# Full_bridge-2-Buck_drives_-9.net
KiCad netlist of a schematic drawn in Altium Designer
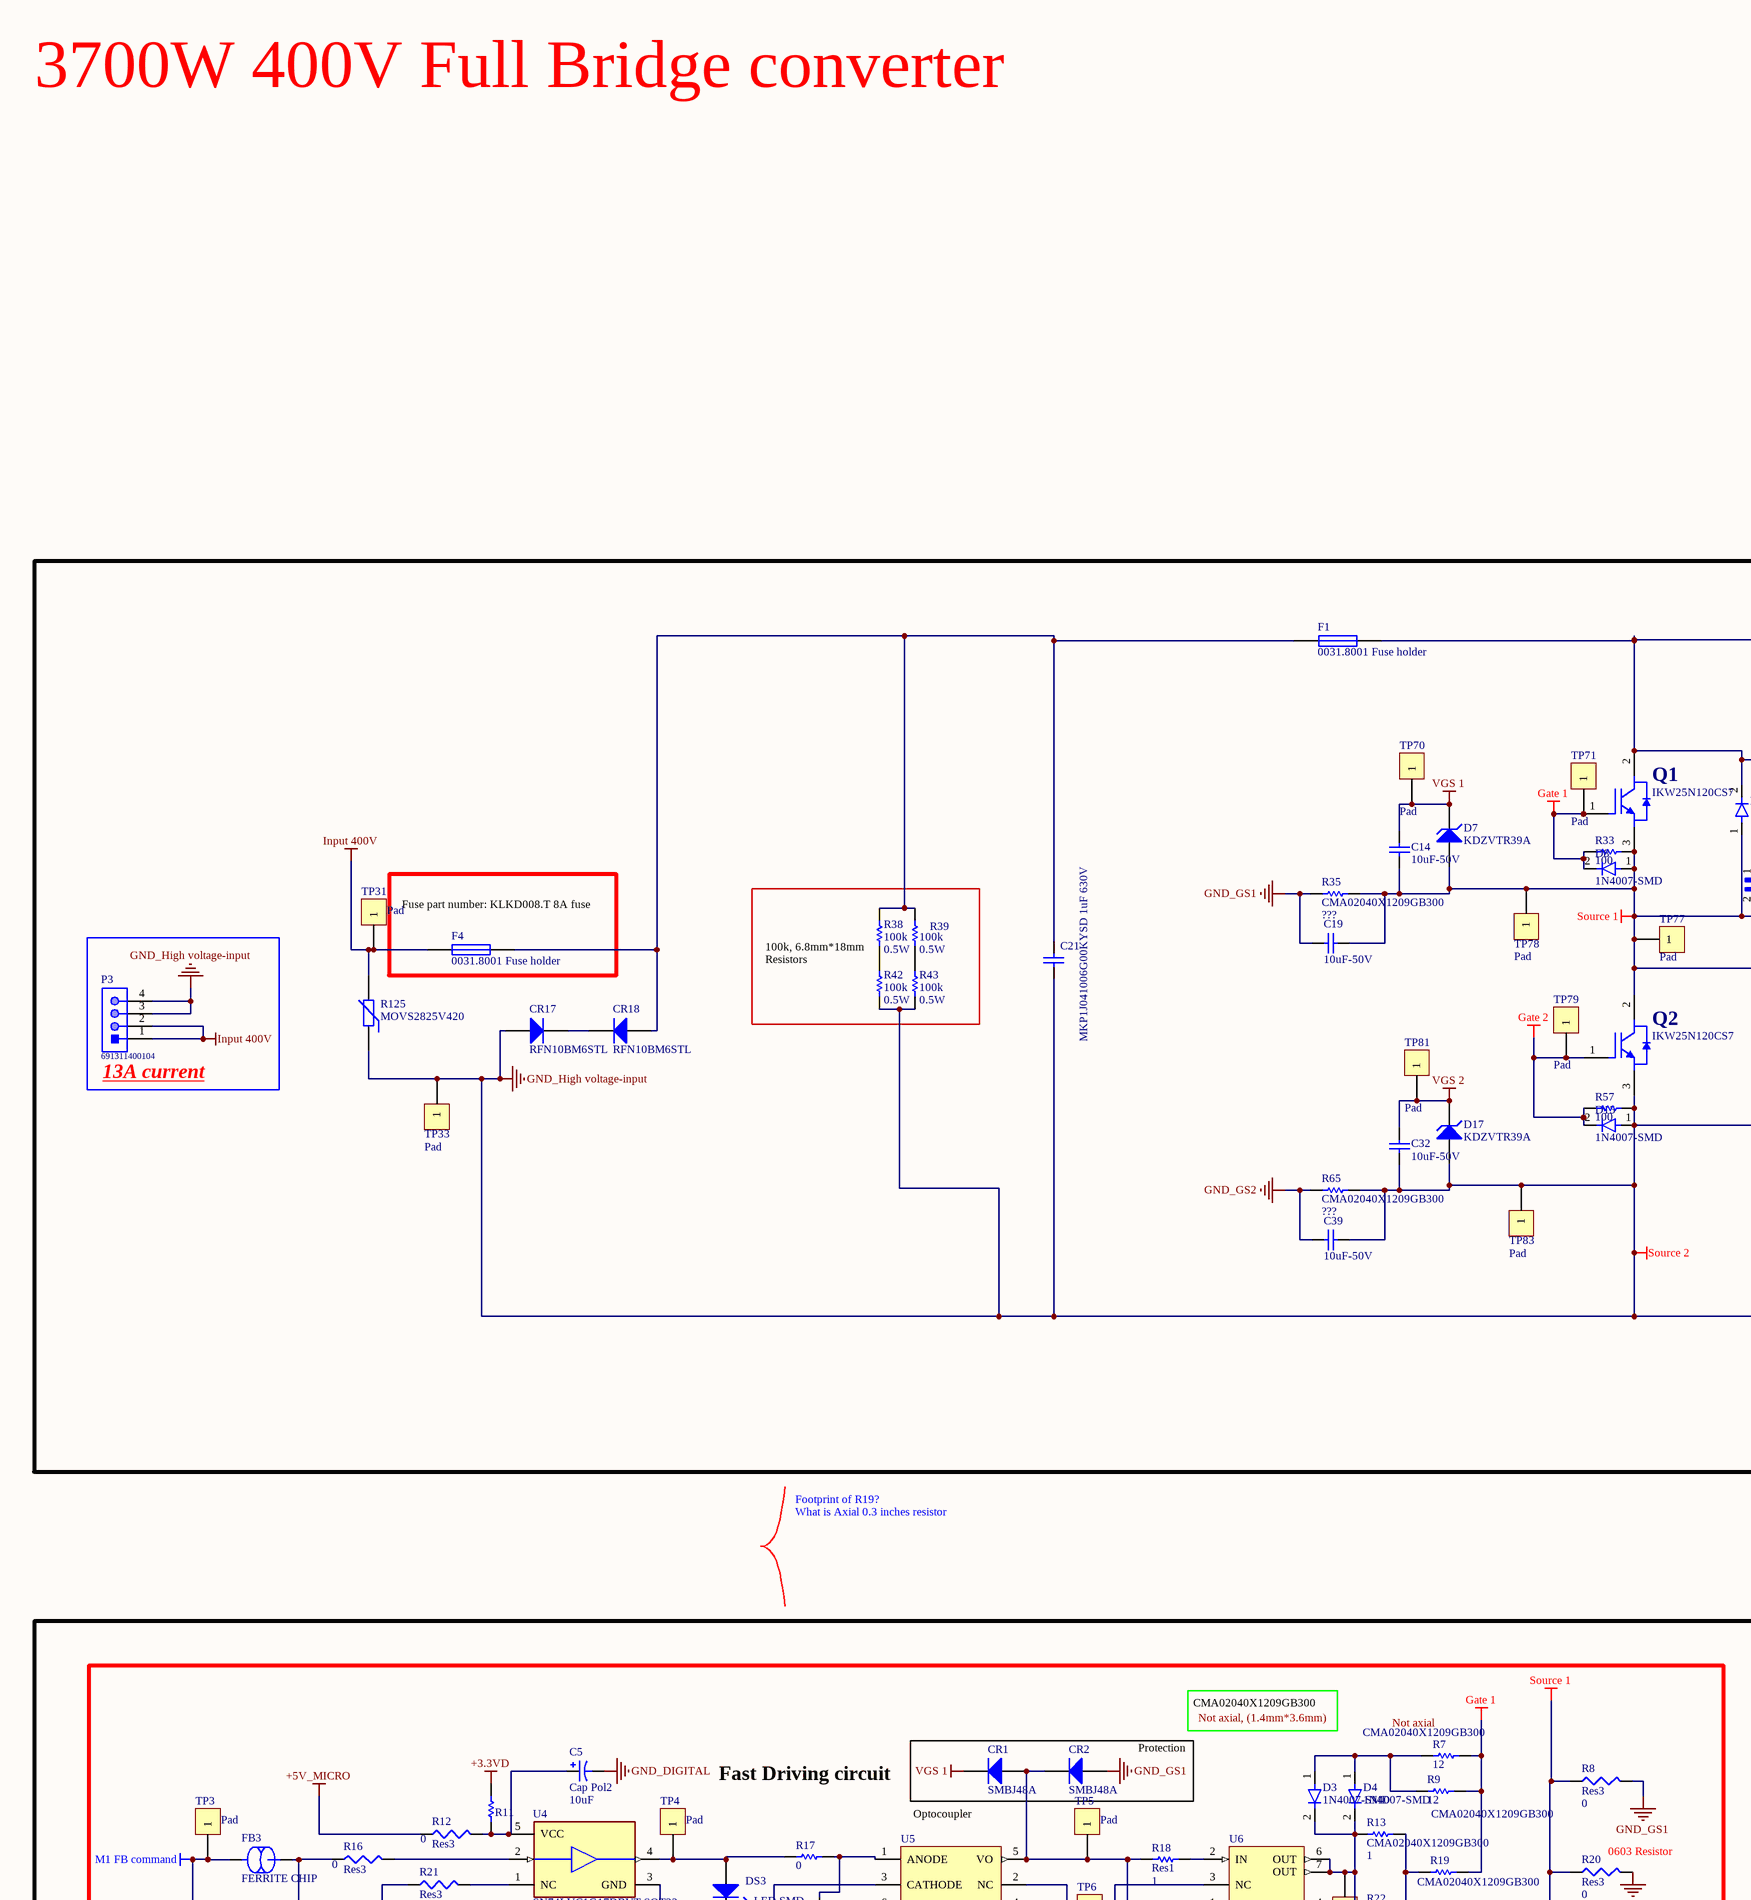
[diagram p0: Full bridge-2-Buck drives -9.SchDoc, top left]
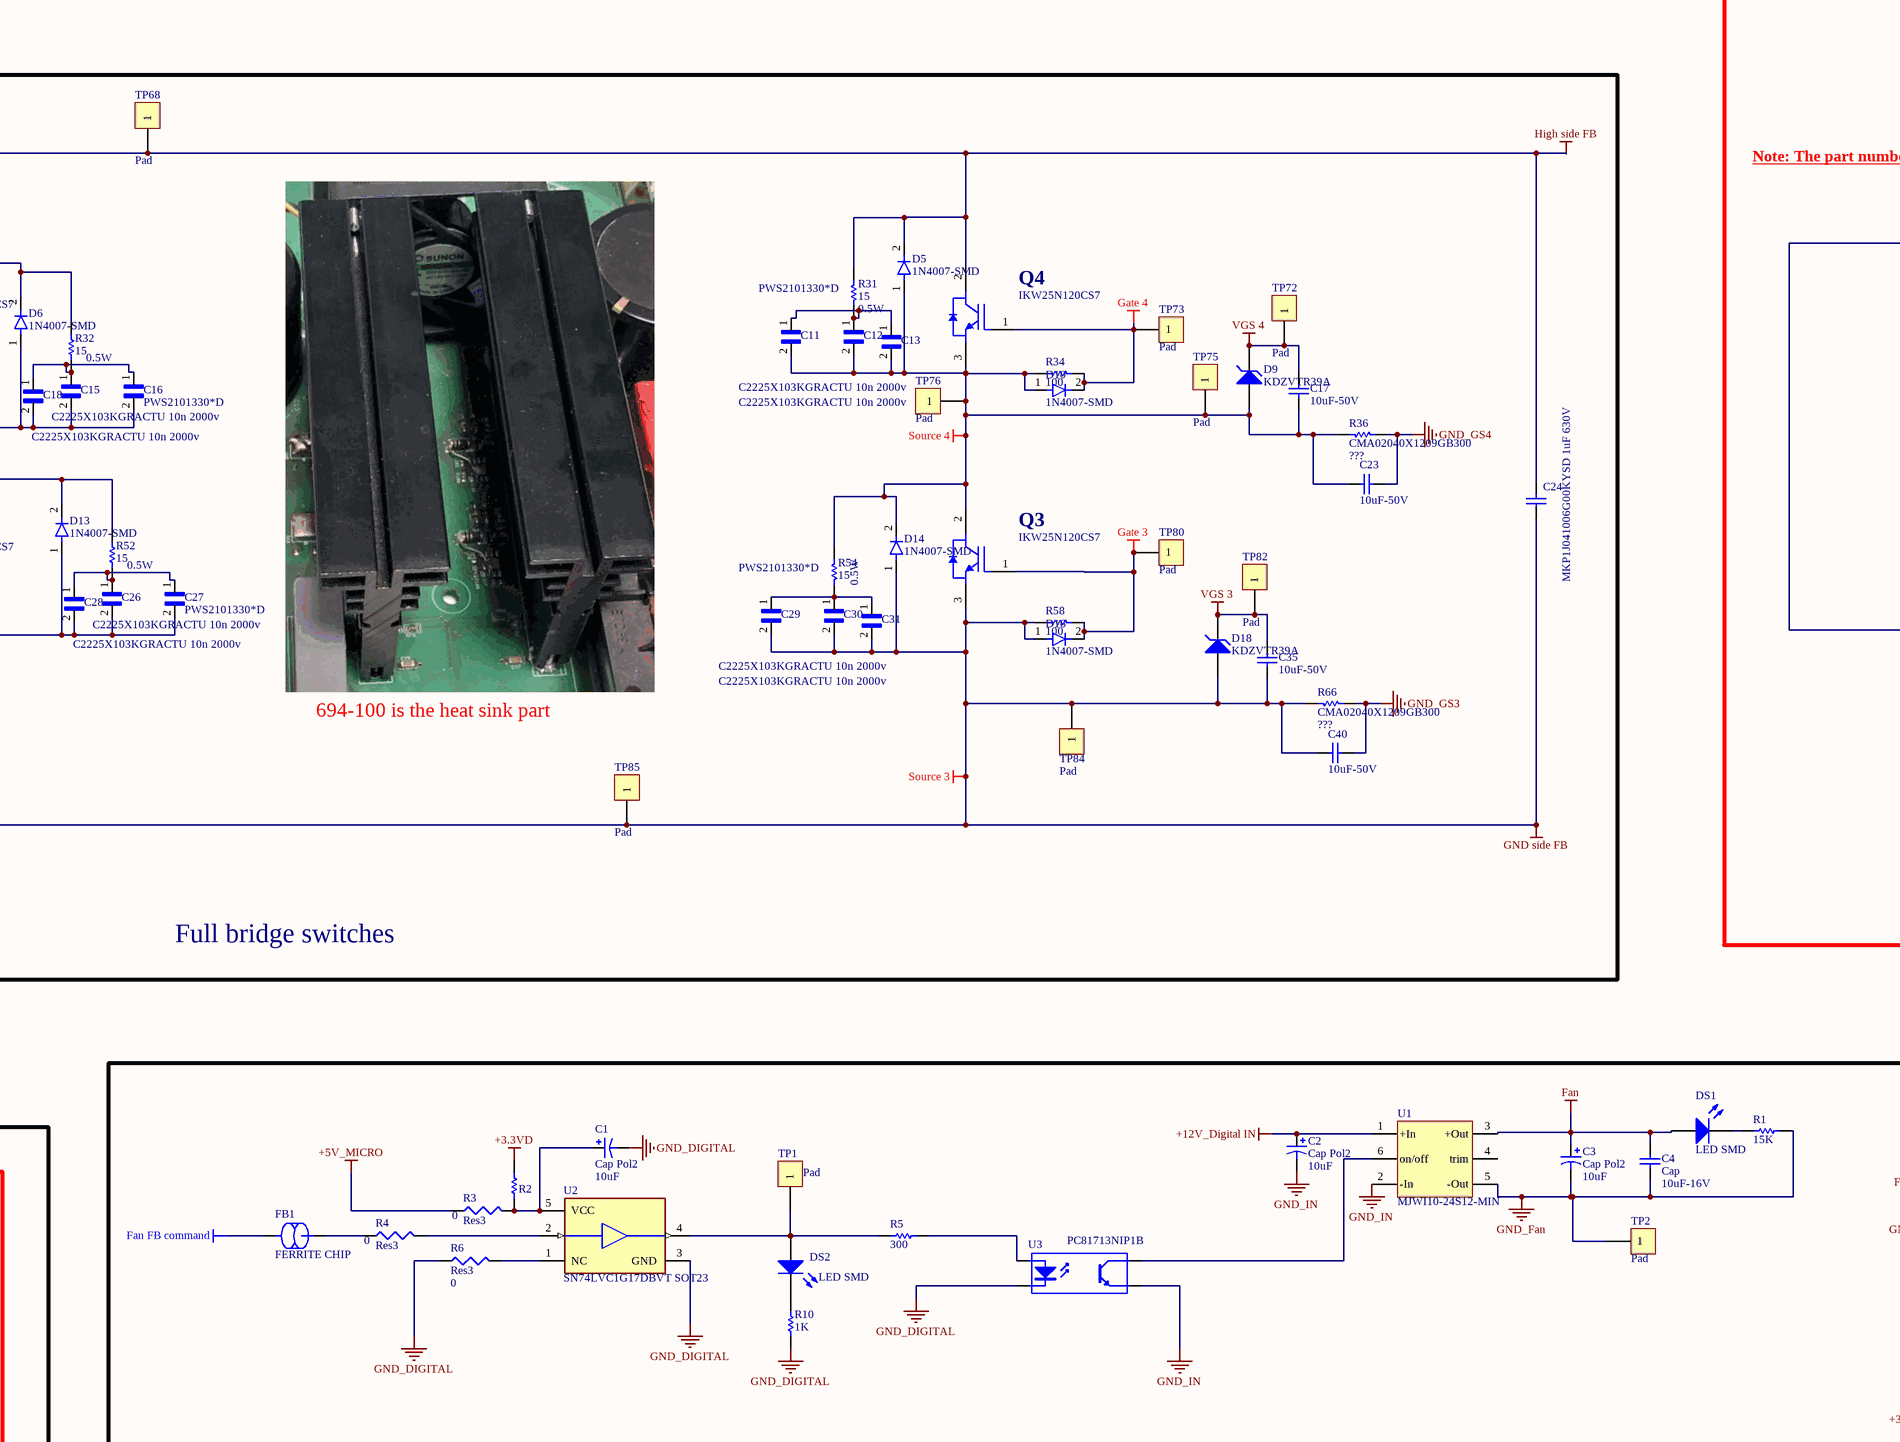
[diagram p1: Full bridge-2-Buck drives -9.SchDoc, top middle]
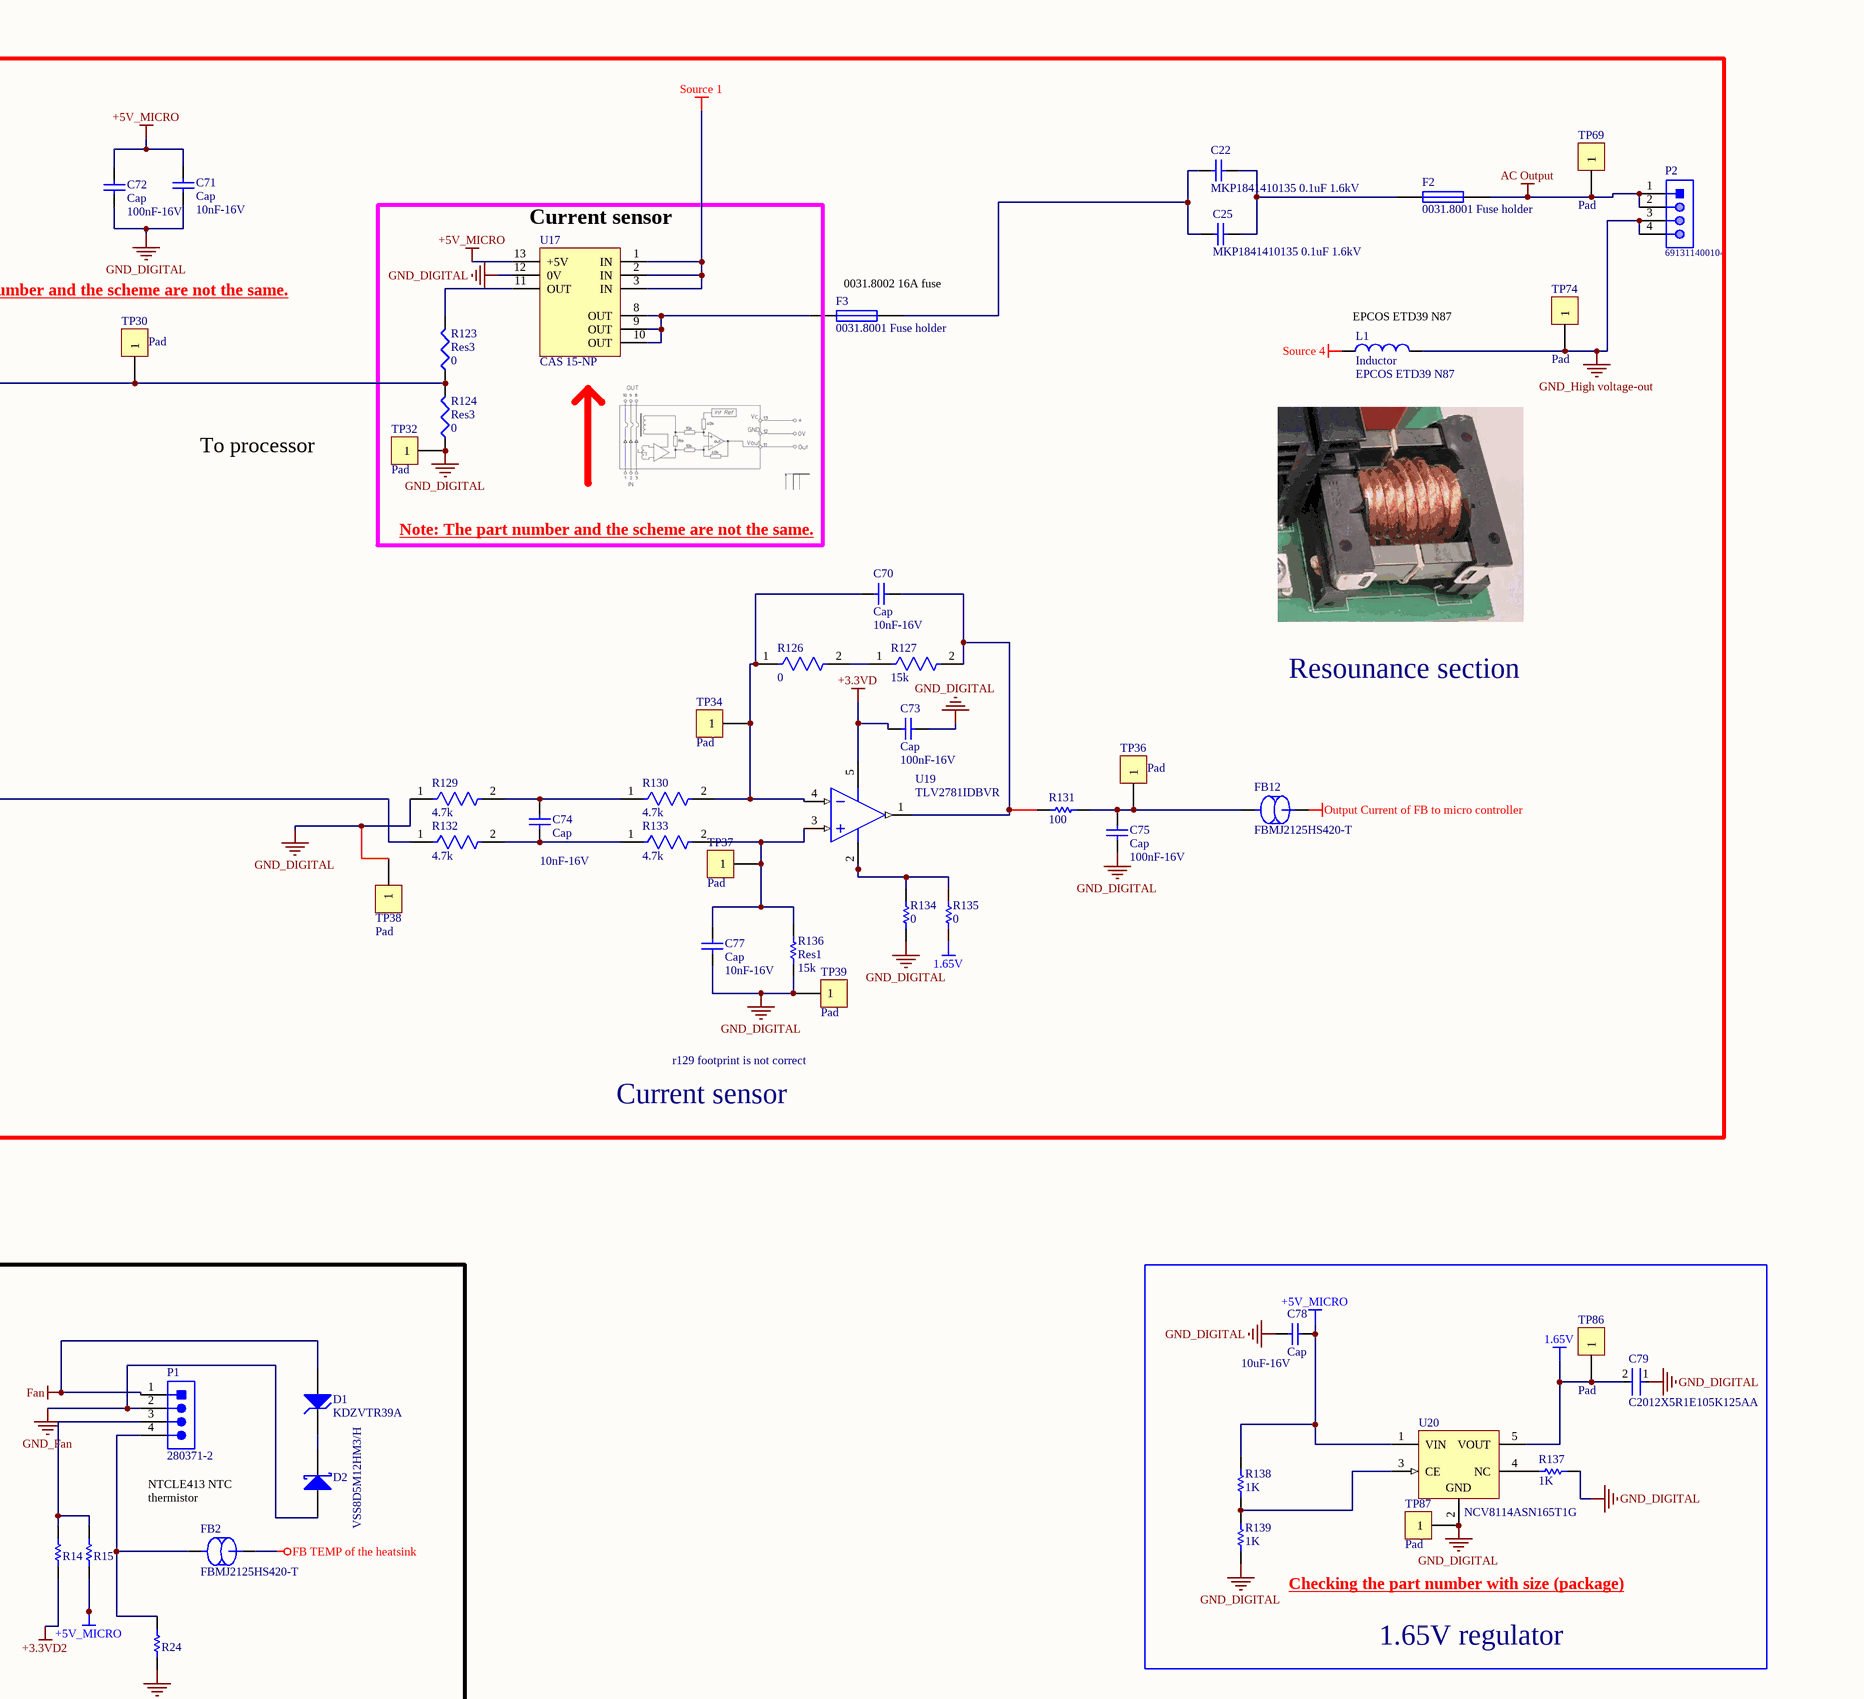
[diagram p2: Full bridge-2-Buck drives -9.SchDoc, top right]
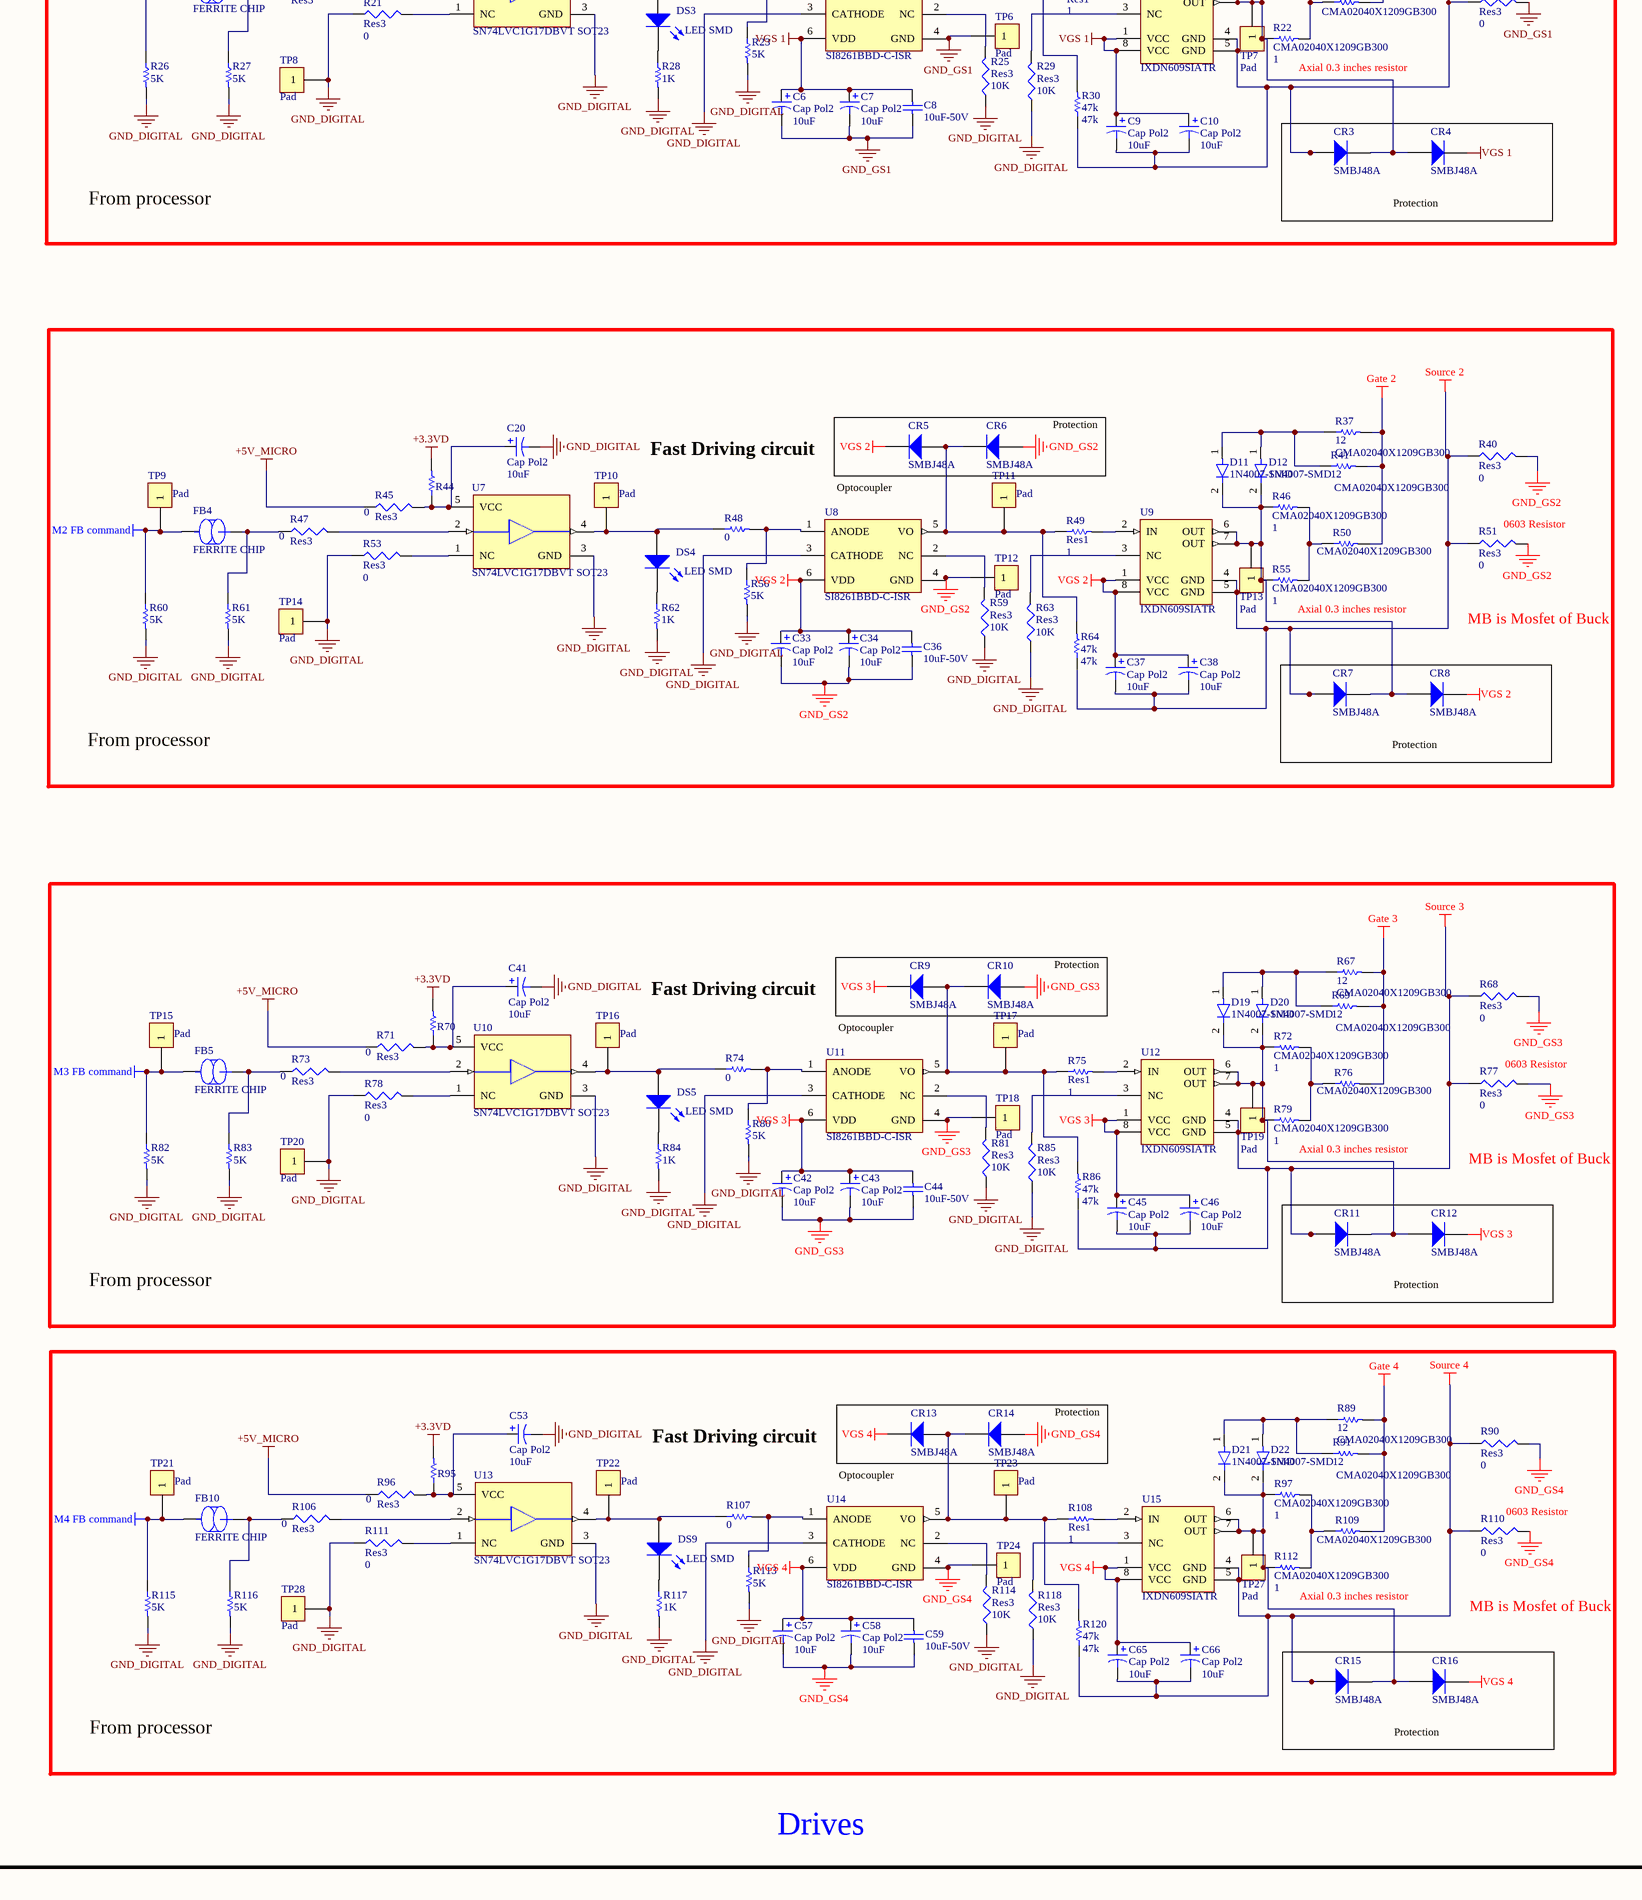
[diagram p3: Full bridge-2-Buck drives -9.SchDoc, bottom left]
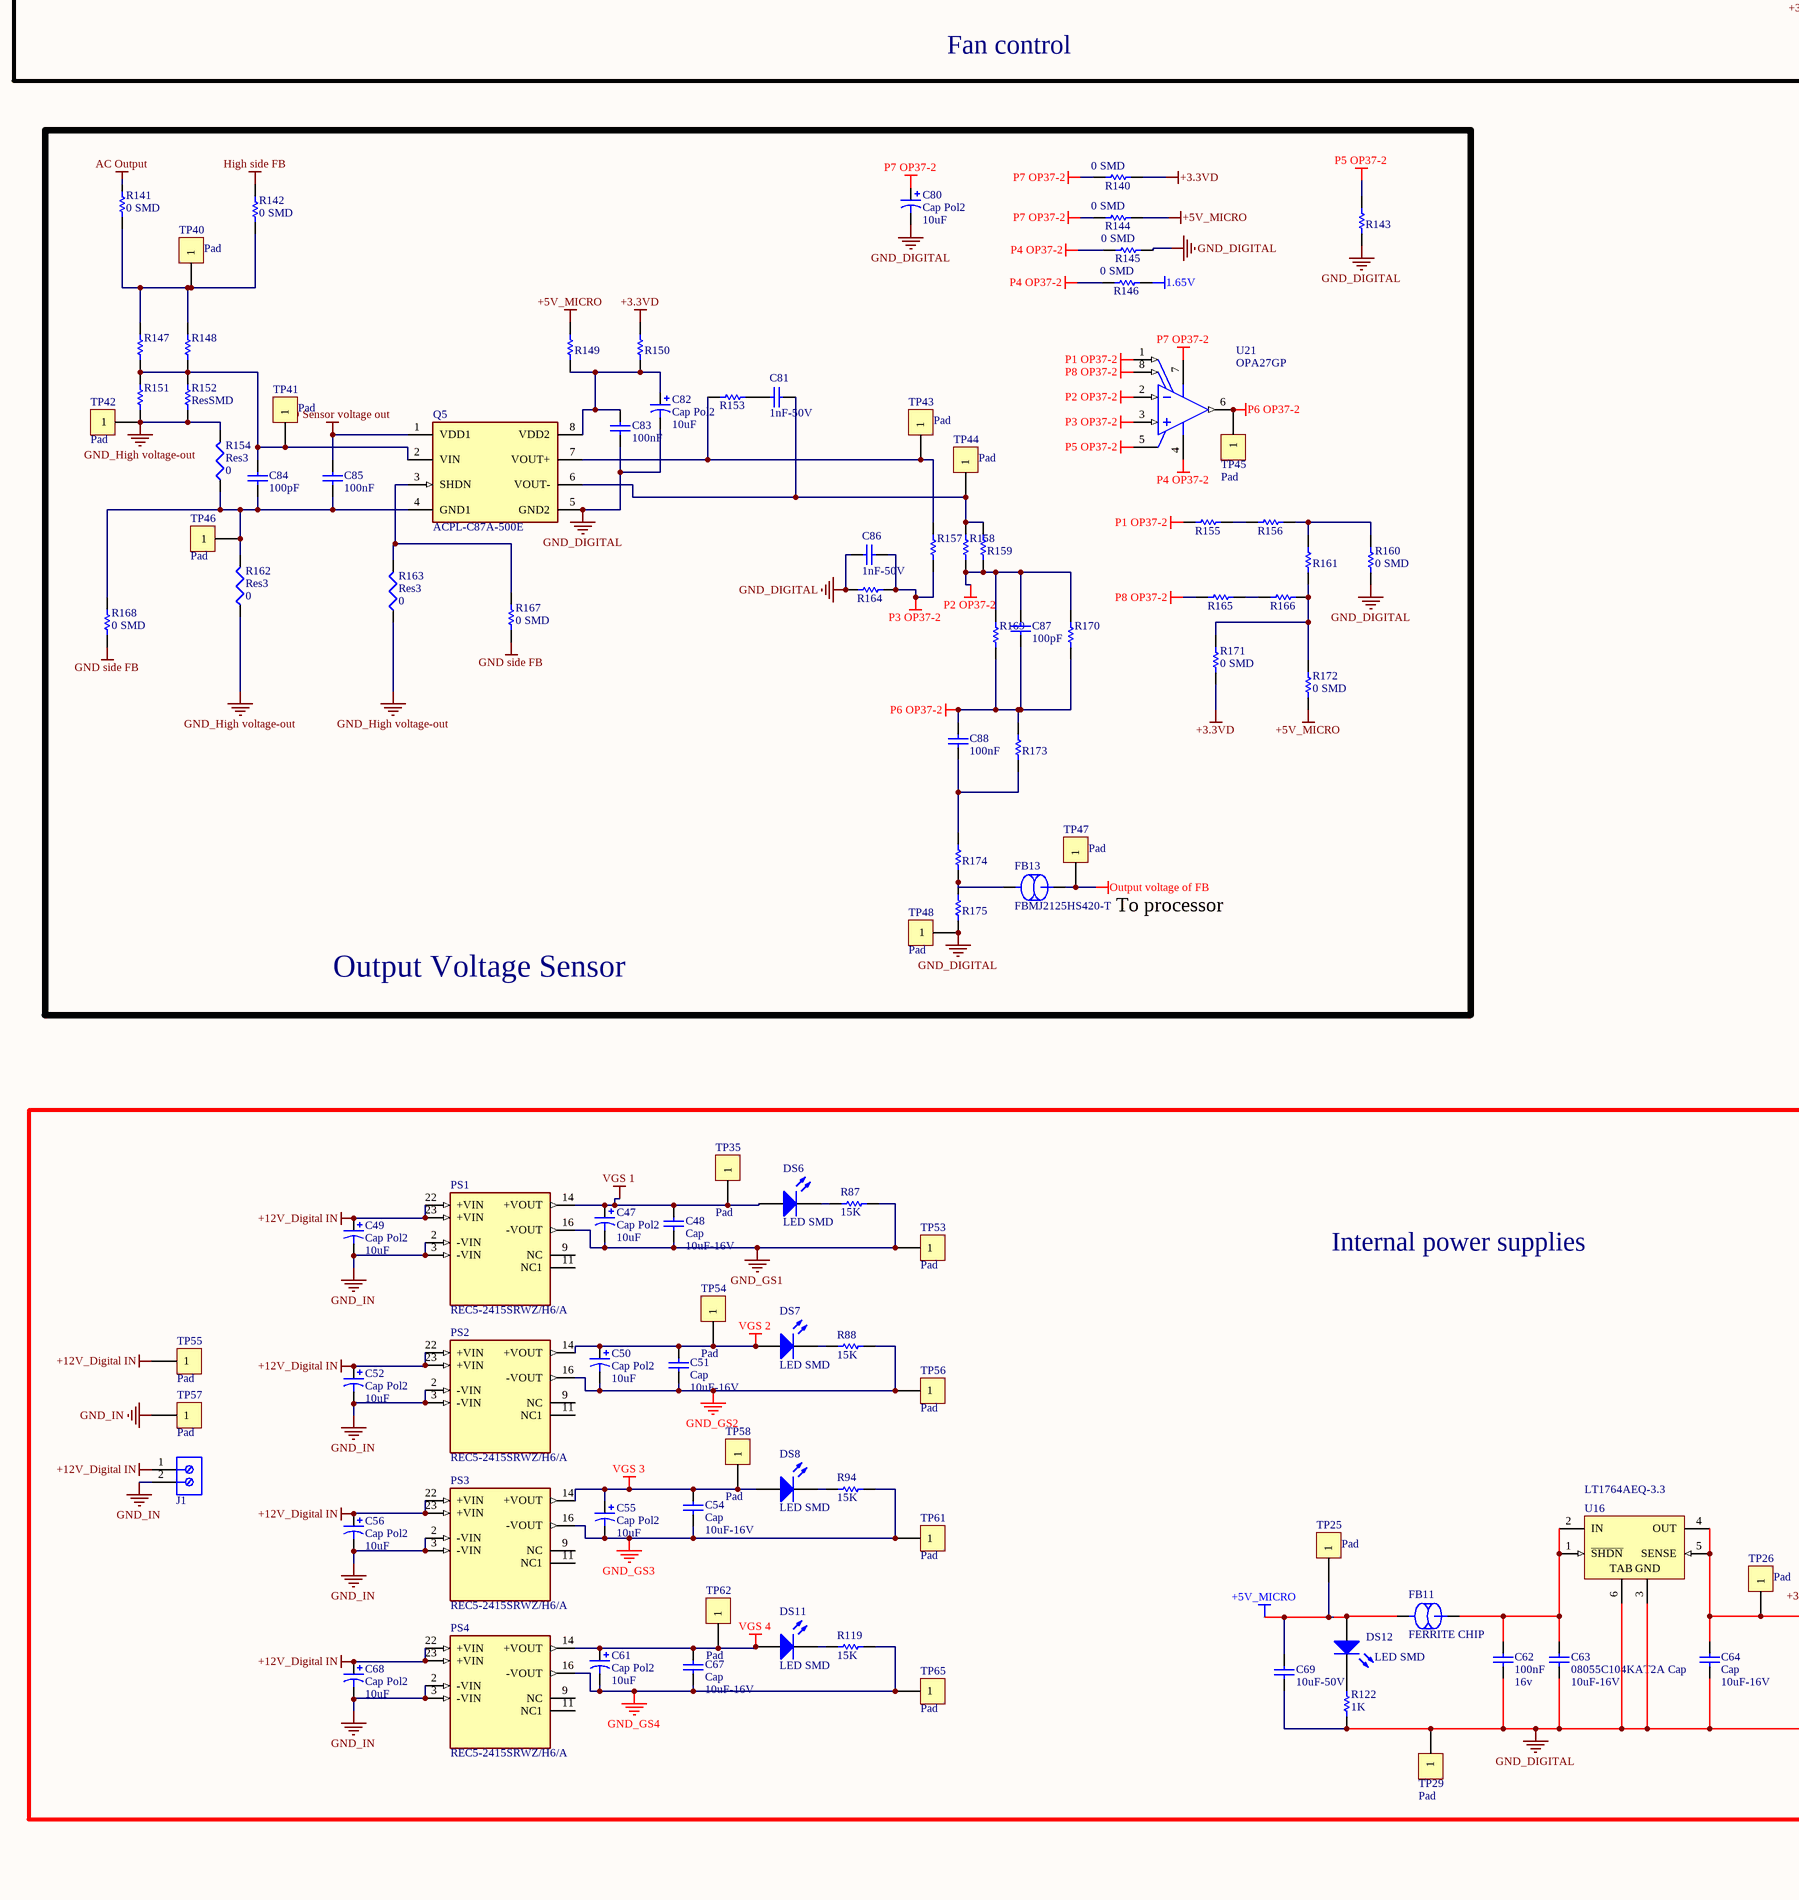
[diagram p4: Full bridge-2-Buck drives -9.SchDoc, bottom middle]
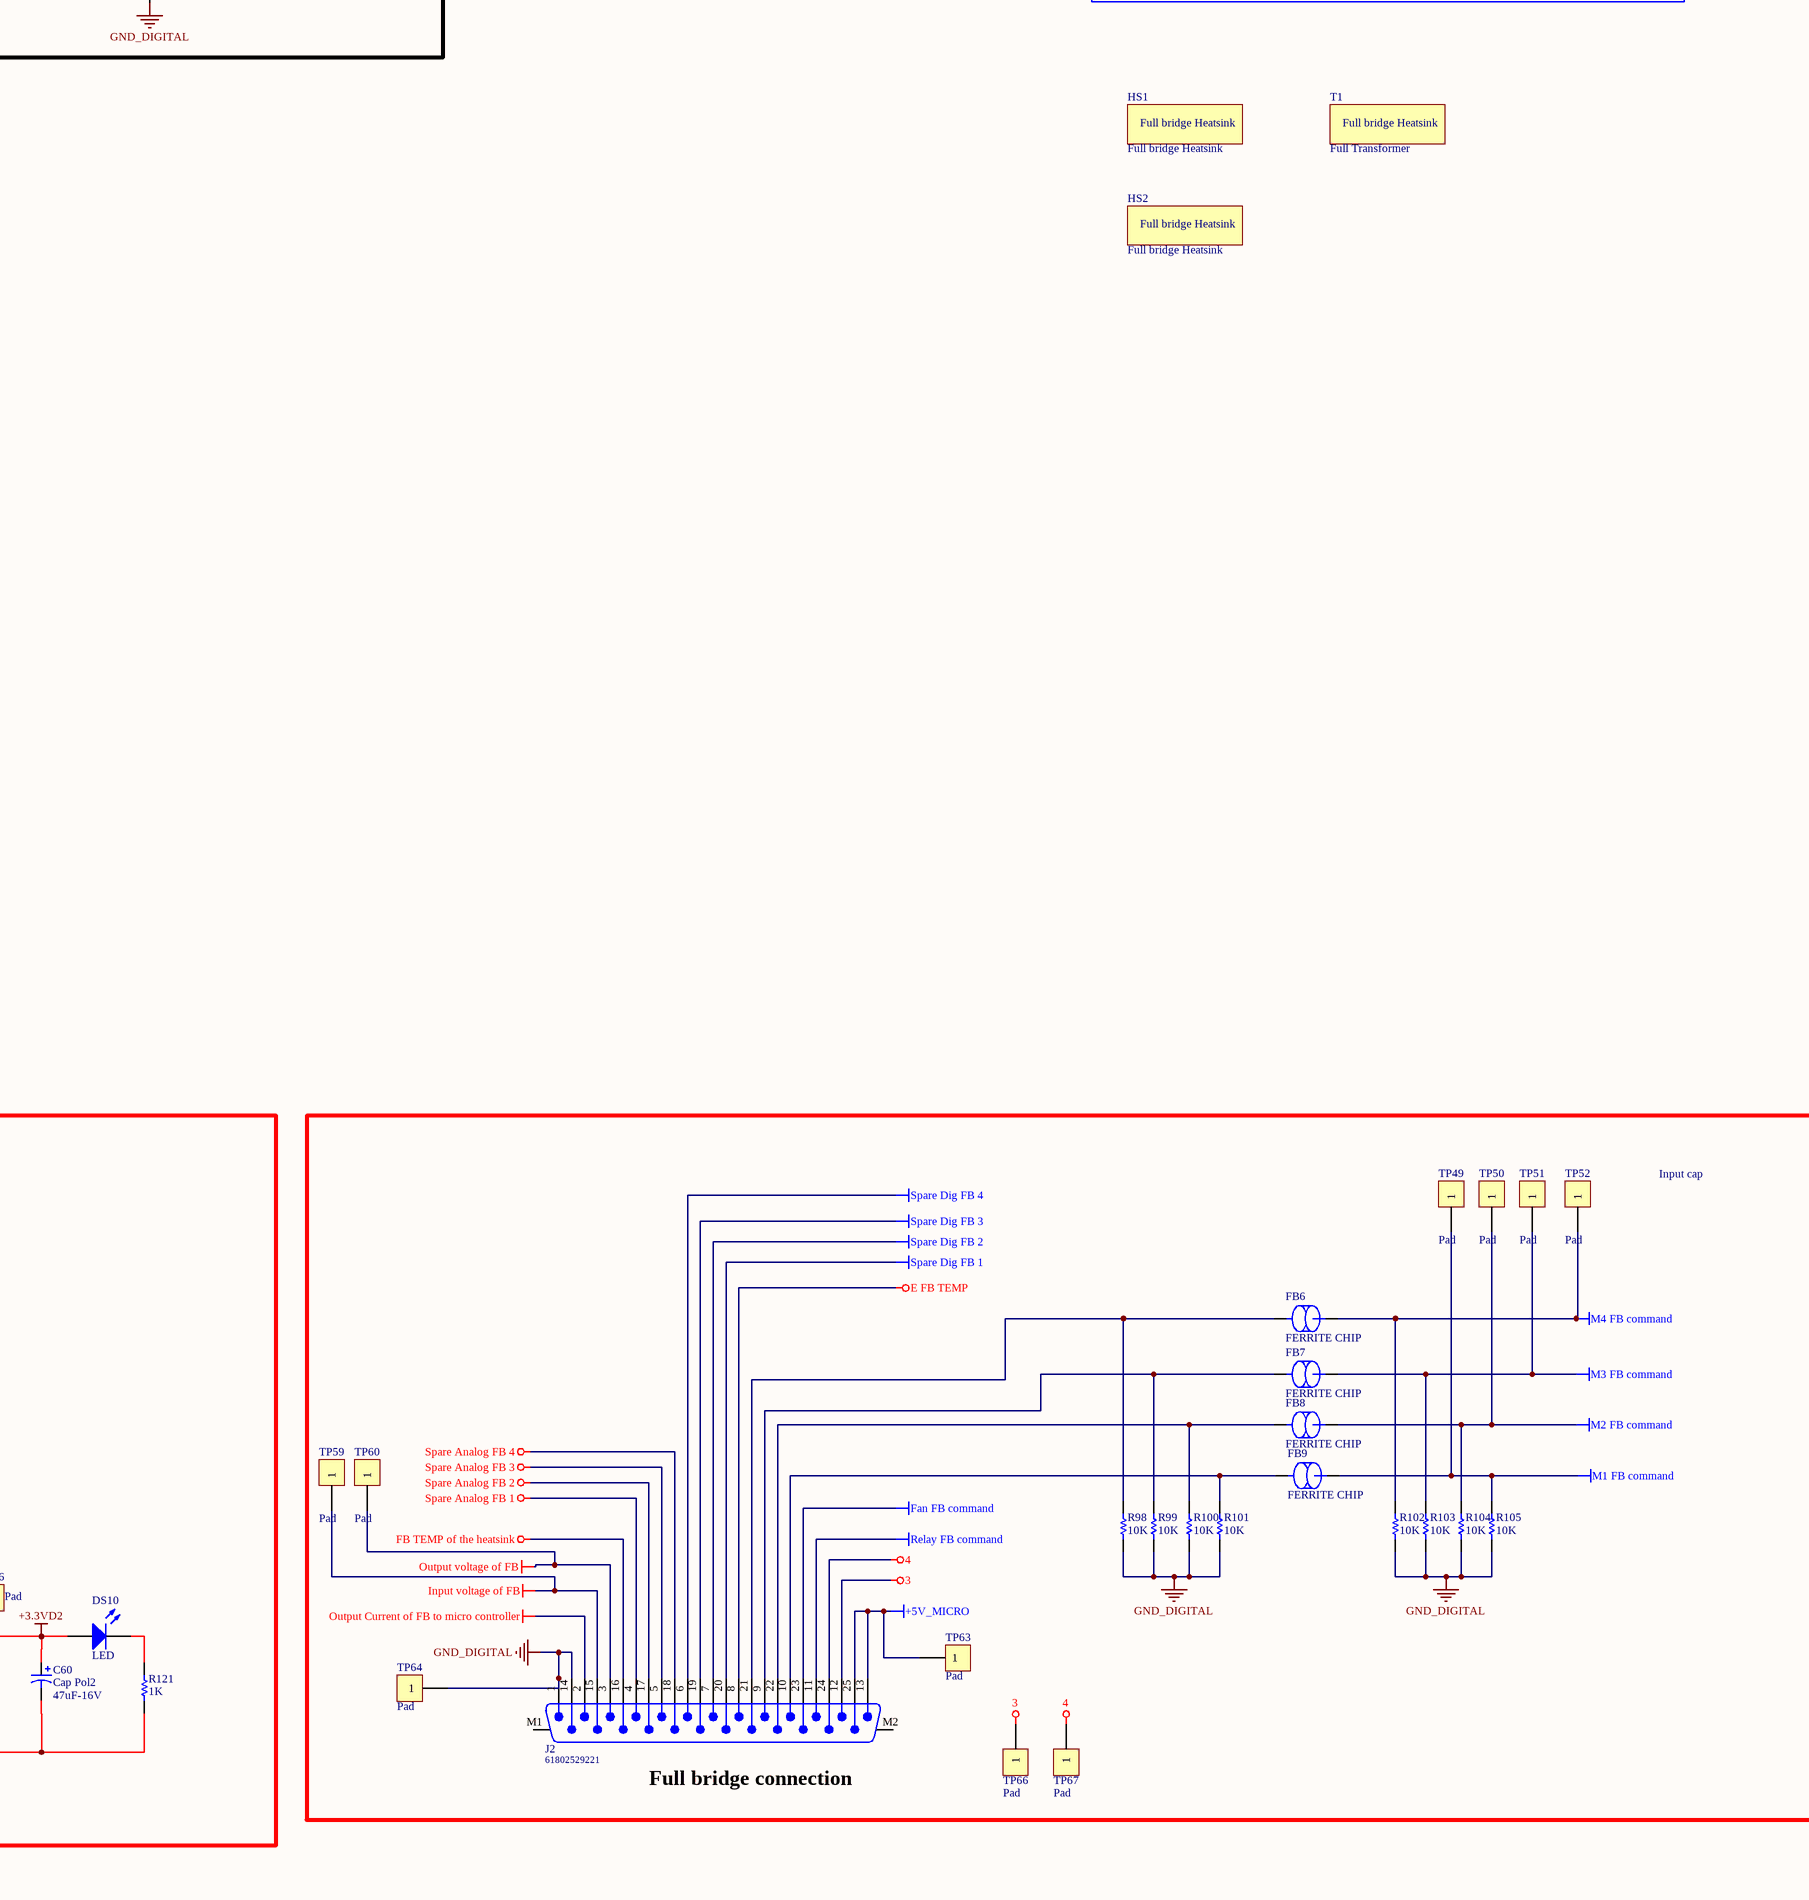
[diagram p5: Full bridge-2-Buck drives -9.SchDoc, bottom right]

(export (version "E")
  (design (tool "Eeschema 10.0.6"))
  (components
    (comp (ref "C1")
      (value "Cap Pol2")
      (footprint "Buck:CAPAE430X565N")
      (description "Polarized Capacitor (Axial)")
      (fields (field (name "ALTIUM_VALUE") "10uF") (field (name "PUBLISHER") "Altium Limited"))
      (libsource (lib "SCH") (part "Cap Pol2"))
    )
    (comp (ref "C2")
      (value "Cap Pol2")
      (footprint "Buck:CAPAE430X565N")
      (description "Polarized Capacitor (Axial)")
      (fields (field (name "ALTIUM_VALUE") "10uF") (field (name "PUBLISHER") "Altium Limited"))
      (libsource (lib "SCH") (part "Cap Pol2"))
    )
    (comp (ref "C3")
      (value "Cap Pol2")
      (footprint "Buck:CAPAE430X565N")
      (description "Polarized Capacitor (Axial)")
      (fields (field (name "ALTIUM_VALUE") "10uF") (field (name "PUBLISHER") "Altium Limited"))
      (libsource (lib "SCH") (part "Cap Pol2"))
    )
    (comp (ref "C4")
      (value "Cap")
      (footprint "Buck:C0805")
      (description "Capacitor")
      (fields (field (name "ALTIUM_VALUE") "10uF-16V") (field (name "PUBLISHER") "Altium Limited"))
      (libsource (lib "SCH") (part "Cap"))
    )
    (comp (ref "C5")
      (value "Cap Pol2")
      (footprint "Buck:CAPAE430X565N")
      (description "Polarized Capacitor (Axial)")
      (fields (field (name "ALTIUM_VALUE") "10uF") (field (name "PUBLISHER") "Altium Limited"))
      (libsource (lib "SCH") (part "Cap Pol2"))
    )
    (comp (ref "C6")
      (value "Cap Pol2")
      (footprint "Buck:CAPAE430X565N")
      (description "Polarized Capacitor (Axial)")
      (fields (field (name "ALTIUM_VALUE") "10uF") (field (name "PUBLISHER") "Altium Limited"))
      (libsource (lib "SCH") (part "Cap Pol2"))
    )
    (comp (ref "C7")
      (value "Cap Pol2")
      (footprint "Buck:CAPAE430X565N")
      (description "Polarized Capacitor (Axial)")
      (fields (field (name "ALTIUM_VALUE") "10uF") (field (name "PUBLISHER") "Altium Limited"))
      (libsource (lib "SCH") (part "Cap Pol2"))
    )
    (comp (ref "C8") (value "10uF-50V") (footprint "Buck:C0805") (libsource (lib "") (part "CapSMD_1")))
    (comp (ref "C9")
      (value "Cap Pol2")
      (footprint "Buck:CAPAE430X565N")
      (description "Polarized Capacitor (Axial)")
      (fields (field (name "ALTIUM_VALUE") "10uF") (field (name "PUBLISHER") "Altium Limited"))
      (libsource (lib "SCH") (part "Cap Pol2"))
    )
    (comp (ref "C10")
      (value "Cap Pol2")
      (footprint "Buck:CAPAE430X565N")
      (description "Polarized Capacitor (Axial)")
      (fields (field (name "ALTIUM_VALUE") "10uF") (field (name "PUBLISHER") "Altium Limited"))
      (libsource (lib "SCH") (part "Cap Pol2"))
    )
    (comp (ref "C11")
      (value "PWS2101330*D")
      (footprint "Buck:PWS2101330KD")
      (fields (field (name "MF") "AVX") (field (name "MP") "LD052C153JAB2A"))
      (libsource (lib "Capacitors dip") (part "Ceramic disk capacitor"))
    )
    (comp (ref "C12")
      (value "C2225X103KGRACTU 10n 2000v")
      (footprint "Buck:C2225")
      (fields (field (name "MF") "AVX") (field (name "MP") "LD052C153JAB2A"))
      (libsource (lib "Capacitors dip") (part "Ceramic disk capacitor"))
    )
    (comp (ref "C13")
      (value "C2225X103KGRACTU 10n 2000v")
      (footprint "Buck:C2225")
      (fields (field (name "MF") "AVX") (field (name "MP") "LD052C153JAB2A"))
      (libsource (lib "Capacitors dip") (part "Ceramic disk capacitor"))
    )
    (comp (ref "C14") (value "10uF-50V") (footprint "Buck:C0805") (libsource (lib "") (part "CapSMD_1")))
    (comp (ref "C15")
      (value "C2225X103KGRACTU 10n 2000v")
      (footprint "Buck:C2225")
      (fields (field (name "MF") "AVX") (field (name "MP") "LD052C153JAB2A"))
      (libsource (lib "") (part "Ceramic disk capacitor_1"))
    )
    (comp (ref "C16")
      (value "PWS2101330*D")
      (footprint "Buck:PWS2101330KD")
      (fields (field (name "MF") "AVX") (field (name "MP") "LD052C153JAB2A"))
      (libsource (lib "") (part "Ceramic disk capacitor_1"))
    )
    (comp (ref "C17") (value "10uF-50V") (footprint "Buck:C0805") (libsource (lib "") (part "CapSMD_1")))
    (comp (ref "C18")
      (value "C2225X103KGRACTU 10n 2000v")
      (footprint "Buck:C2225")
      (fields (field (name "MF") "AVX") (field (name "MP") "LD052C153JAB2A"))
      (libsource (lib "") (part "Ceramic disk capacitor_1"))
    )
    (comp (ref "C19") (value "10uF-50V") (footprint "Buck:C0805") (libsource (lib "") (part "CapSMD_1")))
    (comp (ref "C20")
      (value "Cap Pol2")
      (footprint "Buck:CAPAE430X565N")
      (description "Polarized Capacitor (Axial)")
      (fields (field (name "ALTIUM_VALUE") "10uF") (field (name "PUBLISHER") "Altium Limited"))
      (libsource (lib "SCH") (part "Cap Pol2"))
    )
    (comp (ref "C21")
      (value "MKP1J041006G00KYSD 1uF 630V")
      (footprint "Buck:MKP10_31x17-P27.5mm")
      (libsource (lib "MYLIB") (part "CapSMD"))
    )
    (comp (ref "C22")
      (value "MKP1841410135 0.1uF 1.6kV")
      (footprint "Buck:MKP1841410135")
      (libsource (lib "MYLIB") (part "CapSMD"))
    )
    (comp (ref "C23") (value "10uF-50V") (footprint "Buck:C0805") (libsource (lib "") (part "CapSMD_1")))
    (comp (ref "C24")
      (value "MKP1J041006G00KYSD 1uF 630V")
      (footprint "Buck:MKP10_31x17-P27.5mm")
      (libsource (lib "MYLIB") (part "CapSMD"))
    )
    (comp (ref "C25")
      (value "MKP1841410135 0.1uF 1.6kV")
      (footprint "Buck:MKP1841410135")
      (libsource (lib "MYLIB") (part "CapSMD"))
    )
    (comp (ref "C26")
      (value "C2225X103KGRACTU 10n 2000v")
      (footprint "Buck:C2225")
      (fields (field (name "MF") "AVX") (field (name "MP") "LD052C153JAB2A"))
      (libsource (lib "") (part "Ceramic disk capacitor_1"))
    )
    (comp (ref "C27")
      (value "PWS2101330*D")
      (footprint "Buck:PWS2101330KD")
      (fields (field (name "MF") "AVX") (field (name "MP") "LD052C153JAB2A"))
      (libsource (lib "") (part "Ceramic disk capacitor_1"))
    )
    (comp (ref "C28")
      (value "C2225X103KGRACTU 10n 2000v")
      (footprint "Buck:C2225")
      (fields (field (name "MF") "AVX") (field (name "MP") "LD052C153JAB2A"))
      (libsource (lib "") (part "Ceramic disk capacitor_1"))
    )
    (comp (ref "C29")
      (value "PWS2101330*D")
      (footprint "Buck:PWS2101330KD")
      (fields (field (name "MF") "AVX") (field (name "MP") "LD052C153JAB2A"))
      (libsource (lib "Capacitors dip") (part "Ceramic disk capacitor"))
    )
    (comp (ref "C30")
      (value "C2225X103KGRACTU 10n 2000v")
      (footprint "Buck:C2225")
      (fields (field (name "MF") "AVX") (field (name "MP") "LD052C153JAB2A"))
      (libsource (lib "Capacitors dip") (part "Ceramic disk capacitor"))
    )
    (comp (ref "C31")
      (value "C2225X103KGRACTU 10n 2000v")
      (footprint "Buck:C2225")
      (fields (field (name "MF") "AVX") (field (name "MP") "LD052C153JAB2A"))
      (libsource (lib "Capacitors dip") (part "Ceramic disk capacitor"))
    )
    (comp (ref "C32") (value "10uF-50V") (footprint "Buck:C0805") (libsource (lib "") (part "CapSMD_1")))
    (comp (ref "C33")
      (value "Cap Pol2")
      (footprint "Buck:CAPAE430X565N")
      (description "Polarized Capacitor (Axial)")
      (fields (field (name "ALTIUM_VALUE") "10uF") (field (name "PUBLISHER") "Altium Limited"))
      (libsource (lib "SCH") (part "Cap Pol2"))
    )
    (comp (ref "C34")
      (value "Cap Pol2")
      (footprint "Buck:CAPAE430X565N")
      (description "Polarized Capacitor (Axial)")
      (fields (field (name "ALTIUM_VALUE") "10uF") (field (name "PUBLISHER") "Altium Limited"))
      (libsource (lib "SCH") (part "Cap Pol2"))
    )
    (comp (ref "C35") (value "10uF-50V") (footprint "Buck:C0805") (libsource (lib "") (part "CapSMD_1")))
    (comp (ref "C36") (value "10uF-50V") (footprint "Buck:C0805") (libsource (lib "") (part "CapSMD_1")))
    (comp (ref "C37")
      (value "Cap Pol2")
      (footprint "Buck:CAPAE430X565N")
      (description "Polarized Capacitor (Axial)")
      (fields (field (name "ALTIUM_VALUE") "10uF") (field (name "PUBLISHER") "Altium Limited"))
      (libsource (lib "SCH") (part "Cap Pol2"))
    )
    (comp (ref "C38")
      (value "Cap Pol2")
      (footprint "Buck:CAPAE430X565N")
      (description "Polarized Capacitor (Axial)")
      (fields (field (name "ALTIUM_VALUE") "10uF") (field (name "PUBLISHER") "Altium Limited"))
      (libsource (lib "SCH") (part "Cap Pol2"))
    )
    (comp (ref "C39") (value "10uF-50V") (footprint "Buck:C0805") (libsource (lib "") (part "CapSMD_1")))
    (comp (ref "C40") (value "10uF-50V") (footprint "Buck:C0805") (libsource (lib "") (part "CapSMD_1")))
    (comp (ref "C41")
      (value "Cap Pol2")
      (footprint "Buck:CAPAE430X565N")
      (description "Polarized Capacitor (Axial)")
      (fields (field (name "ALTIUM_VALUE") "10uF") (field (name "PUBLISHER") "Altium Limited"))
      (libsource (lib "SCH") (part "Cap Pol2"))
    )
    (comp (ref "C42")
      (value "Cap Pol2")
      (footprint "Buck:CAPAE430X565N")
      (description "Polarized Capacitor (Axial)")
      (fields (field (name "ALTIUM_VALUE") "10uF") (field (name "PUBLISHER") "Altium Limited"))
      (libsource (lib "SCH") (part "Cap Pol2"))
    )
    (comp (ref "C43")
      (value "Cap Pol2")
      (footprint "Buck:CAPAE430X565N")
      (description "Polarized Capacitor (Axial)")
      (fields (field (name "ALTIUM_VALUE") "10uF") (field (name "PUBLISHER") "Altium Limited"))
      (libsource (lib "SCH") (part "Cap Pol2"))
    )
    (comp (ref "C44") (value "10uF-50V") (footprint "Buck:C0805") (libsource (lib "") (part "CapSMD_1")))
    (comp (ref "C45")
      (value "Cap Pol2")
      (footprint "Buck:CAPAE430X565N")
      (description "Polarized Capacitor (Axial)")
      (fields (field (name "ALTIUM_VALUE") "10uF") (field (name "PUBLISHER") "Altium Limited"))
      (libsource (lib "SCH") (part "Cap Pol2"))
    )
    (comp (ref "C46")
      (value "Cap Pol2")
      (footprint "Buck:CAPAE430X565N")
      (description "Polarized Capacitor (Axial)")
      (fields (field (name "ALTIUM_VALUE") "10uF") (field (name "PUBLISHER") "Altium Limited"))
      (libsource (lib "SCH") (part "Cap Pol2"))
    )
    (comp (ref "C47")
      (value "Cap Pol2")
      (footprint "Buck:CAPAE430X565N")
      (description "Polarized Capacitor (Axial)")
      (fields (field (name "ALTIUM_VALUE") "10uF") (field (name "PUBLISHER") "Altium Limited"))
      (libsource (lib "SCH") (part "Cap Pol2"))
    )
    (comp (ref "C48")
      (value "Cap")
      (footprint "Buck:C0805")
      (description "Capacitor")
      (fields (field (name "ALTIUM_VALUE") "10uF-16V") (field (name "PUBLISHER") "Altium Limited"))
      (libsource (lib "SCH") (part "Cap"))
    )
    (comp (ref "C49")
      (value "Cap Pol2")
      (footprint "Buck:CAPAE430X565N")
      (description "Polarized Capacitor (Axial)")
      (fields (field (name "ALTIUM_VALUE") "10uF") (field (name "PUBLISHER") "Altium Limited"))
      (libsource (lib "SCH") (part "Cap Pol2"))
    )
    (comp (ref "C50")
      (value "Cap Pol2")
      (footprint "Buck:CAPAE430X565N")
      (description "Polarized Capacitor (Axial)")
      (fields (field (name "ALTIUM_VALUE") "10uF") (field (name "PUBLISHER") "Altium Limited"))
      (libsource (lib "SCH") (part "Cap Pol2"))
    )
    (comp (ref "C51")
      (value "Cap")
      (footprint "Buck:C0805")
      (description "Capacitor")
      (fields (field (name "ALTIUM_VALUE") "10uF-16V") (field (name "PUBLISHER") "Altium Limited"))
      (libsource (lib "SCH") (part "Cap"))
    )
    (comp (ref "C52")
      (value "Cap Pol2")
      (footprint "Buck:CAPAE430X565N")
      (description "Polarized Capacitor (Axial)")
      (fields (field (name "ALTIUM_VALUE") "10uF") (field (name "PUBLISHER") "Altium Limited"))
      (libsource (lib "SCH") (part "Cap Pol2"))
    )
    (comp (ref "C53")
      (value "Cap Pol2")
      (footprint "Buck:CAPAE430X565N")
      (description "Polarized Capacitor (Axial)")
      (fields (field (name "ALTIUM_VALUE") "10uF") (field (name "PUBLISHER") "Altium Limited"))
      (libsource (lib "SCH") (part "Cap Pol2"))
    )
    (comp (ref "C54")
      (value "Cap")
      (footprint "Buck:C0805")
      (description "Capacitor")
      (fields (field (name "ALTIUM_VALUE") "10uF-16V") (field (name "PUBLISHER") "Altium Limited"))
      (libsource (lib "SCH") (part "Cap"))
    )
    (comp (ref "C55")
      (value "Cap Pol2")
      (footprint "Buck:CAPAE430X565N")
      (description "Polarized Capacitor (Axial)")
      (fields (field (name "ALTIUM_VALUE") "10uF") (field (name "PUBLISHER") "Altium Limited"))
      (libsource (lib "SCH") (part "Cap Pol2"))
    )
    (comp (ref "C56")
      (value "Cap Pol2")
      (footprint "Buck:CAPAE430X565N")
      (description "Polarized Capacitor (Axial)")
      (fields (field (name "ALTIUM_VALUE") "10uF") (field (name "PUBLISHER") "Altium Limited"))
      (libsource (lib "SCH") (part "Cap Pol2"))
    )
    (comp (ref "C57")
      (value "Cap Pol2")
      (footprint "Buck:CAPAE430X565N")
      (description "Polarized Capacitor (Axial)")
      (fields (field (name "ALTIUM_VALUE") "10uF") (field (name "PUBLISHER") "Altium Limited"))
      (libsource (lib "SCH") (part "Cap Pol2"))
    )
    (comp (ref "C58")
      (value "Cap Pol2")
      (footprint "Buck:CAPAE430X565N")
      (description "Polarized Capacitor (Axial)")
      (fields (field (name "ALTIUM_VALUE") "10uF") (field (name "PUBLISHER") "Altium Limited"))
      (libsource (lib "SCH") (part "Cap Pol2"))
    )
    (comp (ref "C59") (value "10uF-50V") (footprint "Buck:C0805") (libsource (lib "") (part "CapSMD_1")))
    (comp (ref "C60")
      (value "Cap Pol2")
      (footprint "Buck:CAPAE430X565N")
      (description "Polarized Capacitor (Axial)")
      (fields (field (name "ALTIUM_VALUE") "47uF-16V") (field (name "PUBLISHER") "Altium Limited"))
      (libsource (lib "SCH") (part "Cap Pol2"))
    )
    (comp (ref "C61")
      (value "Cap Pol2")
      (footprint "Buck:CAPAE430X565N")
      (description "Polarized Capacitor (Axial)")
      (fields (field (name "ALTIUM_VALUE") "10uF") (field (name "PUBLISHER") "Altium Limited"))
      (libsource (lib "SCH") (part "Cap Pol2"))
    )
    (comp (ref "C62")
      (value "100nF")
      (footprint "Buck:C0805")
      (description "None polar capacitor")
      (fields (field (name "VOLTE") "16v"))
      (libsource (lib "Mylib") (part "Cap ceramic"))
    )
    (comp (ref "C63")
      (value "08055C104KAT2A Cap")
      (footprint "Buck:C0805")
      (description "Capacitor")
      (fields (field (name "ALTIUM_VALUE") "10uF-16V") (field (name "PUBLISHER") "Altium Limited"))
      (libsource (lib "SCH") (part "Cap"))
    )
    (comp (ref "C64")
      (value "Cap")
      (footprint "Buck:C0805")
      (description "Capacitor")
      (fields (field (name "ALTIUM_VALUE") "10uF-16V") (field (name "PUBLISHER") "Altium Limited"))
      (libsource (lib "SCH") (part "Cap"))
    )
    (comp (ref "C65")
      (value "Cap Pol2")
      (footprint "Buck:CAPAE430X565N")
      (description "Polarized Capacitor (Axial)")
      (fields (field (name "ALTIUM_VALUE") "10uF") (field (name "PUBLISHER") "Altium Limited"))
      (libsource (lib "SCH") (part "Cap Pol2"))
    )
    (comp (ref "C66")
      (value "Cap Pol2")
      (footprint "Buck:CAPAE430X565N")
      (description "Polarized Capacitor (Axial)")
      (fields (field (name "ALTIUM_VALUE") "10uF") (field (name "PUBLISHER") "Altium Limited"))
      (libsource (lib "SCH") (part "Cap Pol2"))
    )
    (comp (ref "C67")
      (value "Cap")
      (footprint "Buck:C0805")
      (description "Capacitor")
      (fields (field (name "ALTIUM_VALUE") "10uF-16V") (field (name "PUBLISHER") "Altium Limited"))
      (libsource (lib "SCH") (part "Cap"))
    )
    (comp (ref "C68")
      (value "Cap Pol2")
      (footprint "Buck:CAPAE430X565N")
      (description "Polarized Capacitor (Axial)")
      (fields (field (name "ALTIUM_VALUE") "10uF") (field (name "PUBLISHER") "Altium Limited"))
      (libsource (lib "SCH") (part "Cap Pol2"))
    )
    (comp (ref "C69") (value "10uF-50V") (footprint "Buck:C0805") (libsource (lib "") (part "CapSMD_1")))
    (comp (ref "C70")
      (value "Cap")
      (footprint "Buck:C0805")
      (description "Capacitor")
      (fields (field (name "ALTIUM_VALUE") "10nF-16V") (field (name "PUBLISHER") "Altium Limited"))
      (libsource (lib "SCH") (part "Cap"))
    )
    (comp (ref "C71")
      (value "Cap")
      (footprint "Buck:C0805")
      (description "Capacitor")
      (fields (field (name "ALTIUM_VALUE") "10nF-16V") (field (name "PUBLISHER") "Altium Limited"))
      (libsource (lib "SCH") (part "Cap"))
    )
    (comp (ref "C72")
      (value "Cap")
      (footprint "Buck:C0805")
      (description "Capacitor")
      (fields (field (name "ALTIUM_VALUE") "100nF-16V") (field (name "PUBLISHER") "Altium Limited"))
      (libsource (lib "SCH") (part "Cap"))
    )
    (comp (ref "C73")
      (value "Cap")
      (footprint "Buck:C0805")
      (description "Capacitor")
      (fields (field (name "ALTIUM_VALUE") "100nF-16V") (field (name "PUBLISHER") "Altium Limited"))
      (libsource (lib "SCH") (part "Cap"))
    )
    (comp (ref "C74")
      (value "Cap")
      (footprint "Buck:C0805")
      (description "Capacitor")
      (fields (field (name "ALTIUM_VALUE") "10nF-16V") (field (name "PUBLISHER") "Altium Limited"))
      (libsource (lib "SCH") (part "Cap"))
    )
    (comp (ref "C75")
      (value "Cap")
      (footprint "Buck:C0805")
      (description "Capacitor")
      (fields (field (name "ALTIUM_VALUE") "100nF-16V") (field (name "PUBLISHER") "Altium Limited"))
      (libsource (lib "SCH") (part "Cap"))
    )
    (comp (ref "C77")
      (value "Cap")
      (footprint "Buck:C0805")
      (description "Capacitor")
      (fields (field (name "ALTIUM_VALUE") "10nF-16V") (field (name "PUBLISHER") "Altium Limited"))
      (libsource (lib "SCH") (part "Cap"))
    )
    (comp (ref "C78")
      (value "Cap")
      (footprint "Buck:C0805")
      (description "Capacitor")
      (fields (field (name "ALTIUM_VALUE") "10uF-16V") (field (name "PUBLISHER") "Altium Limited"))
      (libsource (lib "SCH") (part "Cap"))
    )
    (comp (ref "C79")
      (value "C2012X5R1E105K125AA")
      (footprint "Buck:C0805")
      (description "Multilayer Ceramic Capacitors 1μF ±10% 25V X5R SMD 0805")
      (fields (field (name "VOLTAGE") "25V") (field (name "TOLERANCE") "10%"))
      (libsource (lib "Miscellaneous Devices") (part "b4654b650e69147ec39a6b967a45e02"))
    )
    (comp (ref "C80")
      (value "Cap Pol2")
      (footprint "Buck:C0805")
      (description "Polarized Capacitor (Axial)")
      (fields (field (name "ALTIUM_VALUE") "10uF") (field (name "PUBLISHER") "Altium Limited"))
      (libsource (lib "SCH") (part "Cap Pol2"))
    )
    (comp (ref "C81") (value "1nF-50V") (footprint "Buck:C0805") (libsource (lib "MYLIB") (part "CapSMD")))
    (comp (ref "C82")
      (value "Cap Pol2")
      (footprint "Buck:C0805")
      (description "Polarized Capacitor (Axial)")
      (fields (field (name "ALTIUM_VALUE") "10uF") (field (name "PUBLISHER") "Altium Limited"))
      (libsource (lib "SCH") (part "Cap Pol2"))
    )
    (comp (ref "C83")
      (value "100nF")
      (footprint "Buck:C0805")
      (description "None polar capacitor")
      (libsource (lib "Mylib") (part "Cap ceramic"))
    )
    (comp (ref "C84")
      (value "100pF")
      (footprint "Buck:C0805")
      (description "None polar capacitor")
      (libsource (lib "Mylib") (part "Cap ceramic"))
    )
    (comp (ref "C85")
      (value "100nF")
      (footprint "Buck:C0805")
      (description "None polar capacitor")
      (libsource (lib "Mylib") (part "Cap ceramic"))
    )
    (comp (ref "C86") (value "1nF-50V") (footprint "Buck:C0805") (libsource (lib "MYLIB") (part "CapSMD")))
    (comp (ref "C87")
      (value "100pF")
      (footprint "Buck:C0805")
      (description "None polar capacitor")
      (libsource (lib "Mylib") (part "Cap ceramic"))
    )
    (comp (ref "C88")
      (value "100nF")
      (footprint "Buck:C0805")
      (description "None polar capacitor")
      (libsource (lib "Mylib") (part "Cap ceramic"))
    )
    (comp (ref "CR1")
      (value "SMBJ48A")
      (footprint "Buck:SMB (DO-214AA)")
      (libsource (lib "MYLIB") (part "DiodeSMD4.5mm"))
    )
    (comp (ref "CR2")
      (value "SMBJ48A")
      (footprint "Buck:SMB (DO-214AA)")
      (libsource (lib "MYLIB") (part "DiodeSMD4.5mm"))
    )
    (comp (ref "CR3")
      (value "SMBJ48A")
      (footprint "Buck:SMB (DO-214AA)")
      (libsource (lib "MYLIB") (part "DiodeSMD4.5mm"))
    )
    (comp (ref "CR4")
      (value "SMBJ48A")
      (footprint "Buck:SMB (DO-214AA)")
      (libsource (lib "MYLIB") (part "DiodeSMD4.5mm"))
    )
    (comp (ref "CR5")
      (value "SMBJ48A")
      (footprint "Buck:SMB (DO-214AA)")
      (libsource (lib "MYLIB") (part "DiodeSMD4.5mm"))
    )
    (comp (ref "CR6")
      (value "SMBJ48A")
      (footprint "Buck:SMB (DO-214AA)")
      (libsource (lib "MYLIB") (part "DiodeSMD4.5mm"))
    )
    (comp (ref "CR7")
      (value "SMBJ48A")
      (footprint "Buck:SMB (DO-214AA)")
      (libsource (lib "MYLIB") (part "DiodeSMD4.5mm"))
    )
    (comp (ref "CR8")
      (value "SMBJ48A")
      (footprint "Buck:SMB (DO-214AA)")
      (libsource (lib "MYLIB") (part "DiodeSMD4.5mm"))
    )
    (comp (ref "CR9")
      (value "SMBJ48A")
      (footprint "Buck:SMB (DO-214AA)")
      (libsource (lib "MYLIB") (part "DiodeSMD4.5mm"))
    )
    (comp (ref "CR10")
      (value "SMBJ48A")
      (footprint "Buck:SMB (DO-214AA)")
      (libsource (lib "MYLIB") (part "DiodeSMD4.5mm"))
    )
    (comp (ref "CR11")
      (value "SMBJ48A")
      (footprint "Buck:SMB (DO-214AA)")
      (libsource (lib "MYLIB") (part "DiodeSMD4.5mm"))
    )
    (comp (ref "CR12")
      (value "SMBJ48A")
      (footprint "Buck:SMB (DO-214AA)")
      (libsource (lib "MYLIB") (part "DiodeSMD4.5mm"))
    )
    (comp (ref "CR13")
      (value "SMBJ48A")
      (footprint "Buck:SMB (DO-214AA)")
      (libsource (lib "MYLIB") (part "DiodeSMD4.5mm"))
    )
    (comp (ref "CR14")
      (value "SMBJ48A")
      (footprint "Buck:SMB (DO-214AA)")
      (libsource (lib "MYLIB") (part "DiodeSMD4.5mm"))
    )
    (comp (ref "CR15")
      (value "SMBJ48A")
      (footprint "Buck:SMB (DO-214AA)")
      (libsource (lib "MYLIB") (part "DiodeSMD4.5mm"))
    )
    (comp (ref "CR16")
      (value "SMBJ48A")
      (footprint "Buck:SMB (DO-214AA)")
      (libsource (lib "MYLIB") (part "DiodeSMD4.5mm"))
    )
    (comp (ref "CR17")
      (value "RFN10BM6STL")
      (footprint "Buck:RFN10BM")
      (libsource (lib "MYLIB") (part "DiodeSMD4.5mm"))
    )
    (comp (ref "CR18")
      (value "RFN10BM6STL")
      (footprint "Buck:RFN10BM")
      (libsource (lib "MYLIB") (part "DiodeSMD4.5mm"))
    )
    (comp (ref "D1")
      (value "KDZVTR39A")
      (footprint "Buck:SOD-123FL")
      (description "Zener Diode")
      (fields (field (name "PUBLISHER") "Altium Limited"))
      (libsource (lib "Miscellaneous Devices") (part "D Zener"))
    )
    (comp (ref "D2")
      (value "VSS8D5M12HM3/H")
      (footprint "Buck:DO-221AD")
      (description "Schottky Diode")
      (fields (field (name "PUBLISHER") "Altium Limited"))
      (libsource (lib "Miscellaneous Devices") (part "D Schottky"))
    )
    (comp (ref "D3")
      (value "1N4007-SMD")
      (footprint "Buck:SMA (DO-214AC)")
      (description "Diode Standard 1000V 1A Through Hole DO-204AL _DO-41_")
      (fields (field (name "MF") "ON Semiconductor") (field (name "MP") "1N4007"))
      (libsource (lib "Buck") (part "1N4007"))
    )
    (comp (ref "D4")
      (value "1N4007-SMD")
      (footprint "Buck:SMA (DO-214AC)")
      (description "Diode Standard 1000V 1A Through Hole DO-204AL _DO-41_")
      (fields (field (name "MF") "ON Semiconductor") (field (name "MP") "1N4007"))
      (libsource (lib "Buck") (part "1N4007"))
    )
    (comp (ref "D5")
      (value "1N4007-SMD")
      (footprint "Buck:SMA (DO-214AC)")
      (description "Diode Standard 1000V 1A Through Hole DO-204AL _DO-41_")
      (fields (field (name "MF") "ON Semiconductor") (field (name "MP") "1N4007"))
      (libsource (lib "Buck") (part "1N4007"))
    )
    (comp (ref "D6")
      (value "1N4007-SMD")
      (footprint "Buck:SMA (DO-214AC)")
      (description "Diode Standard 1000V 1A Through Hole DO-204AL _DO-41_")
      (fields (field (name "MF") "ON Semiconductor") (field (name "MP") "1N4007"))
      (libsource (lib "Buck") (part "1N4007"))
    )
    (comp (ref "D7")
      (value "KDZVTR39A")
      (footprint "Buck:SOD-123FL")
      (description "Zener Diode")
      (fields (field (name "PUBLISHER") "Altium Limited"))
      (libsource (lib "Miscellaneous Devices") (part "D Zener"))
    )
    (comp (ref "D8")
      (value "1N4007-SMD")
      (footprint "Buck:SMA (DO-214AC)")
      (description "Diode Standard 1000V 1A Through Hole DO-204AL _DO-41_")
      (fields (field (name "MF") "ON Semiconductor") (field (name "MP") "1N4007"))
      (libsource (lib "Buck") (part "1N4007"))
    )
    (comp (ref "D9")
      (value "KDZVTR39A")
      (footprint "Buck:SOD-123FL")
      (description "Zener Diode")
      (fields (field (name "PUBLISHER") "Altium Limited"))
      (libsource (lib "Miscellaneous Devices") (part "D Zener"))
    )
    (comp (ref "D10")
      (value "1N4007-SMD")
      (footprint "Buck:SMA (DO-214AC)")
      (description "Diode Standard 1000V 1A Through Hole DO-204AL _DO-41_")
      (fields (field (name "MF") "ON Semiconductor") (field (name "MP") "1N4007"))
      (libsource (lib "Buck") (part "1N4007"))
    )
    (comp (ref "D11")
      (value "1N4007-SMD")
      (footprint "Buck:SMA (DO-214AC)")
      (description "Diode Standard 1000V 1A Through Hole DO-204AL _DO-41_")
      (fields (field (name "MF") "ON Semiconductor") (field (name "MP") "1N4007"))
      (libsource (lib "Buck") (part "1N4007"))
    )
    (comp (ref "D12")
      (value "1N4007-SMD")
      (footprint "Buck:SMA (DO-214AC)")
      (description "Diode Standard 1000V 1A Through Hole DO-204AL _DO-41_")
      (fields (field (name "MF") "ON Semiconductor") (field (name "MP") "1N4007"))
      (libsource (lib "Buck") (part "1N4007"))
    )
    (comp (ref "D13")
      (value "1N4007-SMD")
      (footprint "Buck:SMA (DO-214AC)")
      (description "Diode Standard 1000V 1A Through Hole DO-204AL _DO-41_")
      (fields (field (name "MF") "ON Semiconductor") (field (name "MP") "1N4007"))
      (libsource (lib "Buck") (part "1N4007"))
    )
    (comp (ref "D14")
      (value "1N4007-SMD")
      (footprint "Buck:SMA (DO-214AC)")
      (description "Diode Standard 1000V 1A Through Hole DO-204AL _DO-41_")
      (fields (field (name "MF") "ON Semiconductor") (field (name "MP") "1N4007"))
      (libsource (lib "Buck") (part "1N4007"))
    )
    (comp (ref "D15")
      (value "1N4007-SMD")
      (footprint "Buck:SMA (DO-214AC)")
      (description "Diode Standard 1000V 1A Through Hole DO-204AL _DO-41_")
      (fields (field (name "MF") "ON Semiconductor") (field (name "MP") "1N4007"))
      (libsource (lib "Buck") (part "1N4007"))
    )
    (comp (ref "D16")
      (value "1N4007-SMD")
      (footprint "Buck:SMA (DO-214AC)")
      (description "Diode Standard 1000V 1A Through Hole DO-204AL _DO-41_")
      (fields (field (name "MF") "ON Semiconductor") (field (name "MP") "1N4007"))
      (libsource (lib "Buck") (part "1N4007"))
    )
    (comp (ref "D17")
      (value "KDZVTR39A")
      (footprint "Buck:SOD-123FL")
      (description "Zener Diode")
      (fields (field (name "PUBLISHER") "Altium Limited"))
      (libsource (lib "Miscellaneous Devices") (part "D Zener"))
    )
    (comp (ref "D18")
      (value "KDZVTR39A")
      (footprint "Buck:SOD-123FL")
      (description "Zener Diode")
      (fields (field (name "PUBLISHER") "Altium Limited"))
      (libsource (lib "Miscellaneous Devices") (part "D Zener"))
    )
    (comp (ref "D19")
      (value "1N4007-SMD")
      (footprint "Buck:SMA (DO-214AC)")
      (description "Diode Standard 1000V 1A Through Hole DO-204AL _DO-41_")
      (fields (field (name "MF") "ON Semiconductor") (field (name "MP") "1N4007"))
      (libsource (lib "Buck") (part "1N4007"))
    )
    (comp (ref "D20")
      (value "1N4007-SMD")
      (footprint "Buck:SMA (DO-214AC)")
      (description "Diode Standard 1000V 1A Through Hole DO-204AL _DO-41_")
      (fields (field (name "MF") "ON Semiconductor") (field (name "MP") "1N4007"))
      (libsource (lib "Buck") (part "1N4007"))
    )
    (comp (ref "D21")
      (value "1N4007-SMD")
      (footprint "Buck:SMA (DO-214AC)")
      (description "Diode Standard 1000V 1A Through Hole DO-204AL _DO-41_")
      (fields (field (name "MF") "ON Semiconductor") (field (name "MP") "1N4007"))
      (libsource (lib "Buck") (part "1N4007"))
    )
    (comp (ref "D22")
      (value "1N4007-SMD")
      (footprint "Buck:SMA (DO-214AC)")
      (description "Diode Standard 1000V 1A Through Hole DO-204AL _DO-41_")
      (fields (field (name "MF") "ON Semiconductor") (field (name "MP") "1N4007"))
      (libsource (lib "Buck") (part "1N4007"))
    )
    (comp (ref "DS1") (value "LED SMD") (footprint "Buck:LED0805") (libsource (lib "MYLIB") (part "LED SMD")))
    (comp (ref "DS2")
      (value "LED SMD")
      (footprint "Buck:LED0805")
      (description "Blue SURFACE MOUNT LED LAMP, -40 to +85 ,0805 SIZE")
      (fields (field (name "PART NUMBER") "QTLP630C-7"))
      (libsource (lib "kashizadeh_ali") (part "LED"))
    )
    (comp (ref "DS3")
      (value "LED SMD")
      (footprint "Buck:LED0805")
      (description "Blue SURFACE MOUNT LED LAMP, -40 to +85 ,0805 SIZE")
      (fields (field (name "PART NUMBER") "QTLP630C-7"))
      (libsource (lib "kashizadeh_ali") (part "LED"))
    )
    (comp (ref "DS4")
      (value "LED SMD")
      (footprint "Buck:LED0805")
      (description "Blue SURFACE MOUNT LED LAMP, -40 to +85 ,0805 SIZE")
      (fields (field (name "PART NUMBER") "QTLP630C-7"))
      (libsource (lib "kashizadeh_ali") (part "LED"))
    )
    (comp (ref "DS5")
      (value "LED SMD")
      (footprint "Buck:LED0805")
      (description "Blue SURFACE MOUNT LED LAMP, -40 to +85 ,0805 SIZE")
      (fields (field (name "PART NUMBER") "QTLP630C-7"))
      (libsource (lib "kashizadeh_ali") (part "LED"))
    )
    (comp (ref "DS6") (value "LED SMD") (footprint "Buck:LED0805") (libsource (lib "MYLIB") (part "LED SMD")))
    (comp (ref "DS7") (value "LED SMD") (footprint "Buck:LED0805") (libsource (lib "MYLIB") (part "LED SMD")))
    (comp (ref "DS8") (value "LED SMD") (footprint "Buck:LED0805") (libsource (lib "MYLIB") (part "LED SMD")))
    (comp (ref "DS9")
      (value "LED SMD")
      (footprint "Buck:LED0805")
      (description "Blue SURFACE MOUNT LED LAMP, -40 to +85 ,0805 SIZE")
      (fields (field (name "PART NUMBER") "QTLP630C-7"))
      (libsource (lib "kashizadeh_ali") (part "LED"))
    )
    (comp (ref "DS10") (value "LED") (footprint "Buck:LED0805") (libsource (lib "SCH") (part "LED")))
    (comp (ref "DS11")
      (value "LED SMD")
      (footprint "Buck:LED0805")
      (libsource (lib "MYLIB") (part "LED SMD"))
    )
    (comp (ref "DS12")
      (value "LED SMD")
      (footprint "Buck:LED0805")
      (description "Blue SURFACE MOUNT LED LAMP, -40 to +85 ,0805 SIZE")
      (fields (field (name "PART NUMBER") "QTLP630C-7"))
      (libsource (lib "kashizadeh_ali") (part "LED"))
    )
    (comp (ref "F1")
      (value "0031.8001 Fuse holder")
      (footprint "Buck:00318001")
      (description "Fuse")
      (fields (field (name "PUBLISHER") "Altium Limited"))
      (libsource (lib "Miscellaneous Devices") (part "Fuse 1"))
    )
    (comp (ref "F2")
      (value "0031.8001 Fuse holder")
      (footprint "Buck:00318001")
      (description "Fuse")
      (fields (field (name "PUBLISHER") "Altium Limited"))
      (libsource (lib "Miscellaneous Devices") (part "Fuse 1"))
    )
    (comp (ref "F3")
      (value "0031.8001 Fuse holder")
      (footprint "Buck:00318001")
      (description "Fuse")
      (fields (field (name "PUBLISHER") "Altium Limited"))
      (libsource (lib "Miscellaneous Devices") (part "Fuse 1"))
    )
    (comp (ref "F4")
      (value "0031.8001 Fuse holder")
      (footprint "Buck:00318001")
      (description "Fuse")
      (fields (field (name "PUBLISHER") "Altium Limited"))
      (libsource (lib "Miscellaneous Devices") (part "Fuse 1"))
    )
    (comp (ref "FB1")
      (value "FERRITE CHIP")
      (footprint "Buck:L0805")
      (libsource (lib "No_avaran") (part "FERRITE CHIP"))
    )
    (comp (ref "FB2")
      (value "FBMJ2125HS420-T")
      (footprint "Buck:L0805")
      (libsource (lib "No_avaran") (part "FERRITE CHIP"))
    )
    (comp (ref "FB3")
      (value "FERRITE CHIP")
      (footprint "Buck:L0805")
      (libsource (lib "No_avaran") (part "FERRITE CHIP"))
    )
    (comp (ref "FB4")
      (value "FERRITE CHIP")
      (footprint "Buck:L0805")
      (libsource (lib "No_avaran") (part "FERRITE CHIP"))
    )
    (comp (ref "FB5")
      (value "FERRITE CHIP")
      (footprint "Buck:L0805")
      (libsource (lib "No_avaran") (part "FERRITE CHIP"))
    )
    (comp (ref "FB6")
      (value "FERRITE CHIP")
      (footprint "Buck:L0805")
      (libsource (lib "No_avaran") (part "FERRITE CHIP"))
    )
    (comp (ref "FB7")
      (value "FERRITE CHIP")
      (footprint "Buck:L0805")
      (libsource (lib "No_avaran") (part "FERRITE CHIP"))
    )
    (comp (ref "FB8")
      (value "FERRITE CHIP")
      (footprint "Buck:L0805")
      (libsource (lib "No_avaran") (part "FERRITE CHIP"))
    )
    (comp (ref "FB9")
      (value "FERRITE CHIP")
      (footprint "Buck:L0805")
      (libsource (lib "No_avaran") (part "FERRITE CHIP"))
    )
    (comp (ref "FB10")
      (value "FERRITE CHIP")
      (footprint "Buck:L0805")
      (libsource (lib "No_avaran") (part "FERRITE CHIP"))
    )
    (comp (ref "FB11")
      (value "FERRITE CHIP")
      (footprint "Buck:L0805")
      (libsource (lib "No_avaran") (part "FERRITE CHIP"))
    )
    (comp (ref "FB12")
      (value "FBMJ2125HS420-T")
      (footprint "Buck:L0805")
      (libsource (lib "No_avaran") (part "FERRITE CHIP"))
    )
    (comp (ref "FB13")
      (value "FBMJ2125HS420-T")
      (footprint "Buck:L0805")
      (libsource (lib "No_avaran") (part "FERRITE CHIP"))
    )
    (comp (ref "HS1")
      (value "Full bridge Heatsink")
      (footprint "Buck:Full_bridge_Heatsink")
      (libsource (lib "Full bridge-V1.00") (part "Full_bridge_Heatsink"))
    )
    (comp (ref "HS2")
      (value "Full bridge Heatsink")
      (footprint "Buck:Full_bridge_Heatsink")
      (libsource (lib "Full bridge-V1.00") (part "Full_bridge_Heatsink"))
    )
    (comp (ref "J1")
      (value "691101710002")
      (footprint "Buck:691101710002")
      (description "WR-TBL Series 101 Horizontal Entry Modular, THT, pitch 5mm, 2p")
      (fields (field (name "MANUFACTURER") "Wurth Elektronik"))
      (libsource (lib "Altium_WR-TBL (rev22b)") (part "691101710002"))
    )
    (comp (ref "J2")
      (value "61802529221")
      (footprint "Buck:61802525123")
      (description "Male PCB Connector with Hex Screw WR-DSUB, Vertical, 25 pins")
      (fields (field (name "MANUFACTURER") "Wurth Elektronik") (field (name "PUBLISHER") "WurthElektronik"))
      (libsource (lib "Miscellaneous Connectors") (part "WE-CN-2S-2M-D25"))
    )
    (comp (ref "L1")
      (value "Inductor")
      (footprint "Buck:FullBridge_Inductor")
      (fields (field (name "ALTIUM_VALUE") "EPCOS ETD39 N87") (field (name "PUBLISHER") "Altium Limited"))
      (libsource (lib "Miscellaneous Devices") (part "Inductor"))
    )
    (comp (ref "P1")
      (value "280371-2")
      (footprint "Buck:TECO-280371-2_V")
      (fields (field (name "MANUFACTURER") "TE Connectivity"))
      (libsource (lib "Miscellaneous Devices") (part "CN-1P-M-R4"))
    )
    (comp (ref "P2")
      (value "691311400104")
      (footprint "Buck:691311400104")
      (description "Serie 3114 - 7.62mm Close Vertical PCB Header WR-TBL, 4 pin")
      (fields (field (name "MANUFACTURER") "Wurth Elektronik") (field (name "PUBLISHER") "WurthElektronik"))
      (libsource (lib "Miscellaneous Connectors") (part "WE-CN-1P-M-R4"))
    )
    (comp (ref "P3")
      (value "691311400104")
      (footprint "Buck:691311400104")
      (description "Serie 3114 - 7.62mm Close Vertical PCB Header WR-TBL, 4 pin")
      (fields (field (name "MANUFACTURER") "Wurth Elektronik") (field (name "PUBLISHER") "WurthElektronik"))
      (libsource (lib "") (part "WE-CN-1P-M-R4_1"))
    )
    (comp (ref "PS1")
      (value "REC5-2415SRWZ/H6/A")
      (footprint "Buck:REC52415SRWZH6A")
      (description "DC/DC-Converter, 2kV, 4kVDC & 6kVDC Isolation. Continuous Short Circuit Protection")
      (libsource (lib "REC5-2415SRWZ_H6_A") (part "REC5-2415SRWZ/H6/A"))
    )
    (comp (ref "PS2")
      (value "REC5-2415SRWZ/H6/A")
      (footprint "Buck:REC52415SRWZH6A")
      (description "DC/DC-Converter, 2kV, 4kVDC & 6kVDC Isolation. Continuous Short Circuit Protection")
      (libsource (lib "REC5-2415SRWZ_H6_A") (part "REC5-2415SRWZ/H6/A"))
    )
    (comp (ref "PS3")
      (value "REC5-2415SRWZ/H6/A")
      (footprint "Buck:REC52415SRWZH6A")
      (description "DC/DC-Converter, 2kV, 4kVDC & 6kVDC Isolation. Continuous Short Circuit Protection")
      (libsource (lib "REC5-2415SRWZ_H6_A") (part "REC5-2415SRWZ/H6/A"))
    )
    (comp (ref "PS4")
      (value "REC5-2415SRWZ/H6/A")
      (footprint "Buck:REC52415SRWZH6A")
      (description "DC/DC-Converter, 2kV, 4kVDC & 6kVDC Isolation. Continuous Short Circuit Protection")
      (libsource (lib "REC5-2415SRWZ_H6_A") (part "REC5-2415SRWZ/H6/A"))
    )
    (comp (ref "Q1")
      (value "IKW25N120CS7")
      (footprint "Buck:PG-TO247-3")
      (fields (field (name "MANUFACTURER") "Infineon") (field (name "PARTNUMBER") "IKW40N120H3"))
      (libsource (lib "Miscellaneous Devices") (part "INF-IXXXXXXX-PG-TO220_247-3_1"))
    )
    (comp (ref "Q2")
      (value "IKW25N120CS7")
      (footprint "Buck:PG-TO247-3")
      (fields (field (name "MANUFACTURER") "Infineon") (field (name "PARTNUMBER") "IKW40N120H3"))
      (libsource (lib "Miscellaneous Devices") (part "INF-IXXXXXXX-PG-TO220_247-3_1"))
    )
    (comp (ref "Q3")
      (value "IKW25N120CS7")
      (footprint "Buck:PG-TO247-3")
      (fields (field (name "MANUFACTURER") "Infineon") (field (name "PARTNUMBER") "IKW40N120H3"))
      (libsource (lib "Miscellaneous Devices") (part "INF-IXXXXXXX-PG-TO220_247-3_1"))
    )
    (comp (ref "Q4")
      (value "IKW25N120CS7")
      (footprint "Buck:PG-TO247-3")
      (fields (field (name "MANUFACTURER") "Infineon") (field (name "PARTNUMBER") "IKW40N120H3"))
      (libsource (lib "Miscellaneous Devices") (part "INF-IXXXXXXX-PG-TO220_247-3_1"))
    )
    (comp (ref "Q5")
      (value "ACPL-C87A-500E")
      (footprint "Buck:FP-SSO-8-MFG")
      (description "IC OPAMP ISOLATION 100KHZ 8SO")
      (libsource (lib "Miscellaneous Devices") (part "b42ed144594ce334135a4fb1ded0a30"))
    )
    (comp (ref "R1") (value "15K") (footprint "Buck:R0805") (libsource (lib "MYLIB") (part "ResSMD")))
    (comp (ref "R2") (value "ResSMD") (footprint "Buck:R0805") (libsource (lib "MYLIB") (part "ResSMD")))
    (comp (ref "R3")
      (value "Res3")
      (footprint "Buck:R0603")
      (description "Resistor")
      (fields (field (name "ALTIUM_VALUE") "0") (field (name "PUBLISHER") "Altium Limited"))
      (libsource (lib "Miscellaneous Devices") (part "Res3"))
    )
    (comp (ref "R4")
      (value "Res3")
      (footprint "Buck:R0603")
      (description "Resistor")
      (fields (field (name "ALTIUM_VALUE") "0") (field (name "PUBLISHER") "Altium Limited"))
      (libsource (lib "Miscellaneous Devices") (part "Res3"))
    )
    (comp (ref "R5") (value "300") (footprint "Buck:R0805") (libsource (lib "MYLIB") (part "ResSMD")))
    (comp (ref "R6")
      (value "Res3")
      (footprint "Buck:R0603")
      (description "Resistor")
      (fields (field (name "ALTIUM_VALUE") "0") (field (name "PUBLISHER") "Altium Limited"))
      (libsource (lib "Miscellaneous Devices") (part "Res3"))
    )
    (comp (ref "R7")
      (value "12")
      (footprint "Buck:MELF 0204")
      (description "Semiconductor Resistor")
      (fields (field (name "ALTIUM_VALUE") "CMA02040X1209GB300") (field (name "PUBLISHER") "Altium Limited"))
      (libsource (lib "Miscellaneous Devices") (part "Res Semi"))
    )
    (comp (ref "R8")
      (value "Res3")
      (footprint "Buck:R0603")
      (description "Resistor")
      (fields (field (name "ALTIUM_VALUE") "0") (field (name "PUBLISHER") "Altium Limited"))
      (libsource (lib "Miscellaneous Devices") (part "Res3"))
    )
    (comp (ref "R9")
      (value "12")
      (footprint "Buck:MELF 0204")
      (description "Semiconductor Resistor")
      (fields (field (name "ALTIUM_VALUE") "CMA02040X1209GB300") (field (name "PUBLISHER") "Altium Limited"))
      (libsource (lib "Miscellaneous Devices") (part "Res Semi"))
    )
    (comp (ref "R10") (value "1K") (footprint "Buck:R0805") (libsource (lib "MYLIB") (part "ResSMD")))
    (comp (ref "R11") (value "ResSMD") (footprint "Buck:R0805") (libsource (lib "MYLIB") (part "ResSMD")))
    (comp (ref "R12")
      (value "Res3")
      (footprint "Buck:R0603")
      (description "Resistor")
      (fields (field (name "ALTIUM_VALUE") "0") (field (name "PUBLISHER") "Altium Limited"))
      (libsource (lib "Miscellaneous Devices") (part "Res3"))
    )
    (comp (ref "R13")
      (value "CMA02040X1209GB300")
      (footprint "Buck:MMF50S")
      (description "Resistor")
      (fields (field (name "ALTIUM_VALUE") "1") (field (name "PUBLISHER") "Altium Limited"))
      (libsource (lib "Miscellaneous Devices") (part "Res1"))
    )
    (comp (ref "R14") (value "ResSMD") (footprint "Buck:R0805") (libsource (lib "MYLIB") (part "ResSMD")))
    (comp (ref "R15") (value "ResSMD") (footprint "Buck:R0805") (libsource (lib "MYLIB") (part "ResSMD")))
    (comp (ref "R16")
      (value "Res3")
      (footprint "Buck:R0603")
      (description "Resistor")
      (fields (field (name "ALTIUM_VALUE") "0") (field (name "PUBLISHER") "Altium Limited"))
      (libsource (lib "Miscellaneous Devices") (part "Res3"))
    )
    (comp (ref "R17") (value "0") (footprint "Buck:R0805") (libsource (lib "MYLIB") (part "ResSMD")))
    (comp (ref "R18")
      (value "Res1")
      (footprint "Buck:R0805")
      (description "Resistor")
      (fields (field (name "ALTIUM_VALUE") "1") (field (name "PUBLISHER") "Altium Limited"))
      (libsource (lib "Miscellaneous Devices") (part "Res1"))
    )
    (comp (ref "R19")
      (value "CMA02040X1209GB300")
      (footprint "Buck:MELF 0204")
      (description "Resistor")
      (fields (field (name "PUBLISHER") "Altium Limited"))
      (libsource (lib "Miscellaneous Devices") (part "Res1"))
    )
    (comp (ref "R20")
      (value "Res3")
      (footprint "Buck:R0603")
      (description "Resistor")
      (fields (field (name "ALTIUM_VALUE") "0") (field (name "PUBLISHER") "Altium Limited"))
      (libsource (lib "Miscellaneous Devices") (part "Res3"))
    )
    (comp (ref "R21")
      (value "Res3")
      (footprint "Buck:R0603")
      (description "Resistor")
      (fields (field (name "ALTIUM_VALUE") "0") (field (name "PUBLISHER") "Altium Limited"))
      (libsource (lib "Miscellaneous Devices") (part "Res3"))
    )
    (comp (ref "R22")
      (value "CMA02040X1209GB300")
      (footprint "Buck:MMF50S")
      (description "Resistor")
      (fields (field (name "ALTIUM_VALUE") "1") (field (name "PUBLISHER") "Altium Limited"))
      (libsource (lib "Miscellaneous Devices") (part "Res1"))
    )
    (comp (ref "R23") (value "5K") (footprint "Buck:R0805") (libsource (lib "MYLIB") (part "ResSMD")))
    (comp (ref "R24") (value "ResSMD") (footprint "Buck:R0805") (libsource (lib "MYLIB") (part "ResSMD")))
    (comp (ref "R25")
      (value "Res3")
      (footprint "Buck:R0603")
      (description "Resistor")
      (fields (field (name "ALTIUM_VALUE") "10K") (field (name "PUBLISHER") "Altium Limited"))
      (libsource (lib "Miscellaneous Devices") (part "Res3"))
    )
    (comp (ref "R26") (value "5K") (footprint "Buck:R0805") (libsource (lib "MYLIB") (part "ResSMD")))
    (comp (ref "R27") (value "5K") (footprint "Buck:R0805") (libsource (lib "MYLIB") (part "ResSMD")))
    (comp (ref "R28") (value "1K") (footprint "Buck:R0805") (libsource (lib "MYLIB") (part "ResSMD")))
    (comp (ref "R29")
      (value "Res3")
      (footprint "Buck:R0603")
      (description "Resistor")
      (fields (field (name "ALTIUM_VALUE") "10K") (field (name "PUBLISHER") "Altium Limited"))
      (libsource (lib "Miscellaneous Devices") (part "Res3"))
    )
    (comp (ref "R30")
      (value "47k")
      (footprint "Buck:R0805")
      (description "Resistor")
      (fields (field (name "ALTIUM_VALUE") "47k") (field (name "PUBLISHER") "Altium Limited"))
      (libsource (lib "Miscellaneous Devices") (part "Res1"))
    )
    (comp (ref "R31")
      (value "15")
      (footprint "Buck:AXIAL-0.5")
      (description "Semiconductor Resistor")
      (fields (field (name "ALTIUM_VALUE") "0.5W") (field (name "PUBLISHER") "Altium Limited"))
      (libsource (lib "Miscellaneous Devices") (part "Res Semi"))
    )
    (comp (ref "R32")
      (value "15")
      (footprint "Buck:AXIAL-0.5")
      (description "Semiconductor Resistor")
      (fields (field (name "ALTIUM_VALUE") "0.5W") (field (name "PUBLISHER") "Altium Limited"))
      (libsource (lib "Miscellaneous Devices") (part "Res Semi"))
    )
    (comp (ref "R33") (value "100") (footprint "Buck:R0805") (libsource (lib "MYLIB") (part "ResSMD")))
    (comp (ref "R34") (value "100") (footprint "Buck:R0805") (libsource (lib "MYLIB") (part "ResSMD")))
    (comp (ref "R35")
      (value "CMA02040X1209GB300")
      (footprint "Buck:MMF50S")
      (description "Resistor")
      (fields (field (name "ALTIUM_VALUE") "???") (field (name "PUBLISHER") "Altium Limited"))
      (libsource (lib "Miscellaneous Devices") (part "Res1"))
    )
    (comp (ref "R36")
      (value "CMA02040X1209GB300")
      (footprint "Buck:MMF50S")
      (description "Resistor")
      (fields (field (name "ALTIUM_VALUE") "???") (field (name "PUBLISHER") "Altium Limited"))
      (libsource (lib "Miscellaneous Devices") (part "Res1"))
    )
    (comp (ref "R37")
      (value "12")
      (footprint "Buck:MELF 0204")
      (description "Semiconductor Resistor")
      (fields (field (name "ALTIUM_VALUE") "CMA02040X1209GB300") (field (name "PUBLISHER") "Altium Limited"))
      (libsource (lib "Miscellaneous Devices") (part "Res Semi"))
    )
    (comp (ref "R38")
      (value "100k")
      (footprint "Buck:AXIAL0.9-VR68")
      (description "Semiconductor Resistor")
      (fields (field (name "ALTIUM_VALUE") "0.5W") (field (name "PUBLISHER") "Altium Limited"))
      (libsource (lib "Miscellaneous Devices") (part "Res Semi"))
    )
    (comp (ref "R39")
      (value "100k")
      (footprint "Buck:AXIAL0.9-VR68")
      (description "Semiconductor Resistor")
      (fields (field (name "ALTIUM_VALUE") "0.5W") (field (name "PUBLISHER") "Altium Limited"))
      (libsource (lib "Miscellaneous Devices") (part "Res Semi"))
    )
    (comp (ref "R40")
      (value "Res3")
      (footprint "Buck:R0603")
      (description "Resistor")
      (fields (field (name "ALTIUM_VALUE") "0") (field (name "PUBLISHER") "Altium Limited"))
      (libsource (lib "Miscellaneous Devices") (part "Res3"))
    )
    (comp (ref "R41")
      (value "12")
      (footprint "Buck:MELF 0204")
      (description "Semiconductor Resistor")
      (fields (field (name "ALTIUM_VALUE") "CMA02040X1209GB300") (field (name "PUBLISHER") "Altium Limited"))
      (libsource (lib "Miscellaneous Devices") (part "Res Semi"))
    )
    (comp (ref "R42")
      (value "100k")
      (footprint "Buck:AXIAL0.9-VR68")
      (description "Semiconductor Resistor")
      (fields (field (name "ALTIUM_VALUE") "0.5W") (field (name "PUBLISHER") "Altium Limited"))
      (libsource (lib "Miscellaneous Devices") (part "Res Semi"))
    )
    (comp (ref "R43")
      (value "100k")
      (footprint "Buck:AXIAL0.9-VR68")
      (description "Semiconductor Resistor")
      (fields (field (name "ALTIUM_VALUE") "0.5W") (field (name "PUBLISHER") "Altium Limited"))
      (libsource (lib "Miscellaneous Devices") (part "Res Semi"))
    )
    (comp (ref "R44") (value "ResSMD") (footprint "Buck:R0805") (libsource (lib "MYLIB") (part "ResSMD")))
    (comp (ref "R45")
      (value "Res3")
      (footprint "Buck:R0603")
      (description "Resistor")
      (fields (field (name "ALTIUM_VALUE") "0") (field (name "PUBLISHER") "Altium Limited"))
      (libsource (lib "Miscellaneous Devices") (part "Res3"))
    )
    (comp (ref "R46")
      (value "CMA02040X1209GB300")
      (footprint "Buck:MMF50S")
      (description "Resistor")
      (fields (field (name "ALTIUM_VALUE") "1") (field (name "PUBLISHER") "Altium Limited"))
      (libsource (lib "Miscellaneous Devices") (part "Res1"))
    )
    (comp (ref "R47")
      (value "Res3")
      (footprint "Buck:R0603")
      (description "Resistor")
      (fields (field (name "ALTIUM_VALUE") "0") (field (name "PUBLISHER") "Altium Limited"))
      (libsource (lib "Miscellaneous Devices") (part "Res3"))
    )
    (comp (ref "R48") (value "0") (footprint "Buck:R0805") (libsource (lib "MYLIB") (part "ResSMD")))
    (comp (ref "R49")
      (value "Res1")
      (footprint "Buck:R0805")
      (description "Resistor")
      (fields (field (name "ALTIUM_VALUE") "1") (field (name "PUBLISHER") "Altium Limited"))
      (libsource (lib "Miscellaneous Devices") (part "Res1"))
    )
    (comp (ref "R50")
      (value "CMA02040X1209GB300")
      (footprint "Buck:MELF 0204")
      (description "Resistor")
      (fields (field (name "PUBLISHER") "Altium Limited"))
      (libsource (lib "Miscellaneous Devices") (part "Res1"))
    )
    (comp (ref "R51")
      (value "Res3")
      (footprint "Buck:R0603")
      (description "Resistor")
      (fields (field (name "ALTIUM_VALUE") "0") (field (name "PUBLISHER") "Altium Limited"))
      (libsource (lib "Miscellaneous Devices") (part "Res3"))
    )
    (comp (ref "R52")
      (value "15")
      (footprint "Buck:AXIAL-0.5")
      (description "Semiconductor Resistor")
      (fields (field (name "ALTIUM_VALUE") "0.5W") (field (name "PUBLISHER") "Altium Limited"))
      (libsource (lib "Miscellaneous Devices") (part "Res Semi"))
    )
    (comp (ref "R53")
      (value "Res3")
      (footprint "Buck:R0603")
      (description "Resistor")
      (fields (field (name "ALTIUM_VALUE") "0") (field (name "PUBLISHER") "Altium Limited"))
      (libsource (lib "Miscellaneous Devices") (part "Res3"))
    )
    (comp (ref "R54")
      (value "15")
      (footprint "Buck:AXIAL-0.5")
      (description "Semiconductor Resistor")
      (fields (field (name "ALTIUM_VALUE") "0.5W") (field (name "PUBLISHER") "Altium Limited"))
      (libsource (lib "Miscellaneous Devices") (part "Res Semi"))
    )
    (comp (ref "R55")
      (value "CMA02040X1209GB300")
      (footprint "Buck:MMF50S")
      (description "Resistor")
      (fields (field (name "ALTIUM_VALUE") "1") (field (name "PUBLISHER") "Altium Limited"))
      (libsource (lib "Miscellaneous Devices") (part "Res1"))
    )
    (comp (ref "R56") (value "5K") (footprint "Buck:R0805") (libsource (lib "MYLIB") (part "ResSMD")))
    (comp (ref "R57") (value "100") (footprint "Buck:R0805") (libsource (lib "MYLIB") (part "ResSMD")))
    (comp (ref "R58") (value "100") (footprint "Buck:R0805") (libsource (lib "MYLIB") (part "ResSMD")))
    (comp (ref "R59")
      (value "Res3")
      (footprint "Buck:R0603")
      (description "Resistor")
      (fields (field (name "ALTIUM_VALUE") "10K") (field (name "PUBLISHER") "Altium Limited"))
      (libsource (lib "Miscellaneous Devices") (part "Res3"))
    )
    (comp (ref "R60") (value "5K") (footprint "Buck:R0805") (libsource (lib "MYLIB") (part "ResSMD")))
    (comp (ref "R61") (value "5K") (footprint "Buck:R0805") (libsource (lib "MYLIB") (part "ResSMD")))
    (comp (ref "R62") (value "1K") (footprint "Buck:R0805") (libsource (lib "MYLIB") (part "ResSMD")))
    (comp (ref "R63")
      (value "Res3")
      (footprint "Buck:R0603")
      (description "Resistor")
      (fields (field (name "ALTIUM_VALUE") "10K") (field (name "PUBLISHER") "Altium Limited"))
      (libsource (lib "Miscellaneous Devices") (part "Res3"))
    )
    (comp (ref "R64")
      (value "47k")
      (footprint "Buck:R0805")
      (description "Resistor")
      (fields (field (name "ALTIUM_VALUE") "47k") (field (name "PUBLISHER") "Altium Limited"))
      (libsource (lib "Miscellaneous Devices") (part "Res1"))
    )
    (comp (ref "R65")
      (value "CMA02040X1209GB300")
      (footprint "Buck:MMF50S")
      (description "Resistor")
      (fields (field (name "ALTIUM_VALUE") "???") (field (name "PUBLISHER") "Altium Limited"))
      (libsource (lib "Miscellaneous Devices") (part "Res1"))
    )
    (comp (ref "R66")
      (value "CMA02040X1209GB300")
      (footprint "Buck:MMF50S")
      (description "Resistor")
      (fields (field (name "ALTIUM_VALUE") "???") (field (name "PUBLISHER") "Altium Limited"))
      (libsource (lib "Miscellaneous Devices") (part "Res1"))
    )
    (comp (ref "R67")
      (value "12")
      (footprint "Buck:MELF 0204")
      (description "Semiconductor Resistor")
      (fields (field (name "ALTIUM_VALUE") "CMA02040X1209GB300") (field (name "PUBLISHER") "Altium Limited"))
      (libsource (lib "Miscellaneous Devices") (part "Res Semi"))
    )
    (comp (ref "R68")
      (value "Res3")
      (footprint "Buck:R0603")
      (description "Resistor")
      (fields (field (name "ALTIUM_VALUE") "0") (field (name "PUBLISHER") "Altium Limited"))
      (libsource (lib "Miscellaneous Devices") (part "Res3"))
    )
    (comp (ref "R69")
      (value "12")
      (footprint "Buck:MELF 0204")
      (description "Semiconductor Resistor")
      (fields (field (name "ALTIUM_VALUE") "CMA02040X1209GB300") (field (name "PUBLISHER") "Altium Limited"))
      (libsource (lib "Miscellaneous Devices") (part "Res Semi"))
    )
    (comp (ref "R70") (value "ResSMD") (footprint "Buck:R0805") (libsource (lib "MYLIB") (part "ResSMD")))
    (comp (ref "R71")
      (value "Res3")
      (footprint "Buck:R0603")
      (description "Resistor")
      (fields (field (name "ALTIUM_VALUE") "0") (field (name "PUBLISHER") "Altium Limited"))
      (libsource (lib "Miscellaneous Devices") (part "Res3"))
    )
    (comp (ref "R72")
      (value "CMA02040X1209GB300")
      (footprint "Buck:MMF50S")
      (description "Resistor")
      (fields (field (name "ALTIUM_VALUE") "1") (field (name "PUBLISHER") "Altium Limited"))
      (libsource (lib "Miscellaneous Devices") (part "Res1"))
    )
    (comp (ref "R73")
      (value "Res3")
      (footprint "Buck:R0603")
      (description "Resistor")
      (fields (field (name "ALTIUM_VALUE") "0") (field (name "PUBLISHER") "Altium Limited"))
      (libsource (lib "Miscellaneous Devices") (part "Res3"))
    )
    (comp (ref "R74") (value "0") (footprint "Buck:R0805") (libsource (lib "MYLIB") (part "ResSMD")))
    (comp (ref "R75")
      (value "Res1")
      (footprint "Buck:R0805")
      (description "Resistor")
      (fields (field (name "ALTIUM_VALUE") "1") (field (name "PUBLISHER") "Altium Limited"))
      (libsource (lib "Miscellaneous Devices") (part "Res1"))
    )
    (comp (ref "R76")
      (value "CMA02040X1209GB300")
      (footprint "Buck:MELF 0204")
      (description "Resistor")
      (fields (field (name "PUBLISHER") "Altium Limited"))
      (libsource (lib "Miscellaneous Devices") (part "Res1"))
    )
    (comp (ref "R77")
      (value "Res3")
      (footprint "Buck:R0603")
      (description "Resistor")
      (fields (field (name "ALTIUM_VALUE") "0") (field (name "PUBLISHER") "Altium Limited"))
      (libsource (lib "Miscellaneous Devices") (part "Res3"))
    )
    (comp (ref "R78")
      (value "Res3")
      (footprint "Buck:R0603")
      (description "Resistor")
      (fields (field (name "ALTIUM_VALUE") "0") (field (name "PUBLISHER") "Altium Limited"))
      (libsource (lib "Miscellaneous Devices") (part "Res3"))
    )
    (comp (ref "R79")
      (value "CMA02040X1209GB300")
      (footprint "Buck:MMF50S")
      (description "Resistor")
      (fields (field (name "ALTIUM_VALUE") "1") (field (name "PUBLISHER") "Altium Limited"))
      (libsource (lib "Miscellaneous Devices") (part "Res1"))
    )
    (comp (ref "R80") (value "5K") (footprint "Buck:R0805") (libsource (lib "MYLIB") (part "ResSMD")))
    (comp (ref "R81")
      (value "Res3")
      (footprint "Buck:R0603")
      (description "Resistor")
      (fields (field (name "ALTIUM_VALUE") "10K") (field (name "PUBLISHER") "Altium Limited"))
      (libsource (lib "Miscellaneous Devices") (part "Res3"))
    )
    (comp (ref "R82") (value "5K") (footprint "Buck:R0805") (libsource (lib "MYLIB") (part "ResSMD")))
    (comp (ref "R83") (value "5K") (footprint "Buck:R0805") (libsource (lib "MYLIB") (part "ResSMD")))
    (comp (ref "R84") (value "1K") (footprint "Buck:R0805") (libsource (lib "MYLIB") (part "ResSMD")))
    (comp (ref "R85")
      (value "Res3")
      (footprint "Buck:R0603")
      (description "Resistor")
      (fields (field (name "ALTIUM_VALUE") "10K") (field (name "PUBLISHER") "Altium Limited"))
      (libsource (lib "Miscellaneous Devices") (part "Res3"))
    )
    (comp (ref "R86")
      (value "47k")
      (footprint "Buck:R0805")
      (description "Resistor")
      (fields (field (name "ALTIUM_VALUE") "47k") (field (name "PUBLISHER") "Altium Limited"))
      (libsource (lib "Miscellaneous Devices") (part "Res1"))
    )
    (comp (ref "R87") (value "15K") (footprint "Buck:R0805") (libsource (lib "MYLIB") (part "ResSMD")))
    (comp (ref "R88") (value "15K") (footprint "Buck:R0805") (libsource (lib "MYLIB") (part "ResSMD")))
    (comp (ref "R89")
      (value "12")
      (footprint "Buck:MELF 0204")
      (description "Semiconductor Resistor")
      (fields (field (name "ALTIUM_VALUE") "CMA02040X1209GB300") (field (name "PUBLISHER") "Altium Limited"))
      (libsource (lib "Miscellaneous Devices") (part "Res Semi"))
    )
    (comp (ref "R90")
      (value "Res3")
      (footprint "Buck:R0603")
      (description "Resistor")
      (fields (field (name "ALTIUM_VALUE") "0") (field (name "PUBLISHER") "Altium Limited"))
      (libsource (lib "Miscellaneous Devices") (part "Res3"))
    )
    (comp (ref "R91")
      (value "12")
      (footprint "Buck:MELF 0204")
      (description "Semiconductor Resistor")
      (fields (field (name "ALTIUM_VALUE") "CMA02040X1209GB300") (field (name "PUBLISHER") "Altium Limited"))
      (libsource (lib "Miscellaneous Devices") (part "Res Semi"))
    )
    (comp (ref "R94") (value "15K") (footprint "Buck:R0805") (libsource (lib "MYLIB") (part "ResSMD")))
    (comp (ref "R95") (value "ResSMD") (footprint "Buck:R0805") (libsource (lib "MYLIB") (part "ResSMD")))
    (comp (ref "R96")
      (value "Res3")
      (footprint "Buck:R0603")
      (description "Resistor")
      (fields (field (name "ALTIUM_VALUE") "0") (field (name "PUBLISHER") "Altium Limited"))
      (libsource (lib "Miscellaneous Devices") (part "Res3"))
    )
    (comp (ref "R97")
      (value "CMA02040X1209GB300")
      (footprint "Buck:MMF50S")
      (description "Resistor")
      (fields (field (name "ALTIUM_VALUE") "1") (field (name "PUBLISHER") "Altium Limited"))
      (libsource (lib "Miscellaneous Devices") (part "Res1"))
    )
    (comp (ref "R98") (value "10K") (footprint "Buck:R0805") (libsource (lib "MYLIB") (part "ResSMD")))
    (comp (ref "R99") (value "10K") (footprint "Buck:R0805") (libsource (lib "MYLIB") (part "ResSMD")))
    (comp (ref "R100") (value "10K") (footprint "Buck:R0805") (libsource (lib "MYLIB") (part "ResSMD")))
    (comp (ref "R101") (value "10K") (footprint "Buck:R0805") (libsource (lib "MYLIB") (part "ResSMD")))
    (comp (ref "R102") (value "10K") (footprint "Buck:R0805") (libsource (lib "MYLIB") (part "ResSMD")))
    (comp (ref "R103") (value "10K") (footprint "Buck:R0805") (libsource (lib "MYLIB") (part "ResSMD")))
    (comp (ref "R104") (value "10K") (footprint "Buck:R0805") (libsource (lib "MYLIB") (part "ResSMD")))
    (comp (ref "R105") (value "10K") (footprint "Buck:R0805") (libsource (lib "MYLIB") (part "ResSMD")))
    (comp (ref "R106")
      (value "Res3")
      (footprint "Buck:R0603")
      (description "Resistor")
      (fields (field (name "ALTIUM_VALUE") "0") (field (name "PUBLISHER") "Altium Limited"))
      (libsource (lib "Miscellaneous Devices") (part "Res3"))
    )
    (comp (ref "R107") (value "0") (footprint "Buck:R0805") (libsource (lib "MYLIB") (part "ResSMD")))
    (comp (ref "R108")
      (value "Res1")
      (footprint "Buck:R0805")
      (description "Resistor")
      (fields (field (name "ALTIUM_VALUE") "1") (field (name "PUBLISHER") "Altium Limited"))
      (libsource (lib "Miscellaneous Devices") (part "Res1"))
    )
    (comp (ref "R109")
      (value "CMA02040X1209GB300")
      (footprint "Buck:MELF 0204")
      (description "Resistor")
      (fields (field (name "PUBLISHER") "Altium Limited"))
      (libsource (lib "Miscellaneous Devices") (part "Res1"))
    )
    (comp (ref "R110")
      (value "Res3")
      (footprint "Buck:R0603")
      (description "Resistor")
      (fields (field (name "ALTIUM_VALUE") "0") (field (name "PUBLISHER") "Altium Limited"))
      (libsource (lib "Miscellaneous Devices") (part "Res3"))
    )
    (comp (ref "R111")
      (value "Res3")
      (footprint "Buck:R0603")
      (description "Resistor")
      (fields (field (name "ALTIUM_VALUE") "0") (field (name "PUBLISHER") "Altium Limited"))
      (libsource (lib "Miscellaneous Devices") (part "Res3"))
    )
    (comp (ref "R112")
      (value "CMA02040X1209GB300")
      (footprint "Buck:MMF50S")
      (description "Resistor")
      (fields (field (name "ALTIUM_VALUE") "1") (field (name "PUBLISHER") "Altium Limited"))
      (libsource (lib "Miscellaneous Devices") (part "Res1"))
    )
    (comp (ref "R113") (value "5K") (footprint "Buck:R0805") (libsource (lib "MYLIB") (part "ResSMD")))
    (comp (ref "R114")
      (value "Res3")
      (footprint "Buck:R0603")
      (description "Resistor")
      (fields (field (name "ALTIUM_VALUE") "10K") (field (name "PUBLISHER") "Altium Limited"))
      (libsource (lib "Miscellaneous Devices") (part "Res3"))
    )
    (comp (ref "R115") (value "5K") (footprint "Buck:R0805") (libsource (lib "MYLIB") (part "ResSMD")))
    (comp (ref "R116") (value "5K") (footprint "Buck:R0805") (libsource (lib "MYLIB") (part "ResSMD")))
    (comp (ref "R117") (value "1K") (footprint "Buck:R0805") (libsource (lib "MYLIB") (part "ResSMD")))
    (comp (ref "R118")
      (value "Res3")
      (footprint "Buck:R0603")
      (description "Resistor")
      (fields (field (name "ALTIUM_VALUE") "10K") (field (name "PUBLISHER") "Altium Limited"))
      (libsource (lib "Miscellaneous Devices") (part "Res3"))
    )
    (comp (ref "R119") (value "15K") (footprint "Buck:R0805") (libsource (lib "MYLIB") (part "ResSMD")))
    (comp (ref "R120")
      (value "47k")
      (footprint "Buck:R0805")
      (description "Resistor")
      (fields (field (name "ALTIUM_VALUE") "47k") (field (name "PUBLISHER") "Altium Limited"))
      (libsource (lib "Miscellaneous Devices") (part "Res1"))
    )
    (comp (ref "R121")
      (value "1K")
      (footprint "Buck:R0805")
      (description "resistor 1/4 wat")
      (libsource (lib "Mylib") (part "Res"))
    )
    (comp (ref "R122") (value "1K") (footprint "Buck:R0805") (libsource (lib "MYLIB") (part "ResSMD")))
    (comp (ref "R123")
      (value "Res3")
      (footprint "Buck:R0603")
      (description "Resistor")
      (fields (field (name "ALTIUM_VALUE") "0") (field (name "PUBLISHER") "Altium Limited"))
      (libsource (lib "Miscellaneous Devices") (part "Res3"))
    )
    (comp (ref "R124")
      (value "Res3")
      (footprint "Buck:R0603")
      (description "Resistor")
      (fields (field (name "ALTIUM_VALUE") "0") (field (name "PUBLISHER") "Altium Limited"))
      (libsource (lib "Miscellaneous Devices") (part "Res3"))
    )
    (comp (ref "R125")
      (value "MOVS2825V420")
      (footprint "Buck:MOVS2825V420")
      (description "Varistor (Voltage-Sensitive Resistor)")
      (fields (field (name "PUBLISHER") "Altium Limited"))
      (libsource (lib "Miscellaneous Devices") (part "Res Varistor"))
    )
    (comp (ref "R126")
      (value "0")
      (footprint "Buck:R0603")
      (description "RES Thick Film, 2kΩ, 1%, 0.25W, 100ppm/°C, 1206")
      (fields (field (name "TOLERANCE") "1%"))
      (libsource (lib "Miscellaneous Devices") (part "1029c3af85768c4190bb7ad29bc67b5"))
    )
    (comp (ref "R127")
      (value "15k")
      (footprint "Buck:R0603")
      (description "RES Thick Film, 2kΩ, 1%, 0.25W, 100ppm/°C, 1206")
      (fields (field (name "TOLERANCE") "1%"))
      (libsource (lib "Miscellaneous Devices") (part "1029c3af85768c4190bb7ad29bc67b5"))
    )
    (comp (ref "R129")
      (value "4.7k")
      (footprint "Buck:R0805")
      (description "RES Thick Film, 2kΩ, 1%, 0.25W, 100ppm/°C, 1206")
      (fields (field (name "TOLERANCE") "1%"))
      (libsource (lib "Miscellaneous Devices") (part "1029c3af85768c4190bb7ad29bc67b5"))
    )
    (comp (ref "R130")
      (value "4.7k")
      (footprint "Buck:R0805")
      (description "RES Thick Film, 2kΩ, 1%, 0.25W, 100ppm/°C, 1206")
      (fields (field (name "TOLERANCE") "1%"))
      (libsource (lib "Miscellaneous Devices") (part "1029c3af85768c4190bb7ad29bc67b5"))
    )
    (comp (ref "R131") (value "100") (footprint "Buck:R0805") (libsource (lib "MYLIB") (part "ResSMD")))
    (comp (ref "R132")
      (value "4.7k")
      (footprint "Buck:R0805")
      (description "RES Thick Film, 2kΩ, 1%, 0.25W, 100ppm/°C, 1206")
      (fields (field (name "TOLERANCE") "1%"))
      (libsource (lib "Miscellaneous Devices") (part "1029c3af85768c4190bb7ad29bc67b5"))
    )
    (comp (ref "R133")
      (value "4.7k")
      (footprint "Buck:R0805")
      (description "RES Thick Film, 2kΩ, 1%, 0.25W, 100ppm/°C, 1206")
      (fields (field (name "TOLERANCE") "1%"))
      (libsource (lib "Miscellaneous Devices") (part "1029c3af85768c4190bb7ad29bc67b5"))
    )
    (comp (ref "R134") (value "0") (footprint "Buck:R0805") (libsource (lib "MYLIB") (part "ResSMD")))
    (comp (ref "R135") (value "0") (footprint "Buck:R0805") (libsource (lib "MYLIB") (part "ResSMD")))
    (comp (ref "R136")
      (value "Res1")
      (footprint "Buck:R0805")
      (description "Resistor")
      (fields (field (name "ALTIUM_VALUE") "15k") (field (name "PUBLISHER") "Altium Limited"))
      (libsource (lib "Miscellaneous Devices") (part "Res1"))
    )
    (comp (ref "R137") (value "1K") (footprint "Buck:R0805") (libsource (lib "MYLIB") (part "ResSMD")))
    (comp (ref "R138") (value "1K") (footprint "Buck:R0805") (libsource (lib "MYLIB") (part "ResSMD")))
    (comp (ref "R139") (value "1K") (footprint "Buck:R0805") (libsource (lib "MYLIB") (part "ResSMD")))
    (comp (ref "R140") (value "0 SMD") (footprint "Buck:R0805") (libsource (lib "MYLIB") (part "ResSMD")))
    (comp (ref "R141") (value "0 SMD") (footprint "Buck:R0805") (libsource (lib "MYLIB") (part "ResSMD")))
    (comp (ref "R142") (value "0 SMD") (footprint "Buck:R0805") (libsource (lib "MYLIB") (part "ResSMD")))
    (comp (ref "R143") (value "ResSMD") (footprint "Buck:R0805") (libsource (lib "MYLIB") (part "ResSMD")))
    (comp (ref "R144") (value "0 SMD") (footprint "Buck:R0805") (libsource (lib "MYLIB") (part "ResSMD")))
    (comp (ref "R145") (value "0 SMD") (footprint "Buck:R0805") (libsource (lib "MYLIB") (part "ResSMD")))
    (comp (ref "R146") (value "0 SMD") (footprint "Buck:R0805") (libsource (lib "MYLIB") (part "ResSMD")))
    (comp (ref "R147") (value "ResSMD") (footprint "Buck:R0805") (libsource (lib "MYLIB") (part "ResSMD")))
    (comp (ref "R148") (value "ResSMD") (footprint "Buck:R0805") (libsource (lib "MYLIB") (part "ResSMD")))
    (comp (ref "R149") (value "ResSMD") (footprint "Buck:R0805") (libsource (lib "MYLIB") (part "ResSMD")))
    (comp (ref "R150") (value "ResSMD") (footprint "Buck:R0805") (libsource (lib "MYLIB") (part "ResSMD")))
    (comp (ref "R151") (value "ResSMD") (footprint "Buck:R0805") (libsource (lib "MYLIB") (part "ResSMD")))
    (comp (ref "R152") (value "ResSMD") (footprint "Buck:R0805") (libsource (lib "MYLIB") (part "ResSMD")))
    (comp (ref "R153") (value "ResSMD") (footprint "Buck:R0805") (libsource (lib "MYLIB") (part "ResSMD")))
    (comp (ref "R154")
      (value "Res3")
      (footprint "Buck:R0603")
      (description "Resistor")
      (fields (field (name "ALTIUM_VALUE") "0") (field (name "PUBLISHER") "Altium Limited"))
      (libsource (lib "Miscellaneous Devices") (part "Res3"))
    )
    (comp (ref "R155") (value "ResSMD") (footprint "Buck:R0805") (libsource (lib "MYLIB") (part "ResSMD")))
    (comp (ref "R156") (value "ResSMD") (footprint "Buck:R0805") (libsource (lib "MYLIB") (part "ResSMD")))
    (comp (ref "R157") (value "ResSMD") (footprint "Buck:R0805") (libsource (lib "MYLIB") (part "ResSMD")))
    (comp (ref "R158") (value "ResSMD") (footprint "Buck:R0805") (libsource (lib "MYLIB") (part "ResSMD")))
    (comp (ref "R159") (value "ResSMD") (footprint "Buck:R0805") (libsource (lib "MYLIB") (part "ResSMD")))
    (comp (ref "R160") (value "0 SMD") (footprint "Buck:R0805") (libsource (lib "MYLIB") (part "ResSMD")))
    (comp (ref "R161") (value "ResSMD") (footprint "Buck:R0805") (libsource (lib "MYLIB") (part "ResSMD")))
    (comp (ref "R162")
      (value "Res3")
      (footprint "Buck:R0603")
      (description "Resistor")
      (fields (field (name "ALTIUM_VALUE") "0") (field (name "PUBLISHER") "Altium Limited"))
      (libsource (lib "Miscellaneous Devices") (part "Res3"))
    )
    (comp (ref "R163")
      (value "Res3")
      (footprint "Buck:R0603")
      (description "Resistor")
      (fields (field (name "ALTIUM_VALUE") "0") (field (name "PUBLISHER") "Altium Limited"))
      (libsource (lib "Miscellaneous Devices") (part "Res3"))
    )
    (comp (ref "R164") (value "ResSMD") (footprint "Buck:R0805") (libsource (lib "MYLIB") (part "ResSMD")))
    (comp (ref "R165") (value "ResSMD") (footprint "Buck:R0805") (libsource (lib "MYLIB") (part "ResSMD")))
    (comp (ref "R166") (value "ResSMD") (footprint "Buck:R0805") (libsource (lib "MYLIB") (part "ResSMD")))
    (comp (ref "R167") (value "0 SMD") (footprint "Buck:R0805") (libsource (lib "MYLIB") (part "ResSMD")))
    (comp (ref "R168") (value "0 SMD") (footprint "Buck:R0805") (libsource (lib "MYLIB") (part "ResSMD")))
    (comp (ref "R169") (value "ResSMD") (footprint "Buck:R0805") (libsource (lib "MYLIB") (part "ResSMD")))
    (comp (ref "R170") (value "ResSMD") (footprint "Buck:R0805") (libsource (lib "MYLIB") (part "ResSMD")))
    (comp (ref "R171") (value "0 SMD") (footprint "Buck:R0805") (libsource (lib "MYLIB") (part "ResSMD")))
    (comp (ref "R172") (value "0 SMD") (footprint "Buck:R0805") (libsource (lib "MYLIB") (part "ResSMD")))
    (comp (ref "R173") (value "ResSMD") (footprint "Buck:R0805") (libsource (lib "MYLIB") (part "ResSMD")))
    (comp (ref "R174") (value "ResSMD") (footprint "Buck:R0805") (libsource (lib "MYLIB") (part "ResSMD")))
    (comp (ref "R175") (value "ResSMD") (footprint "Buck:R0805") (libsource (lib "MYLIB") (part "ResSMD")))
    (comp (ref "T1")
      (value "Full Transformer")
      (footprint "Buck:Full_Transformer")
      (libsource (lib "Full bridge-V1.00") (part "Full_Transformer"))
    )
    (comp (ref "TP1")
      (value "Pad")
      (footprint "Buck:TP-0.5mm")
      (libsource (lib "") (part "Con1 pin-Small_1"))
    )
    (comp (ref "TP2")
      (value "Pad")
      (footprint "Buck:TP-0.5mm")
      (libsource (lib "MYLIB") (part "Con1 pin-Small"))
    )
    (comp (ref "TP3")
      (value "Pad")
      (footprint "Buck:TP-0.5mm")
      (libsource (lib "") (part "Con1 pin-Small_1"))
    )
    (comp (ref "TP4")
      (value "Pad")
      (footprint "Buck:TP-0.5mm")
      (libsource (lib "") (part "Con1 pin-Small_1"))
    )
    (comp (ref "TP5")
      (value "Pad")
      (footprint "Buck:TP-0.5mm")
      (libsource (lib "") (part "Con1 pin-Small_1"))
    )
    (comp (ref "TP6")
      (value "Pad")
      (footprint "Buck:TP-0.5mm")
      (libsource (lib "MYLIB") (part "Con1 pin-Small"))
    )
    (comp (ref "TP7")
      (value "Pad")
      (footprint "Buck:TP-0.5mm")
      (libsource (lib "") (part "Con1 pin-Small_2"))
    )
    (comp (ref "TP8")
      (value "Pad")
      (footprint "Buck:TP-0.5mm")
      (libsource (lib "") (part "Con1 pin-Small_3"))
    )
    (comp (ref "TP9")
      (value "Pad")
      (footprint "Buck:TP-0.5mm")
      (libsource (lib "") (part "Con1 pin-Small_1"))
    )
    (comp (ref "TP10")
      (value "Pad")
      (footprint "Buck:TP-0.5mm")
      (libsource (lib "") (part "Con1 pin-Small_1"))
    )
    (comp (ref "TP11")
      (value "Pad")
      (footprint "Buck:TP-0.5mm")
      (libsource (lib "") (part "Con1 pin-Small_1"))
    )
    (comp (ref "TP12")
      (value "Pad")
      (footprint "Buck:TP-0.5mm")
      (libsource (lib "MYLIB") (part "Con1 pin-Small"))
    )
    (comp (ref "TP13")
      (value "Pad")
      (footprint "Buck:TP-0.5mm")
      (libsource (lib "") (part "Con1 pin-Small_2"))
    )
    (comp (ref "TP14")
      (value "Pad")
      (footprint "Buck:TP-0.5mm")
      (libsource (lib "") (part "Con1 pin-Small_3"))
    )
    (comp (ref "TP15")
      (value "Pad")
      (footprint "Buck:TP-0.5mm")
      (libsource (lib "") (part "Con1 pin-Small_1"))
    )
    (comp (ref "TP16")
      (value "Pad")
      (footprint "Buck:TP-0.5mm")
      (libsource (lib "") (part "Con1 pin-Small_1"))
    )
    (comp (ref "TP17")
      (value "Pad")
      (footprint "Buck:TP-0.5mm")
      (libsource (lib "") (part "Con1 pin-Small_1"))
    )
    (comp (ref "TP18")
      (value "Pad")
      (footprint "Buck:TP-0.5mm")
      (libsource (lib "MYLIB") (part "Con1 pin-Small"))
    )
    (comp (ref "TP19")
      (value "Pad")
      (footprint "Buck:TP-0.5mm")
      (libsource (lib "") (part "Con1 pin-Small_2"))
    )
    (comp (ref "TP20")
      (value "Pad")
      (footprint "Buck:TP-0.5mm")
      (libsource (lib "") (part "Con1 pin-Small_3"))
    )
    (comp (ref "TP21")
      (value "Pad")
      (footprint "Buck:TP-0.5mm")
      (libsource (lib "") (part "Con1 pin-Small_1"))
    )
    (comp (ref "TP22")
      (value "Pad")
      (footprint "Buck:TP-0.5mm")
      (libsource (lib "") (part "Con1 pin-Small_1"))
    )
    (comp (ref "TP23")
      (value "Pad")
      (footprint "Buck:TP-0.5mm")
      (libsource (lib "") (part "Con1 pin-Small_1"))
    )
    (comp (ref "TP24")
      (value "Pad")
      (footprint "Buck:TP-0.5mm")
      (libsource (lib "MYLIB") (part "Con1 pin-Small"))
    )
    (comp (ref "TP25")
      (value "Pad")
      (footprint "Buck:TP-0.5mm")
      (libsource (lib "") (part "Con1 pin-Small_1"))
    )
    (comp (ref "TP26")
      (value "Pad")
      (footprint "Buck:TP-0.5mm")
      (libsource (lib "") (part "Con1 pin-Small_1"))
    )
    (comp (ref "TP27")
      (value "Pad")
      (footprint "Buck:TP-0.5mm")
      (libsource (lib "") (part "Con1 pin-Small_2"))
    )
    (comp (ref "TP28")
      (value "Pad")
      (footprint "Buck:TP-0.5mm")
      (libsource (lib "") (part "Con1 pin-Small_3"))
    )
    (comp (ref "TP29")
      (value "Pad")
      (footprint "Buck:TP-0.5mm")
      (libsource (lib "") (part "Con1 pin-Small_2"))
    )
    (comp (ref "TP30")
      (value "Pad")
      (footprint "Buck:TP-0.5mm")
      (libsource (lib "") (part "Con1 pin-Small_1"))
    )
    (comp (ref "TP31")
      (value "Pad")
      (footprint "Buck:TP-0.5mm")
      (libsource (lib "") (part "Con1 pin-Small_1"))
    )
    (comp (ref "TP32")
      (value "Pad")
      (footprint "Buck:TP-0.5mm")
      (libsource (lib "") (part "Con1 pin-Small_3"))
    )
    (comp (ref "TP33")
      (value "Pad")
      (footprint "Buck:TP-0.5mm")
      (libsource (lib "") (part "Con1 pin-Small_2"))
    )
    (comp (ref "TP34")
      (value "Pad")
      (footprint "Buck:TP-0.5mm")
      (libsource (lib "") (part "Con1 pin-Small_3"))
    )
    (comp (ref "TP35")
      (value "Pad")
      (footprint "Buck:TP-0.5mm")
      (libsource (lib "") (part "Con1 pin-Small_1"))
    )
    (comp (ref "TP36")
      (value "Pad")
      (footprint "Buck:TP-0.5mm")
      (libsource (lib "") (part "Con1 pin-Small_1"))
    )
    (comp (ref "TP37")
      (value "Pad")
      (footprint "Buck:TP-0.5mm")
      (libsource (lib "") (part "Con1 pin-Small_3"))
    )
    (comp (ref "TP38")
      (value "Pad")
      (footprint "Buck:TP-0.5mm")
      (libsource (lib "") (part "Con1 pin-Small_2"))
    )
    (comp (ref "TP39")
      (value "Pad")
      (footprint "Buck:TP-0.5mm")
      (libsource (lib "MYLIB") (part "Con1 pin-Small"))
    )
    (comp (ref "TP40")
      (value "Pad")
      (footprint "Buck:TP-0.5mm")
      (libsource (lib "") (part "Con1 pin-Small_1"))
    )
    (comp (ref "TP41")
      (value "Pad")
      (footprint "Buck:TP-0.5mm")
      (libsource (lib "") (part "Con1 pin-Small_1"))
    )
    (comp (ref "TP42")
      (value "Pad")
      (footprint "Buck:TP-0.5mm")
      (libsource (lib "") (part "Con1 pin-Small_3"))
    )
    (comp (ref "TP43")
      (value "Pad")
      (footprint "Buck:TP-0.5mm")
      (libsource (lib "") (part "Con1 pin-Small_1"))
    )
    (comp (ref "TP44")
      (value "Pad")
      (footprint "Buck:TP-0.5mm")
      (libsource (lib "") (part "Con1 pin-Small_1"))
    )
    (comp (ref "TP45")
      (value "Pad")
      (footprint "Buck:TP-0.5mm")
      (libsource (lib "") (part "Con1 pin-Small_2"))
    )
    (comp (ref "TP46")
      (value "Pad")
      (footprint "Buck:TP-0.5mm")
      (libsource (lib "") (part "Con1 pin-Small_3"))
    )
    (comp (ref "TP47")
      (value "Pad")
      (footprint "Buck:TP-0.5mm")
      (libsource (lib "") (part "Con1 pin-Small_1"))
    )
    (comp (ref "TP48")
      (value "Pad")
      (footprint "Buck:TP-0.5mm")
      (libsource (lib "") (part "Con1 pin-Small_3"))
    )
    (comp (ref "TP49")
      (value "Pad")
      (footprint "Buck:TP-0.5mm")
      (libsource (lib "") (part "Con1 pin-Small_1"))
    )
    (comp (ref "TP50")
      (value "Pad")
      (footprint "Buck:TP-0.5mm")
      (libsource (lib "") (part "Con1 pin-Small_1"))
    )
    (comp (ref "TP51")
      (value "Pad")
      (footprint "Buck:TP-0.5mm")
      (libsource (lib "") (part "Con1 pin-Small_1"))
    )
    (comp (ref "TP52")
      (value "Pad")
      (footprint "Buck:TP-0.5mm")
      (libsource (lib "") (part "Con1 pin-Small_1"))
    )
    (comp (ref "TP53")
      (value "Pad")
      (footprint "Buck:TP-0.5mm")
      (libsource (lib "MYLIB") (part "Con1 pin-Small"))
    )
    (comp (ref "TP54")
      (value "Pad")
      (footprint "Buck:TP-0.5mm")
      (libsource (lib "") (part "Con1 pin-Small_1"))
    )
    (comp (ref "TP55")
      (value "Pad")
      (footprint "Buck:TP-0.5mm")
      (libsource (lib "MYLIB") (part "Con1 pin-Small"))
    )
    (comp (ref "TP56")
      (value "Pad")
      (footprint "Buck:TP-0.5mm")
      (libsource (lib "MYLIB") (part "Con1 pin-Small"))
    )
    (comp (ref "TP57")
      (value "Pad")
      (footprint "Buck:TP-0.5mm")
      (libsource (lib "MYLIB") (part "Con1 pin-Small"))
    )
    (comp (ref "TP58")
      (value "Pad")
      (footprint "Buck:TP-0.5mm")
      (libsource (lib "") (part "Con1 pin-Small_1"))
    )
    (comp (ref "TP59")
      (value "Pad")
      (footprint "Buck:TP-0.5mm")
      (libsource (lib "") (part "Con1 pin-Small_1"))
    )
    (comp (ref "TP60")
      (value "Pad")
      (footprint "Buck:TP-0.5mm")
      (libsource (lib "") (part "Con1 pin-Small_1"))
    )
    (comp (ref "TP61")
      (value "Pad")
      (footprint "Buck:TP-0.5mm")
      (libsource (lib "MYLIB") (part "Con1 pin-Small"))
    )
    (comp (ref "TP62")
      (value "Pad")
      (footprint "Buck:TP-0.5mm")
      (libsource (lib "") (part "Con1 pin-Small_1"))
    )
    (comp (ref "TP63")
      (value "Pad")
      (footprint "Buck:TP-0.5mm")
      (libsource (lib "MYLIB") (part "Con1 pin-Small"))
    )
    (comp (ref "TP64")
      (value "Pad")
      (footprint "Buck:TP-0.5mm")
      (libsource (lib "") (part "Con1 pin-Small_3"))
    )
    (comp (ref "TP65")
      (value "Pad")
      (footprint "Buck:TP-0.5mm")
      (libsource (lib "MYLIB") (part "Con1 pin-Small"))
    )
    (comp (ref "TP66")
      (value "Pad")
      (footprint "Buck:TP-0.5mm")
      (libsource (lib "") (part "Con1 pin-Small_2"))
    )
    (comp (ref "TP67")
      (value "Pad")
      (footprint "Buck:TP-0.5mm")
      (libsource (lib "") (part "Con1 pin-Small_2"))
    )
    (comp (ref "TP68")
      (value "Pad")
      (footprint "Buck:TP-0.5mm")
      (libsource (lib "") (part "Con1 pin-Small_1"))
    )
    (comp (ref "TP69")
      (value "Pad")
      (footprint "Buck:TP-0.5mm")
      (libsource (lib "") (part "Con1 pin-Small_1"))
    )
    (comp (ref "TP70")
      (value "Pad")
      (footprint "Buck:TP-0.5mm")
      (libsource (lib "") (part "Con1 pin-Small_1"))
    )
    (comp (ref "TP71")
      (value "Pad")
      (footprint "Buck:TP-0.5mm")
      (libsource (lib "") (part "Con1 pin-Small_1"))
    )
    (comp (ref "TP72")
      (value "Pad")
      (footprint "Buck:TP-0.5mm")
      (libsource (lib "") (part "Con1 pin-Small_1"))
    )
    (comp (ref "TP73")
      (value "Pad")
      (footprint "Buck:TP-0.5mm")
      (libsource (lib "MYLIB") (part "Con1 pin-Small"))
    )
    (comp (ref "TP74")
      (value "Pad")
      (footprint "Buck:TP-0.5mm")
      (libsource (lib "") (part "Con1 pin-Small_1"))
    )
    (comp (ref "TP75")
      (value "Pad")
      (footprint "Buck:TP-0.5mm")
      (libsource (lib "") (part "Con1 pin-Small_1"))
    )
    (comp (ref "TP76")
      (value "Pad")
      (footprint "Buck:TP-0.5mm")
      (libsource (lib "") (part "Con1 pin-Small_3"))
    )
    (comp (ref "TP77")
      (value "Pad")
      (footprint "Buck:TP-0.5mm")
      (libsource (lib "MYLIB") (part "Con1 pin-Small"))
    )
    (comp (ref "TP78")
      (value "Pad")
      (footprint "Buck:TP-0.5mm")
      (libsource (lib "") (part "Con1 pin-Small_2"))
    )
    (comp (ref "TP79")
      (value "Pad")
      (footprint "Buck:TP-0.5mm")
      (libsource (lib "") (part "Con1 pin-Small_1"))
    )
    (comp (ref "TP80")
      (value "Pad")
      (footprint "Buck:TP-0.5mm")
      (libsource (lib "MYLIB") (part "Con1 pin-Small"))
    )
    (comp (ref "TP81")
      (value "Pad")
      (footprint "Buck:TP-0.5mm")
      (libsource (lib "") (part "Con1 pin-Small_1"))
    )
    (comp (ref "TP82")
      (value "Pad")
      (footprint "Buck:TP-0.5mm")
      (libsource (lib "") (part "Con1 pin-Small_1"))
    )
    (comp (ref "TP83")
      (value "Pad")
      (footprint "Buck:TP-0.5mm")
      (libsource (lib "") (part "Con1 pin-Small_2"))
    )
    (comp (ref "TP84")
      (value "Pad")
      (footprint "Buck:TP-0.5mm")
      (libsource (lib "") (part "Con1 pin-Small_2"))
    )
    (comp (ref "TP85")
      (value "Pad")
      (footprint "Buck:TP-0.5mm")
      (libsource (lib "") (part "Con1 pin-Small_1"))
    )
    (comp (ref "TP86")
      (value "Pad")
      (footprint "Buck:TP-0.5mm")
      (libsource (lib "") (part "Con1 pin-Small_1"))
    )
    (comp (ref "TP87")
      (value "Pad")
      (footprint "Buck:TP-0.5mm")
      (libsource (lib "") (part "Con1 pin-Small_3"))
    )
    (comp (ref "U1")
      (value "MJWI10-24S12-MIN")
      (footprint "Buck:MJWI10-24S12")
      (libsource (lib "MYLIB") (part "MINMAX-MJWI20"))
    )
    (comp (ref "U2")
      (value "SN74LVC1G17DBVT SOT23")
      (footprint "Buck:SOT95P280X145-5N")
      (description "IC BUF NON-INVERT 5.5V SC70-5")
      (libsource (lib "Miscellaneous Devices") (part "333895c48767551a2a38df23237d11a"))
    )
    (comp (ref "U3")
      (value "PC81713NIP1B")
      (footprint "Buck:SOP-4L")
      (libsource (lib "MYLIB") (part "PC817"))
    )
    (comp (ref "U4")
      (value "SN74LVC1G17DBVT SOT23")
      (footprint "Buck:SOT95P280X145-5N")
      (description "IC BUF NON-INVERT 5.5V SC70-5")
      (libsource (lib "Miscellaneous Devices") (part "333895c48767551a2a38df23237d11a"))
    )
    (comp (ref "U5")
      (value "SI8261BBD-C-ISR")
      (footprint "Buck:SLAB-SDIP6_N")
      (fields (field (name "PARTNUMBER") "Si8261BBD-C-IS") (field (name "MANUFACTURER") "Silicon Labs"))
      (libsource (lib "Miscellaneous Devices") (part "SLAB-Si8261X-SDIP-6"))
    )
    (comp (ref "U6")
      (value "IXDN609SIATR")
      (footprint "Buck:IXDN609SIATR")
      (fields (field (name "PARTNUMBER") "IXDN609SI"))
      (libsource (lib "Miscellaneous Devices") (part "IXYS-IXDN609-8"))
    )
    (comp (ref "U7")
      (value "SN74LVC1G17DBVT SOT23")
      (footprint "Buck:SOT95P280X145-5N")
      (description "IC BUF NON-INVERT 5.5V SC70-5")
      (libsource (lib "Miscellaneous Devices") (part "333895c48767551a2a38df23237d11a"))
    )
    (comp (ref "U8")
      (value "SI8261BBD-C-ISR")
      (footprint "Buck:SLAB-SDIP6_N")
      (fields (field (name "PARTNUMBER") "Si8261BBD-C-IS") (field (name "MANUFACTURER") "Silicon Labs"))
      (libsource (lib "Miscellaneous Devices") (part "SLAB-Si8261X-SDIP-6"))
    )
    (comp (ref "U9")
      (value "IXDN609SIATR")
      (footprint "Buck:IXDN609SIATR")
      (fields (field (name "PARTNUMBER") "IXDN609SI"))
      (libsource (lib "Miscellaneous Devices") (part "IXYS-IXDN609-8"))
    )
    (comp (ref "U10")
      (value "SN74LVC1G17DBVT SOT23")
      (footprint "Buck:SOT95P280X145-5N")
      (description "IC BUF NON-INVERT 5.5V SC70-5")
      (libsource (lib "Miscellaneous Devices") (part "333895c48767551a2a38df23237d11a"))
    )
    (comp (ref "U11")
      (value "SI8261BBD-C-ISR")
      (footprint "Buck:SLAB-SDIP6_N")
      (fields (field (name "PARTNUMBER") "Si8261BBD-C-IS") (field (name "MANUFACTURER") "Silicon Labs"))
      (libsource (lib "Miscellaneous Devices") (part "SLAB-Si8261X-SDIP-6"))
    )
    (comp (ref "U12")
      (value "IXDN609SIATR")
      (footprint "Buck:IXDN609SIATR")
      (fields (field (name "PARTNUMBER") "IXDN609SI"))
      (libsource (lib "Miscellaneous Devices") (part "IXYS-IXDN609-8"))
    )
    (comp (ref "U13")
      (value "SN74LVC1G17DBVT SOT23")
      (footprint "Buck:SOT95P280X145-5N")
      (description "IC BUF NON-INVERT 5.5V SC70-5")
      (libsource (lib "Miscellaneous Devices") (part "333895c48767551a2a38df23237d11a"))
    )
    (comp (ref "U14")
      (value "SI8261BBD-C-ISR")
      (footprint "Buck:SLAB-SDIP6_N")
      (fields (field (name "PARTNUMBER") "Si8261BBD-C-IS") (field (name "MANUFACTURER") "Silicon Labs"))
      (libsource (lib "Miscellaneous Devices") (part "SLAB-Si8261X-SDIP-6"))
    )
    (comp (ref "U15")
      (value "IXDN609SIATR")
      (footprint "Buck:IXDN609SIATR")
      (fields (field (name "PARTNUMBER") "IXDN609SI"))
      (libsource (lib "Miscellaneous Devices") (part "IXYS-IXDN609-8"))
    )
    (comp (ref "U16")
      (value "LT1764AEQ-3.3")
      (footprint "Buck:LT1764AEQ33TRPBF")
      (fields (field (name "MANUFACTURER") "Linear Technology"))
      (libsource (lib "Linear Technology Power Management LDO Linear Regulators") (part "LT1764AEQ-3.3"))
    )
    (comp (ref "U17")
      (value "CAS 15-NP")
      (footprint "Buck:CAS 15-NP")
      (description "Current Transducer, 5 V, -40 to 85 degC, 10-Pin THD, RoHS, Tray")
      (fields (field (name "MANUFACTURER") "LEM") (field (name "PARTNUMBER") "LTSR 15-NP"))
      (libsource (lib "Miscellaneous Devices") (part "CAS 15-NP"))
    )
    (comp (ref "U19")
      (value "TLV2781IDBVR")
      (footprint "Buck:DBV0005A_L")
      (fields (field (name "PARTNUMBER") "OPA320AIDBVR") (field (name "MANUFACTURER") "Texas Instruments"))
      (libsource (lib "Miscellaneous Devices") (part "TI-OPA_SM7XXXX-DBV5"))
    )
    (comp (ref "U20")
      (value "NCV8114ASN165T1G")
      (footprint "Buck:TSOP-5")
      (libsource (lib "Miscellaneous Devices") (part "ONSC-MC78PC-SOT-23-5"))
    )
    (comp (ref "U21")
      (value "OPA27GP")
      (footprint "Buck:P0008A")
      (fields (field (name "MANUFACTURER") "Texas Instruments"))
      (libsource (lib "Miscellaneous Devices") (part "TI-OPA27-X8"))
    )
  )
  (nets
    (net (code "1") (name "+3.3VD") (class "Default")
      (node (ref "C73") (pin "2") (pinfunction "2_2") (pintype "passive"))
      (node (ref "R11") (pin "2") (pinfunction "2_2") (pintype "passive"))
      (node (ref "R140") (pin "1") (pinfunction "1_1") (pintype "passive"))
      (node (ref "R150") (pin "2") (pinfunction "2_2") (pintype "passive"))
      (node (ref "R171") (pin "1") (pinfunction "1_1") (pintype "passive"))
      (node (ref "R2") (pin "2") (pinfunction "2_2") (pintype "passive"))
      (node (ref "R44") (pin "2") (pinfunction "2_2") (pintype "passive"))
      (node (ref "R70") (pin "2") (pinfunction "2_2") (pintype "passive"))
      (node (ref "R95") (pin "2") (pinfunction "2_2") (pintype "passive"))
      (node (ref "U19") (pin "5") (pinfunction "V+_5") (pintype "power_in"))
    )
    (net (code "2") (name "+3.3VD2") (class "Default")
      (node (ref "C60") (pin "1") (pinfunction "1_1") (pintype "passive"))
      (node (ref "C64") (pin "2") (pinfunction "2_2") (pintype "passive"))
      (node (ref "DS10") (pin "1") (pinfunction "A_1") (pintype "passive"))
      (node (ref "R14") (pin "1") (pinfunction "1_1") (pintype "passive"))
      (node (ref "TP26") (pin "1") (pinfunction "1_1") (pintype "passive"))
      (node (ref "U16") (pin "4") (pinfunction "OUT_4") (pintype "power_in"))
      (node (ref "U16") (pin "5") (pinfunction "SENSE_5") (pintype "input"))
    )
    (net (code "3") (name "+5V_MICRO") (class "Default")
      (node (ref "C69") (pin "2") (pinfunction "2_2") (pintype "passive"))
      (node (ref "C71") (pin "2") (pinfunction "2_2") (pintype "passive"))
      (node (ref "C72") (pin "2") (pinfunction "2_2") (pintype "passive"))
      (node (ref "C78") (pin "2") (pinfunction "2_2") (pintype "passive"))
      (node (ref "DS12") (pin "1") (pinfunction "A_1") (pintype "passive"))
      (node (ref "FB11") (pin "1") (pinfunction "1_1") (pintype "power_in"))
      (node (ref "J2") (pin "13") (pinfunction "13_13") (pintype "passive"))
      (node (ref "J2") (pin "25") (pinfunction "25_25") (pintype "passive"))
      (node (ref "R12") (pin "1") (pinfunction "1_1") (pintype "passive"))
      (node (ref "R138") (pin "1") (pinfunction "1_1") (pintype "passive"))
      (node (ref "R144") (pin "1") (pinfunction "1_1") (pintype "passive"))
      (node (ref "R149") (pin "2") (pinfunction "2_2") (pintype "passive"))
      (node (ref "R15") (pin "1") (pinfunction "1_1") (pintype "passive"))
      (node (ref "R172") (pin "2") (pinfunction "2_2") (pintype "passive"))
      (node (ref "R3") (pin "1") (pinfunction "1_1") (pintype "passive"))
      (node (ref "R45") (pin "1") (pinfunction "1_1") (pintype "passive"))
      (node (ref "R71") (pin "1") (pinfunction "1_1") (pintype "passive"))
      (node (ref "R96") (pin "1") (pinfunction "1_1") (pintype "passive"))
      (node (ref "TP25") (pin "1") (pinfunction "1_1") (pintype "passive"))
      (node (ref "TP63") (pin "1") (pinfunction "1_1") (pintype "passive"))
      (node (ref "U17") (pin "13") (pinfunction "+5V_13") (pintype "passive"))
      (node (ref "U20") (pin "1") (pinfunction "VIN_1") (pintype "power_in"))
    )
    (net (code "4") (name "+12V_Digital IN") (class "Default")
      (node (ref "C2") (pin "1") (pinfunction "1_1") (pintype "passive"))
      (node (ref "C49") (pin "1") (pinfunction "1_1") (pintype "passive"))
      (node (ref "C52") (pin "1") (pinfunction "1_1") (pintype "passive"))
      (node (ref "C56") (pin "1") (pinfunction "1_1") (pintype "passive"))
      (node (ref "C68") (pin "1") (pinfunction "1_1") (pintype "passive"))
      (node (ref "J1") (pin "1") (pinfunction "1_1") (pintype "passive"))
      (node (ref "PS1") (pin "22") (pinfunction "+VIN_22") (pintype "input"))
      (node (ref "PS1") (pin "23") (pinfunction "+VIN_23") (pintype "input"))
      (node (ref "PS2") (pin "22") (pinfunction "+VIN_22") (pintype "input"))
      (node (ref "PS2") (pin "23") (pinfunction "+VIN_23") (pintype "input"))
      (node (ref "PS3") (pin "22") (pinfunction "+VIN_22") (pintype "input"))
      (node (ref "PS3") (pin "23") (pinfunction "+VIN_23") (pintype "input"))
      (node (ref "PS4") (pin "22") (pinfunction "+VIN_22") (pintype "input"))
      (node (ref "PS4") (pin "23") (pinfunction "+VIN_23") (pintype "input"))
      (node (ref "TP55") (pin "1") (pinfunction "1_1") (pintype "passive"))
      (node (ref "U1") (pin "1") (pinfunction "+In_1") (pintype "passive"))
    )
    (net (code "5") (name "1.65V") (class "Default")
      (node (ref "C79") (pin "2") (pinfunction "2_2") (pintype "passive"))
      (node (ref "R135") (pin "2") (pinfunction "2_2") (pintype "passive"))
      (node (ref "R146") (pin "1") (pinfunction "1_1") (pintype "passive"))
      (node (ref "TP86") (pin "1") (pinfunction "1_1") (pintype "passive"))
      (node (ref "U20") (pin "5") (pinfunction "VOUT_5") (pintype "power_in"))
    )
    (net (code "6") (name "3") (class "Default")
      (node (ref "J2") (pin "12") (pinfunction "12_12") (pintype "passive"))
      (node (ref "TP66") (pin "1") (pinfunction "1_1") (pintype "passive"))
    )
    (net (code "7") (name "4") (class "Default")
      (node (ref "J2") (pin "24") (pinfunction "24_24") (pintype "passive"))
      (node (ref "TP67") (pin "1") (pinfunction "1_1") (pintype "passive"))
    )
    (net (code "8") (name "AC Output") (class "Default")
      (node (ref "F2") (pin "2") (pinfunction "2_2") (pintype "passive"))
      (node (ref "P2") (pin "1") (pinfunction "1_1") (pintype "passive"))
      (node (ref "P2") (pin "2") (pinfunction "2_2") (pintype "passive"))
      (node (ref "R141") (pin "1") (pinfunction "1_1") (pintype "passive"))
      (node (ref "TP69") (pin "1") (pinfunction "1_1") (pintype "passive"))
    )
    (net (code "9") (name "E FB TEMP") (class "Default")
      (node (ref "J2") (pin "8") (pinfunction "8_8") (pintype "passive"))
    )
    (net (code "10") (name "FB TEMP of the heatsink") (class "Default")
      (node (ref "FB2") (pin "2") (pinfunction "2_2") (pintype "power_in"))
      (node (ref "J2") (pin "16") (pinfunction "16_16") (pintype "passive"))
    )
    (net (code "11") (name "Fan") (class "Default")
      (node (ref "C3") (pin "1") (pinfunction "1_1") (pintype "passive"))
      (node (ref "C4") (pin "2") (pinfunction "2_2") (pintype "passive"))
      (node (ref "D1") (pin "1") (pinfunction "A_1") (pintype "passive"))
      (node (ref "DS1") (pin "1") (pinfunction "A_1") (pintype "passive"))
      (node (ref "P1") (pin "1") (pinfunction "1_1") (pintype "passive"))
      (node (ref "U1") (pin "3") (pinfunction "+Out_3") (pintype "passive"))
    )
    (net (code "12") (name "Fan FB command") (class "Default")
      (node (ref "FB1") (pin "1") (pinfunction "1_1") (pintype "power_in"))
      (node (ref "J2") (pin "23") (pinfunction "23_23") (pintype "passive"))
    )
    (net (code "13") (name "GND side FB") (class "Default")
      (node (ref "C21") (pin "1") (pinfunction "1_1") (pintype "passive"))
      (node (ref "C24") (pin "1") (pinfunction "1_1") (pintype "passive"))
      (node (ref "C26") (pin "2") (pinfunction "2_2") (pintype "passive"))
      (node (ref "C27") (pin "2") (pinfunction "2_2") (pintype "passive"))
      (node (ref "C28") (pin "2") (pinfunction "2_2") (pintype "passive"))
      (node (ref "C29") (pin "2") (pinfunction "2_2") (pintype "passive"))
      (node (ref "C30") (pin "2") (pinfunction "2_2") (pintype "passive"))
      (node (ref "C31") (pin "2") (pinfunction "2_2") (pintype "passive"))
      (node (ref "C32") (pin "1") (pinfunction "1_1") (pintype "passive"))
      (node (ref "C35") (pin "1") (pinfunction "1_1") (pintype "passive"))
      (node (ref "C37") (pin "2") (pinfunction "2_2") (pintype "passive"))
      (node (ref "C38") (pin "2") (pinfunction "2_2") (pintype "passive"))
      (node (ref "C39") (pin "1") (pinfunction "1_1") (pintype "passive"))
      (node (ref "C40") (pin "1") (pinfunction "1_1") (pintype "passive"))
      (node (ref "C45") (pin "2") (pinfunction "2_2") (pintype "passive"))
      (node (ref "C46") (pin "2") (pinfunction "2_2") (pintype "passive"))
      (node (ref "CR11") (pin "1") (pinfunction "A_1") (pintype "passive"))
      (node (ref "CR17") (pin "1") (pinfunction "A_1") (pintype "passive"))
      (node (ref "CR7") (pin "1") (pinfunction "A_1") (pintype "passive"))
      (node (ref "D13") (pin "1") (pinfunction "A_1") (pintype "passive"))
      (node (ref "D14") (pin "1") (pinfunction "A_1") (pintype "passive"))
      (node (ref "D15") (pin "1") (pinfunction "A_1") (pintype "passive"))
      (node (ref "D16") (pin "1") (pinfunction "A_1") (pintype "passive"))
      (node (ref "D17") (pin "1") (pinfunction "A_1") (pintype "passive"))
      (node (ref "D18") (pin "1") (pinfunction "A_1") (pintype "passive"))
      (node (ref "P3") (pin "3") (pinfunction "3_3") (pintype "passive"))
      (node (ref "P3") (pin "4") (pinfunction "4_4") (pintype "passive"))
      (node (ref "Q2") (pin "3") (pinfunction "E_3") (pintype "passive"))
      (node (ref "Q3") (pin "3") (pinfunction "E_3") (pintype "passive"))
      (node (ref "R125") (pin "1") (pinfunction "1_1") (pintype "passive"))
      (node (ref "R167") (pin "2") (pinfunction "2_2") (pintype "passive"))
      (node (ref "R168") (pin "2") (pinfunction "2_2") (pintype "passive"))
      (node (ref "R40") (pin "1") (pinfunction "1_1") (pintype "passive"))
      (node (ref "R42") (pin "2") (pinfunction "2_2") (pintype "passive"))
      (node (ref "R43") (pin "2") (pinfunction "2_2") (pintype "passive"))
      (node (ref "R51") (pin "1") (pinfunction "1_1") (pintype "passive"))
      (node (ref "R57") (pin "1") (pinfunction "1_1") (pintype "passive"))
      (node (ref "R58") (pin "1") (pinfunction "1_1") (pintype "passive"))
      (node (ref "R64") (pin "1") (pinfunction "1_1") (pintype "passive"))
      (node (ref "R65") (pin "2") (pinfunction "2_2") (pintype "passive"))
      (node (ref "R66") (pin "2") (pinfunction "2_2") (pintype "passive"))
      (node (ref "R68") (pin "1") (pinfunction "1_1") (pintype "passive"))
      (node (ref "R77") (pin "1") (pinfunction "1_1") (pintype "passive"))
      (node (ref "R86") (pin "1") (pinfunction "1_1") (pintype "passive"))
      (node (ref "TP33") (pin "1") (pinfunction "1_1") (pintype "passive"))
      (node (ref "TP83") (pin "1") (pinfunction "1_1") (pintype "passive"))
      (node (ref "TP84") (pin "1") (pinfunction "1_1") (pintype "passive"))
      (node (ref "TP85") (pin "1") (pinfunction "1_1") (pintype "passive"))
      (node (ref "U12") (pin "4") (pinfunction "GND_4") (pintype "power_in"))
      (node (ref "U12") (pin "5") (pinfunction "GND_5") (pintype "power_in"))
      (node (ref "U9") (pin "4") (pinfunction "GND_4") (pintype "power_in"))
      (node (ref "U9") (pin "5") (pinfunction "GND_5") (pintype "power_in"))
    )
    (net (code "14") (name "GND_DIGITAL") (class "Default")
      (node (ref "C1") (pin "2") (pinfunction "2_2") (pintype "passive"))
      (node (ref "C20") (pin "2") (pinfunction "2_2") (pintype "passive"))
      (node (ref "C41") (pin "2") (pinfunction "2_2") (pintype "passive"))
      (node (ref "C5") (pin "2") (pinfunction "2_2") (pintype "passive"))
      (node (ref "C53") (pin "2") (pinfunction "2_2") (pintype "passive"))
      (node (ref "C60") (pin "2") (pinfunction "2_2") (pintype "passive"))
      (node (ref "C62") (pin "1") (pinfunction "1_1") (pintype "passive"))
      (node (ref "C63") (pin "1") (pinfunction "1_1") (pintype "passive"))
      (node (ref "C64") (pin "1") (pinfunction "1_1") (pintype "passive"))
      (node (ref "C69") (pin "1") (pinfunction "1_1") (pintype "passive"))
      (node (ref "C71") (pin "1") (pinfunction "1_1") (pintype "passive"))
      (node (ref "C72") (pin "1") (pinfunction "1_1") (pintype "passive"))
      (node (ref "C73") (pin "1") (pinfunction "1_1") (pintype "passive"))
      (node (ref "C75") (pin "1") (pinfunction "1_1") (pintype "passive"))
      (node (ref "C77") (pin "1") (pinfunction "1_1") (pintype "passive"))
      (node (ref "C78") (pin "1") (pinfunction "1_1") (pintype "passive"))
      (node (ref "C79") (pin "1") (pinfunction "1_1") (pintype "passive"))
      (node (ref "C80") (pin "2") (pinfunction "2_2") (pintype "passive"))
      (node (ref "C82") (pin "2") (pinfunction "2_2") (pintype "passive"))
      (node (ref "C83") (pin "2") (pinfunction "2_2") (pintype "passive"))
      (node (ref "C86") (pin "2") (pinfunction "2_2") (pintype "passive"))
      (node (ref "J2") (pin "1") (pinfunction "1_1") (pintype "passive"))
      (node (ref "J2") (pin "14") (pinfunction "14_14") (pintype "passive"))
      (node (ref "Q5") (pin "5") (pinfunction "GND2_5") (pintype "power_in"))
      (node (ref "R10") (pin "2") (pinfunction "2_2") (pintype "passive"))
      (node (ref "R100") (pin "2") (pinfunction "2_2") (pintype "passive"))
      (node (ref "R101") (pin "2") (pinfunction "2_2") (pintype "passive"))
      (node (ref "R102") (pin "2") (pinfunction "2_2") (pintype "passive"))
      (node (ref "R103") (pin "2") (pinfunction "2_2") (pintype "passive"))
      (node (ref "R104") (pin "2") (pinfunction "2_2") (pintype "passive"))
      (node (ref "R105") (pin "2") (pinfunction "2_2") (pintype "passive"))
      (node (ref "R111") (pin "1") (pinfunction "1_1") (pintype "passive"))
      (node (ref "R113") (pin "2") (pinfunction "2_2") (pintype "passive"))
      (node (ref "R114") (pin "1") (pinfunction "1_1") (pintype "passive"))
      (node (ref "R115") (pin "2") (pinfunction "2_2") (pintype "passive"))
      (node (ref "R116") (pin "2") (pinfunction "2_2") (pintype "passive"))
      (node (ref "R117") (pin "2") (pinfunction "2_2") (pintype "passive"))
      (node (ref "R118") (pin "1") (pinfunction "1_1") (pintype "passive"))
      (node (ref "R121") (pin "2") (pinfunction "2_2") (pintype "passive"))
      (node (ref "R122") (pin "2") (pinfunction "2_2") (pintype "passive"))
      (node (ref "R124") (pin "1") (pinfunction "1_1") (pintype "passive"))
      (node (ref "R129") (pin "1") (pinfunction "1_1") (pintype "passive"))
      (node (ref "R134") (pin "2") (pinfunction "2_2") (pintype "passive"))
      (node (ref "R136") (pin "1") (pinfunction "1_1") (pintype "passive"))
      (node (ref "R137") (pin "2") (pinfunction "2_2") (pintype "passive"))
      (node (ref "R139") (pin "2") (pinfunction "2_2") (pintype "passive"))
      (node (ref "R143") (pin "2") (pinfunction "2_2") (pintype "passive"))
      (node (ref "R145") (pin "1") (pinfunction "1_1") (pintype "passive"))
      (node (ref "R160") (pin "2") (pinfunction "2_2") (pintype "passive"))
      (node (ref "R164") (pin "2") (pinfunction "2_2") (pintype "passive"))
      (node (ref "R175") (pin "2") (pinfunction "2_2") (pintype "passive"))
      (node (ref "R21") (pin "1") (pinfunction "1_1") (pintype "passive"))
      (node (ref "R23") (pin "2") (pinfunction "2_2") (pintype "passive"))
      (node (ref "R24") (pin "2") (pinfunction "2_2") (pintype "passive"))
      (node (ref "R25") (pin "1") (pinfunction "1_1") (pintype "passive"))
      (node (ref "R26") (pin "2") (pinfunction "2_2") (pintype "passive"))
      (node (ref "R27") (pin "2") (pinfunction "2_2") (pintype "passive"))
      (node (ref "R28") (pin "2") (pinfunction "2_2") (pintype "passive"))
      (node (ref "R29") (pin "1") (pinfunction "1_1") (pintype "passive"))
      (node (ref "R53") (pin "1") (pinfunction "1_1") (pintype "passive"))
      (node (ref "R56") (pin "2") (pinfunction "2_2") (pintype "passive"))
      (node (ref "R59") (pin "1") (pinfunction "1_1") (pintype "passive"))
      (node (ref "R6") (pin "1") (pinfunction "1_1") (pintype "passive"))
      (node (ref "R60") (pin "2") (pinfunction "2_2") (pintype "passive"))
      (node (ref "R61") (pin "2") (pinfunction "2_2") (pintype "passive"))
      (node (ref "R62") (pin "2") (pinfunction "2_2") (pintype "passive"))
      (node (ref "R63") (pin "1") (pinfunction "1_1") (pintype "passive"))
      (node (ref "R78") (pin "1") (pinfunction "1_1") (pintype "passive"))
      (node (ref "R80") (pin "2") (pinfunction "2_2") (pintype "passive"))
      (node (ref "R81") (pin "1") (pinfunction "1_1") (pintype "passive"))
      (node (ref "R82") (pin "2") (pinfunction "2_2") (pintype "passive"))
      (node (ref "R83") (pin "2") (pinfunction "2_2") (pintype "passive"))
      (node (ref "R84") (pin "2") (pinfunction "2_2") (pintype "passive"))
      (node (ref "R85") (pin "1") (pinfunction "1_1") (pintype "passive"))
      (node (ref "R98") (pin "2") (pinfunction "2_2") (pintype "passive"))
      (node (ref "R99") (pin "2") (pinfunction "2_2") (pintype "passive"))
      (node (ref "TP14") (pin "1") (pinfunction "1_1") (pintype "passive"))
      (node (ref "TP20") (pin "1") (pinfunction "1_1") (pintype "passive"))
      (node (ref "TP28") (pin "1") (pinfunction "1_1") (pintype "passive"))
      (node (ref "TP29") (pin "1") (pinfunction "1_1") (pintype "passive"))
      (node (ref "TP32") (pin "1") (pinfunction "1_1") (pintype "passive"))
      (node (ref "TP38") (pin "1") (pinfunction "1_1") (pintype "passive"))
      (node (ref "TP39") (pin "1") (pinfunction "1_1") (pintype "passive"))
      (node (ref "TP48") (pin "1") (pinfunction "1_1") (pintype "passive"))
      (node (ref "TP64") (pin "1") (pinfunction "1_1") (pintype "passive"))
      (node (ref "TP8") (pin "1") (pinfunction "1_1") (pintype "passive"))
      (node (ref "TP87") (pin "1") (pinfunction "1_1") (pintype "passive"))
      (node (ref "U10") (pin "3") (pinfunction "GND_3") (pintype "power_in"))
      (node (ref "U11") (pin "3") (pinfunction "CATHODE_3") (pintype "passive"))
      (node (ref "U13") (pin "3") (pinfunction "GND_3") (pintype "power_in"))
      (node (ref "U14") (pin "3") (pinfunction "CATHODE_3") (pintype "passive"))
      (node (ref "U16") (pin "3") (pinfunction "GND_3") (pintype "power_in"))
      (node (ref "U16") (pin "6") (pinfunction "TAB_6") (pintype "power_in"))
      (node (ref "U17") (pin "12") (pinfunction "0V_12") (pintype "passive"))
      (node (ref "U2") (pin "3") (pinfunction "GND_3") (pintype "power_in"))
      (node (ref "U20") (pin "2") (pinfunction "GND_2") (pintype "power_in"))
      (node (ref "U3") (pin "2") (pinfunction "K_2") (pintype "passive"))
      (node (ref "U4") (pin "3") (pinfunction "GND_3") (pintype "power_in"))
      (node (ref "U5") (pin "3") (pinfunction "CATHODE_3") (pintype "passive"))
      (node (ref "U7") (pin "3") (pinfunction "GND_3") (pintype "power_in"))
      (node (ref "U8") (pin "3") (pinfunction "CATHODE_3") (pintype "passive"))
    )
    (net (code "15") (name "GND_Fan") (class "Default")
      (node (ref "C3") (pin "2") (pinfunction "2_2") (pintype "passive"))
      (node (ref "C4") (pin "1") (pinfunction "1_1") (pintype "passive"))
      (node (ref "D2") (pin "1") (pinfunction "A_1") (pintype "passive"))
      (node (ref "P1") (pin "2") (pinfunction "2_2") (pintype "passive"))
      (node (ref "R1") (pin "2") (pinfunction "2_2") (pintype "passive"))
      (node (ref "TP2") (pin "1") (pinfunction "1_1") (pintype "passive"))
      (node (ref "U1") (pin "5") (pinfunction "-Out_5") (pintype "passive"))
    )
    (net (code "16") (name "GND_GS1") (class "Default")
      (node (ref "C19") (pin "2") (pinfunction "2_2") (pintype "passive"))
      (node (ref "C47") (pin "2") (pinfunction "2_2") (pintype "passive"))
      (node (ref "C48") (pin "1") (pinfunction "1_1") (pintype "passive"))
      (node (ref "C6") (pin "2") (pinfunction "2_2") (pintype "passive"))
      (node (ref "C7") (pin "2") (pinfunction "2_2") (pintype "passive"))
      (node (ref "C8") (pin "1") (pinfunction "1_1") (pintype "passive"))
      (node (ref "CR2") (pin "1") (pinfunction "A_1") (pintype "passive"))
      (node (ref "PS1") (pin "16") (pinfunction "-VOUT_16") (pintype "output"))
      (node (ref "R20") (pin "2") (pinfunction "2_2") (pintype "passive"))
      (node (ref "R35") (pin "1") (pinfunction "1_1") (pintype "passive"))
      (node (ref "R8") (pin "2") (pinfunction "2_2") (pintype "passive"))
      (node (ref "R87") (pin "2") (pinfunction "2_2") (pintype "passive"))
      (node (ref "TP53") (pin "1") (pinfunction "1_1") (pintype "passive"))
      (node (ref "TP6") (pin "1") (pinfunction "1_1") (pintype "passive"))
      (node (ref "U5") (pin "4") (pinfunction "GND_4") (pintype "power_in"))
    )
    (net (code "17") (name "GND_GS2") (class "Default")
      (node (ref "C33") (pin "2") (pinfunction "2_2") (pintype "passive"))
      (node (ref "C34") (pin "2") (pinfunction "2_2") (pintype "passive"))
      (node (ref "C36") (pin "1") (pinfunction "1_1") (pintype "passive"))
      (node (ref "C39") (pin "2") (pinfunction "2_2") (pintype "passive"))
      (node (ref "C50") (pin "2") (pinfunction "2_2") (pintype "passive"))
      (node (ref "C51") (pin "1") (pinfunction "1_1") (pintype "passive"))
      (node (ref "CR6") (pin "1") (pinfunction "A_1") (pintype "passive"))
      (node (ref "PS2") (pin "16") (pinfunction "-VOUT_16") (pintype "output"))
      (node (ref "R40") (pin "2") (pinfunction "2_2") (pintype "passive"))
      (node (ref "R51") (pin "2") (pinfunction "2_2") (pintype "passive"))
      (node (ref "R65") (pin "1") (pinfunction "1_1") (pintype "passive"))
      (node (ref "R88") (pin "2") (pinfunction "2_2") (pintype "passive"))
      (node (ref "TP12") (pin "1") (pinfunction "1_1") (pintype "passive"))
      (node (ref "TP56") (pin "1") (pinfunction "1_1") (pintype "passive"))
      (node (ref "U8") (pin "4") (pinfunction "GND_4") (pintype "power_in"))
    )
    (net (code "18") (name "GND_GS3") (class "Default")
      (node (ref "C40") (pin "2") (pinfunction "2_2") (pintype "passive"))
      (node (ref "C42") (pin "2") (pinfunction "2_2") (pintype "passive"))
      (node (ref "C43") (pin "2") (pinfunction "2_2") (pintype "passive"))
      (node (ref "C44") (pin "1") (pinfunction "1_1") (pintype "passive"))
      (node (ref "C54") (pin "1") (pinfunction "1_1") (pintype "passive"))
      (node (ref "C55") (pin "2") (pinfunction "2_2") (pintype "passive"))
      (node (ref "CR10") (pin "1") (pinfunction "A_1") (pintype "passive"))
      (node (ref "PS3") (pin "16") (pinfunction "-VOUT_16") (pintype "output"))
      (node (ref "R66") (pin "1") (pinfunction "1_1") (pintype "passive"))
      (node (ref "R68") (pin "2") (pinfunction "2_2") (pintype "passive"))
      (node (ref "R77") (pin "2") (pinfunction "2_2") (pintype "passive"))
      (node (ref "R94") (pin "2") (pinfunction "2_2") (pintype "passive"))
      (node (ref "TP18") (pin "1") (pinfunction "1_1") (pintype "passive"))
      (node (ref "TP61") (pin "1") (pinfunction "1_1") (pintype "passive"))
      (node (ref "U11") (pin "4") (pinfunction "GND_4") (pintype "power_in"))
    )
    (net (code "19") (name "GND_GS4") (class "Default")
      (node (ref "C23") (pin "2") (pinfunction "2_2") (pintype "passive"))
      (node (ref "C57") (pin "2") (pinfunction "2_2") (pintype "passive"))
      (node (ref "C58") (pin "2") (pinfunction "2_2") (pintype "passive"))
      (node (ref "C59") (pin "1") (pinfunction "1_1") (pintype "passive"))
      (node (ref "C61") (pin "2") (pinfunction "2_2") (pintype "passive"))
      (node (ref "C67") (pin "1") (pinfunction "1_1") (pintype "passive"))
      (node (ref "CR14") (pin "1") (pinfunction "A_1") (pintype "passive"))
      (node (ref "PS4") (pin "16") (pinfunction "-VOUT_16") (pintype "output"))
      (node (ref "R110") (pin "2") (pinfunction "2_2") (pintype "passive"))
      (node (ref "R119") (pin "2") (pinfunction "2_2") (pintype "passive"))
      (node (ref "R36") (pin "1") (pinfunction "1_1") (pintype "passive"))
      (node (ref "R90") (pin "2") (pinfunction "2_2") (pintype "passive"))
      (node (ref "TP24") (pin "1") (pinfunction "1_1") (pintype "passive"))
      (node (ref "TP65") (pin "1") (pinfunction "1_1") (pintype "passive"))
      (node (ref "U14") (pin "4") (pinfunction "GND_4") (pintype "power_in"))
    )
    (net (code "20") (name "GND_High voltage-out") (class "Default")
      (node (ref "L1") (pin "2") (pinfunction "2_2") (pintype "passive"))
      (node (ref "P2") (pin "3") (pinfunction "3_3") (pintype "passive"))
      (node (ref "P2") (pin "4") (pinfunction "4_4") (pintype "passive"))
      (node (ref "R151") (pin "1") (pinfunction "1_1") (pintype "passive"))
      (node (ref "R152") (pin "1") (pinfunction "1_1") (pintype "passive"))
      (node (ref "R154") (pin "2") (pinfunction "2_2") (pintype "passive"))
      (node (ref "R162") (pin "1") (pinfunction "1_1") (pintype "passive"))
      (node (ref "R163") (pin "1") (pinfunction "1_1") (pintype "passive"))
      (node (ref "TP42") (pin "1") (pinfunction "1_1") (pintype "passive"))
      (node (ref "TP74") (pin "1") (pinfunction "1_1") (pintype "passive"))
    )
    (net (code "21") (name "GND_IN") (class "Default")
      (node (ref "C2") (pin "2") (pinfunction "2_2") (pintype "passive"))
      (node (ref "C49") (pin "2") (pinfunction "2_2") (pintype "passive"))
      (node (ref "C52") (pin "2") (pinfunction "2_2") (pintype "passive"))
      (node (ref "C56") (pin "2") (pinfunction "2_2") (pintype "passive"))
      (node (ref "C68") (pin "2") (pinfunction "2_2") (pintype "passive"))
      (node (ref "J1") (pin "2") (pinfunction "2_2") (pintype "passive"))
      (node (ref "PS1") (pin "2") (pinfunction "-VIN_2") (pintype "input"))
      (node (ref "PS1") (pin "3") (pinfunction "-VIN_3") (pintype "input"))
      (node (ref "PS2") (pin "2") (pinfunction "-VIN_2") (pintype "input"))
      (node (ref "PS2") (pin "3") (pinfunction "-VIN_3") (pintype "input"))
      (node (ref "PS3") (pin "2") (pinfunction "-VIN_2") (pintype "input"))
      (node (ref "PS3") (pin "3") (pinfunction "-VIN_3") (pintype "input"))
      (node (ref "PS4") (pin "2") (pinfunction "-VIN_2") (pintype "input"))
      (node (ref "PS4") (pin "3") (pinfunction "-VIN_3") (pintype "input"))
      (node (ref "TP57") (pin "1") (pinfunction "1_1") (pintype "passive"))
      (node (ref "U1") (pin "2") (pinfunction "-In_2") (pintype "passive"))
      (node (ref "U3") (pin "3") (pinfunction "E_3") (pintype "passive"))
    )
    (net (code "22") (name "Gate 1") (class "Default")
      (node (ref "D8") (pin "2") (pinfunction "C_2") (pintype "passive"))
      (node (ref "Q1") (pin "1") (pinfunction "G_1") (pintype "passive"))
      (node (ref "R19") (pin "2") (pinfunction "2_2") (pintype "passive"))
      (node (ref "R33") (pin "2") (pinfunction "2_2") (pintype "passive"))
      (node (ref "R7") (pin "2") (pinfunction "2_2") (pintype "passive"))
      (node (ref "R9") (pin "2") (pinfunction "2_2") (pintype "passive"))
      (node (ref "TP71") (pin "1") (pinfunction "1_1") (pintype "passive"))
    )
    (net (code "23") (name "Gate 2") (class "Default")
      (node (ref "D15") (pin "2") (pinfunction "C_2") (pintype "passive"))
      (node (ref "Q2") (pin "1") (pinfunction "G_1") (pintype "passive"))
      (node (ref "R37") (pin "2") (pinfunction "2_2") (pintype "passive"))
      (node (ref "R41") (pin "2") (pinfunction "2_2") (pintype "passive"))
      (node (ref "R50") (pin "2") (pinfunction "2_2") (pintype "passive"))
      (node (ref "R57") (pin "2") (pinfunction "2_2") (pintype "passive"))
      (node (ref "TP79") (pin "1") (pinfunction "1_1") (pintype "passive"))
    )
    (net (code "24") (name "Gate 3") (class "Default")
      (node (ref "D16") (pin "2") (pinfunction "C_2") (pintype "passive"))
      (node (ref "Q3") (pin "1") (pinfunction "G_1") (pintype "passive"))
      (node (ref "R58") (pin "2") (pinfunction "2_2") (pintype "passive"))
      (node (ref "R67") (pin "2") (pinfunction "2_2") (pintype "passive"))
      (node (ref "R69") (pin "2") (pinfunction "2_2") (pintype "passive"))
      (node (ref "R76") (pin "2") (pinfunction "2_2") (pintype "passive"))
      (node (ref "TP80") (pin "1") (pinfunction "1_1") (pintype "passive"))
    )
    (net (code "25") (name "Gate 4") (class "Default")
      (node (ref "D10") (pin "2") (pinfunction "C_2") (pintype "passive"))
      (node (ref "Q4") (pin "1") (pinfunction "G_1") (pintype "passive"))
      (node (ref "R109") (pin "2") (pinfunction "2_2") (pintype "passive"))
      (node (ref "R34") (pin "2") (pinfunction "2_2") (pintype "passive"))
      (node (ref "R89") (pin "2") (pinfunction "2_2") (pintype "passive"))
      (node (ref "R91") (pin "2") (pinfunction "2_2") (pintype "passive"))
      (node (ref "TP73") (pin "1") (pinfunction "1_1") (pintype "passive"))
    )
    (net (code "26") (name "High side FB") (class "Default")
      (node (ref "C24") (pin "2") (pinfunction "2_2") (pintype "passive"))
      (node (ref "D5") (pin "2") (pinfunction "C_2") (pintype "passive"))
      (node (ref "D6") (pin "2") (pinfunction "C_2") (pintype "passive"))
      (node (ref "F1") (pin "2") (pinfunction "2_2") (pintype "passive"))
      (node (ref "Q1") (pin "2") (pinfunction "C_2") (pintype "passive"))
      (node (ref "Q4") (pin "2") (pinfunction "C_2") (pintype "passive"))
      (node (ref "R142") (pin "1") (pinfunction "1_1") (pintype "passive"))
      (node (ref "R31") (pin "2") (pinfunction "2_2") (pintype "passive"))
      (node (ref "R32") (pin "2") (pinfunction "2_2") (pintype "passive"))
      (node (ref "TP68") (pin "1") (pinfunction "1_1") (pintype "passive"))
    )
    (net (code "27") (name "Input 400V") (class "Default")
      (node (ref "F4") (pin "1") (pinfunction "1_1") (pintype "passive"))
      (node (ref "P3") (pin "1") (pinfunction "1_1") (pintype "passive"))
      (node (ref "P3") (pin "2") (pinfunction "2_2") (pintype "passive"))
      (node (ref "R125") (pin "2") (pinfunction "2_2") (pintype "passive"))
      (node (ref "TP31") (pin "1") (pinfunction "1_1") (pintype "passive"))
    )
    (net (code "28") (name "Input voltage of FB") (class "Default")
      (node (ref "J2") (pin "15") (pinfunction "15_15") (pintype "passive"))
      (node (ref "TP59") (pin "1") (pinfunction "1_1") (pintype "passive"))
    )
    (net (code "29") (name "M1 FB command") (class "Default")
      (node (ref "FB3") (pin "1") (pinfunction "1_1") (pintype "power_in"))
      (node (ref "FB9") (pin "2") (pinfunction "2_2") (pintype "power_in"))
      (node (ref "R105") (pin "1") (pinfunction "1_1") (pintype "passive"))
      (node (ref "R26") (pin "1") (pinfunction "1_1") (pintype "passive"))
      (node (ref "TP3") (pin "1") (pinfunction "1_1") (pintype "passive"))
      (node (ref "TP49") (pin "1") (pinfunction "1_1") (pintype "passive"))
    )
    (net (code "30") (name "M2 FB command") (class "Default")
      (node (ref "FB4") (pin "1") (pinfunction "1_1") (pintype "power_in"))
      (node (ref "FB8") (pin "2") (pinfunction "2_2") (pintype "power_in"))
      (node (ref "R104") (pin "1") (pinfunction "1_1") (pintype "passive"))
      (node (ref "R60") (pin "1") (pinfunction "1_1") (pintype "passive"))
      (node (ref "TP50") (pin "1") (pinfunction "1_1") (pintype "passive"))
      (node (ref "TP9") (pin "1") (pinfunction "1_1") (pintype "passive"))
    )
    (net (code "31") (name "M3 FB command") (class "Default")
      (node (ref "FB5") (pin "1") (pinfunction "1_1") (pintype "power_in"))
      (node (ref "FB7") (pin "2") (pinfunction "2_2") (pintype "power_in"))
      (node (ref "R103") (pin "1") (pinfunction "1_1") (pintype "passive"))
      (node (ref "R82") (pin "1") (pinfunction "1_1") (pintype "passive"))
      (node (ref "TP15") (pin "1") (pinfunction "1_1") (pintype "passive"))
      (node (ref "TP51") (pin "1") (pinfunction "1_1") (pintype "passive"))
    )
    (net (code "32") (name "M4 FB command") (class "Default")
      (node (ref "FB10") (pin "1") (pinfunction "1_1") (pintype "power_in"))
      (node (ref "FB6") (pin "2") (pinfunction "2_2") (pintype "power_in"))
      (node (ref "R102") (pin "1") (pinfunction "1_1") (pintype "passive"))
      (node (ref "R115") (pin "1") (pinfunction "1_1") (pintype "passive"))
      (node (ref "TP21") (pin "1") (pinfunction "1_1") (pintype "passive"))
      (node (ref "TP52") (pin "1") (pinfunction "1_1") (pintype "passive"))
    )
    (net (code "33") (name "Net-(C11-Pad1)") (class "Default")
      (node (ref "C11") (pin "1") (pinfunction "1_1") (pintype "passive"))
      (node (ref "C12") (pin "1") (pinfunction "1_1") (pintype "passive"))
      (node (ref "C13") (pin "1") (pinfunction "1_1") (pintype "passive"))
      (node (ref "R31") (pin "1") (pinfunction "1_1") (pintype "passive"))
    )
    (net (code "34") (name "Net-(C15-Pad1)") (class "Default")
      (node (ref "C15") (pin "1") (pinfunction "1_1") (pintype "passive"))
      (node (ref "C16") (pin "1") (pinfunction "1_1") (pintype "passive"))
      (node (ref "C18") (pin "1") (pinfunction "1_1") (pintype "passive"))
      (node (ref "R32") (pin "1") (pinfunction "1_1") (pintype "passive"))
    )
    (net (code "35") (name "Net-(C22-Pad1)") (class "Default")
      (node (ref "C22") (pin "1") (pinfunction "1_1") (pintype "passive"))
      (node (ref "C25") (pin "1") (pinfunction "1_1") (pintype "passive"))
      (node (ref "F2") (pin "1") (pinfunction "1_1") (pintype "passive"))
    )
    (net (code "36") (name "Net-(C22-Pad2)") (class "Default")
      (node (ref "C22") (pin "2") (pinfunction "2_2") (pintype "passive"))
      (node (ref "C25") (pin "2") (pinfunction "2_2") (pintype "passive"))
      (node (ref "F3") (pin "2") (pinfunction "2_2") (pintype "passive"))
    )
    (net (code "37") (name "Net-(C26-Pad1)") (class "Default")
      (node (ref "C26") (pin "1") (pinfunction "1_1") (pintype "passive"))
      (node (ref "C27") (pin "1") (pinfunction "1_1") (pintype "passive"))
      (node (ref "C28") (pin "1") (pinfunction "1_1") (pintype "passive"))
      (node (ref "R52") (pin "1") (pinfunction "1_1") (pintype "passive"))
    )
    (net (code "38") (name "Net-(C29-Pad1)") (class "Default")
      (node (ref "C29") (pin "1") (pinfunction "1_1") (pintype "passive"))
      (node (ref "C30") (pin "1") (pinfunction "1_1") (pintype "passive"))
      (node (ref "C31") (pin "1") (pinfunction "1_1") (pintype "passive"))
      (node (ref "R54") (pin "1") (pinfunction "1_1") (pintype "passive"))
    )
    (net (code "39") (name "Net-(C74-Pad1)") (class "Default")
      (node (ref "C74") (pin "1") (pinfunction "1_1") (pintype "passive"))
      (node (ref "R132") (pin "2") (pinfunction "2_2") (pintype "passive"))
      (node (ref "R133") (pin "1") (pinfunction "1_1") (pintype "passive"))
    )
    (net (code "40") (name "Net-(C74-Pad2)") (class "Default")
      (node (ref "C74") (pin "2") (pinfunction "2_2") (pintype "passive"))
      (node (ref "R129") (pin "2") (pinfunction "2_2") (pintype "passive"))
      (node (ref "R130") (pin "1") (pinfunction "1_1") (pintype "passive"))
    )
    (net (code "41") (name "Net-(C75-Pad2)") (class "Default")
      (node (ref "C75") (pin "2") (pinfunction "2_2") (pintype "passive"))
      (node (ref "FB12") (pin "1") (pinfunction "1_1") (pintype "power_in"))
      (node (ref "R131") (pin "2") (pinfunction "2_2") (pintype "passive"))
      (node (ref "TP36") (pin "1") (pinfunction "1_1") (pintype "passive"))
    )
    (net (code "42") (name "Net-(C81-Pad2)") (class "Default")
      (node (ref "C81") (pin "2") (pinfunction "2_2") (pintype "passive"))
      (node (ref "R153") (pin "2") (pinfunction "2_2") (pintype "passive"))
    )
    (net (code "43") (name "Net-(C88-Pad2)") (class "Default")
      (node (ref "C88") (pin "2") (pinfunction "2_2") (pintype "passive"))
      (node (ref "R173") (pin "2") (pinfunction "2_2") (pintype "passive"))
      (node (ref "R174") (pin "1") (pinfunction "1_1") (pintype "passive"))
    )
    (net (code "44") (name "Net-(CR1-A)") (class "Default")
      (node (ref "CR1") (pin "1") (pinfunction "A_1") (pintype "passive"))
      (node (ref "CR2") (pin "2") (pinfunction "K_2") (pintype "passive"))
      (node (ref "R18") (pin "1") (pinfunction "1_1") (pintype "passive"))
      (node (ref "R30") (pin "2") (pinfunction "2_2") (pintype "passive"))
      (node (ref "TP5") (pin "1") (pinfunction "1_1") (pintype "passive"))
      (node (ref "U5") (pin "5") (pinfunction "VO_5") (pintype "output"))
    )
    (net (code "45") (name "Net-(CR3-K)") (class "Default")
      (node (ref "CR3") (pin "2") (pinfunction "K_2") (pintype "passive"))
      (node (ref "CR4") (pin "1") (pinfunction "A_1") (pintype "passive"))
      (node (ref "D3") (pin "2") (pinfunction "C_2") (pintype "passive"))
      (node (ref "D4") (pin "2") (pinfunction "C_2") (pintype "passive"))
      (node (ref "R13") (pin "1") (pinfunction "1_1") (pintype "passive"))
      (node (ref "R22") (pin "1") (pinfunction "1_1") (pintype "passive"))
      (node (ref "TP7") (pin "1") (pinfunction "1_1") (pintype "passive"))
      (node (ref "U6") (pin "6") (pinfunction "OUT_6") (pintype "output"))
      (node (ref "U6") (pin "7") (pinfunction "OUT_7") (pintype "output"))
    )
    (net (code "46") (name "Net-(CR5-A)") (class "Default")
      (node (ref "CR5") (pin "1") (pinfunction "A_1") (pintype "passive"))
      (node (ref "CR6") (pin "2") (pinfunction "K_2") (pintype "passive"))
      (node (ref "R49") (pin "1") (pinfunction "1_1") (pintype "passive"))
      (node (ref "R64") (pin "2") (pinfunction "2_2") (pintype "passive"))
      (node (ref "TP11") (pin "1") (pinfunction "1_1") (pintype "passive"))
      (node (ref "U8") (pin "5") (pinfunction "VO_5") (pintype "output"))
    )
    (net (code "47") (name "Net-(CR7-K)") (class "Default")
      (node (ref "CR7") (pin "2") (pinfunction "K_2") (pintype "passive"))
      (node (ref "CR8") (pin "1") (pinfunction "A_1") (pintype "passive"))
      (node (ref "D11") (pin "2") (pinfunction "C_2") (pintype "passive"))
      (node (ref "D12") (pin "2") (pinfunction "C_2") (pintype "passive"))
      (node (ref "R46") (pin "1") (pinfunction "1_1") (pintype "passive"))
      (node (ref "R55") (pin "1") (pinfunction "1_1") (pintype "passive"))
      (node (ref "TP13") (pin "1") (pinfunction "1_1") (pintype "passive"))
      (node (ref "U9") (pin "6") (pinfunction "OUT_6") (pintype "output"))
      (node (ref "U9") (pin "7") (pinfunction "OUT_7") (pintype "output"))
    )
    (net (code "48") (name "Net-(CR10-K)") (class "Default")
      (node (ref "CR10") (pin "2") (pinfunction "K_2") (pintype "passive"))
      (node (ref "CR9") (pin "1") (pinfunction "A_1") (pintype "passive"))
      (node (ref "R75") (pin "1") (pinfunction "1_1") (pintype "passive"))
      (node (ref "R86") (pin "2") (pinfunction "2_2") (pintype "passive"))
      (node (ref "TP17") (pin "1") (pinfunction "1_1") (pintype "passive"))
      (node (ref "U11") (pin "5") (pinfunction "VO_5") (pintype "output"))
    )
    (net (code "49") (name "Net-(CR11-K)") (class "Default")
      (node (ref "CR11") (pin "2") (pinfunction "K_2") (pintype "passive"))
      (node (ref "CR12") (pin "1") (pinfunction "A_1") (pintype "passive"))
      (node (ref "D19") (pin "2") (pinfunction "C_2") (pintype "passive"))
      (node (ref "D20") (pin "2") (pinfunction "C_2") (pintype "passive"))
      (node (ref "R72") (pin "1") (pinfunction "1_1") (pintype "passive"))
      (node (ref "R79") (pin "1") (pinfunction "1_1") (pintype "passive"))
      (node (ref "TP19") (pin "1") (pinfunction "1_1") (pintype "passive"))
      (node (ref "U12") (pin "6") (pinfunction "OUT_6") (pintype "output"))
      (node (ref "U12") (pin "7") (pinfunction "OUT_7") (pintype "output"))
    )
    (net (code "50") (name "Net-(CR13-A)") (class "Default")
      (node (ref "CR13") (pin "1") (pinfunction "A_1") (pintype "passive"))
      (node (ref "CR14") (pin "2") (pinfunction "K_2") (pintype "passive"))
      (node (ref "R108") (pin "1") (pinfunction "1_1") (pintype "passive"))
      (node (ref "R120") (pin "2") (pinfunction "2_2") (pintype "passive"))
      (node (ref "TP23") (pin "1") (pinfunction "1_1") (pintype "passive"))
      (node (ref "U14") (pin "5") (pinfunction "VO_5") (pintype "output"))
    )
    (net (code "51") (name "Net-(CR15-K)") (class "Default")
      (node (ref "CR15") (pin "2") (pinfunction "K_2") (pintype "passive"))
      (node (ref "CR16") (pin "1") (pinfunction "A_1") (pintype "passive"))
      (node (ref "D21") (pin "2") (pinfunction "C_2") (pintype "passive"))
      (node (ref "D22") (pin "2") (pinfunction "C_2") (pintype "passive"))
      (node (ref "R112") (pin "1") (pinfunction "1_1") (pintype "passive"))
      (node (ref "R97") (pin "1") (pinfunction "1_1") (pintype "passive"))
      (node (ref "TP27") (pin "1") (pinfunction "1_1") (pintype "passive"))
      (node (ref "U15") (pin "6") (pinfunction "OUT_6") (pintype "output"))
      (node (ref "U15") (pin "7") (pinfunction "OUT_7") (pintype "output"))
    )
    (net (code "52") (name "Net-(CR17-K)") (class "Default")
      (node (ref "CR17") (pin "2") (pinfunction "K_2") (pintype "passive"))
      (node (ref "CR18") (pin "2") (pinfunction "K_2") (pintype "passive"))
    )
    (net (code "53") (name "Net-(CR18-A)") (class "Default")
      (node (ref "C21") (pin "2") (pinfunction "2_2") (pintype "passive"))
      (node (ref "CR18") (pin "1") (pinfunction "A_1") (pintype "passive"))
      (node (ref "F1") (pin "1") (pinfunction "1_1") (pintype "passive"))
      (node (ref "F4") (pin "2") (pinfunction "2_2") (pintype "passive"))
      (node (ref "R38") (pin "1") (pinfunction "1_1") (pintype "passive"))
      (node (ref "R39") (pin "1") (pinfunction "1_1") (pintype "passive"))
    )
    (net (code "54") (name "Net-(D1-K)") (class "Default")
      (node (ref "D1") (pin "2") (pinfunction "K_2") (pintype "passive"))
      (node (ref "D2") (pin "2") (pinfunction "K_2") (pintype "passive"))
    )
    (net (code "55") (name "Net-(D3-A)") (class "Default")
      (node (ref "D3") (pin "1") (pinfunction "A_1") (pintype "passive"))
      (node (ref "D4") (pin "1") (pinfunction "A_1") (pintype "passive"))
      (node (ref "R7") (pin "1") (pinfunction "1_1") (pintype "passive"))
      (node (ref "R9") (pin "1") (pinfunction "1_1") (pintype "passive"))
    )
    (net (code "56") (name "Net-(D11-A)") (class "Default")
      (node (ref "D11") (pin "1") (pinfunction "A_1") (pintype "passive"))
      (node (ref "D12") (pin "1") (pinfunction "A_1") (pintype "passive"))
      (node (ref "R37") (pin "1") (pinfunction "1_1") (pintype "passive"))
      (node (ref "R41") (pin "1") (pinfunction "1_1") (pintype "passive"))
    )
    (net (code "57") (name "Net-(D19-A)") (class "Default")
      (node (ref "D19") (pin "1") (pinfunction "A_1") (pintype "passive"))
      (node (ref "D20") (pin "1") (pinfunction "A_1") (pintype "passive"))
      (node (ref "R67") (pin "1") (pinfunction "1_1") (pintype "passive"))
      (node (ref "R69") (pin "1") (pinfunction "1_1") (pintype "passive"))
    )
    (net (code "58") (name "Net-(D21-A)") (class "Default")
      (node (ref "D21") (pin "1") (pinfunction "A_1") (pintype "passive"))
      (node (ref "D22") (pin "1") (pinfunction "A_1") (pintype "passive"))
      (node (ref "R89") (pin "1") (pinfunction "1_1") (pintype "passive"))
      (node (ref "R91") (pin "1") (pinfunction "1_1") (pintype "passive"))
    )
    (net (code "59") (name "Net-(DS1-K)") (class "Default")
      (node (ref "DS1") (pin "2") (pinfunction "K_2") (pintype "passive"))
      (node (ref "R1") (pin "1") (pinfunction "1_1") (pintype "passive"))
    )
    (net (code "60") (name "Net-(DS2-A)") (class "Default")
      (node (ref "DS2") (pin "1") (pinfunction "A_1") (pintype "passive"))
      (node (ref "R5") (pin "1") (pinfunction "1_1") (pintype "passive"))
      (node (ref "TP1") (pin "1") (pinfunction "1_1") (pintype "passive"))
      (node (ref "U2") (pin "4") (pinfunction "Y_4") (pintype "output"))
    )
    (net (code "61") (name "Net-(DS2-K)") (class "Default")
      (node (ref "DS2") (pin "2") (pinfunction "K_2") (pintype "passive"))
      (node (ref "R10") (pin "1") (pinfunction "1_1") (pintype "passive"))
    )
    (net (code "62") (name "Net-(DS3-A)") (class "Default")
      (node (ref "DS3") (pin "1") (pinfunction "A_1") (pintype "passive"))
      (node (ref "R17") (pin "1") (pinfunction "1_1") (pintype "passive"))
      (node (ref "TP4") (pin "1") (pinfunction "1_1") (pintype "passive"))
      (node (ref "U4") (pin "4") (pinfunction "Y_4") (pintype "output"))
    )
    (net (code "63") (name "Net-(DS3-K)") (class "Default")
      (node (ref "DS3") (pin "2") (pinfunction "K_2") (pintype "passive"))
      (node (ref "R28") (pin "1") (pinfunction "1_1") (pintype "passive"))
    )
    (net (code "64") (name "Net-(DS4-A)") (class "Default")
      (node (ref "DS4") (pin "1") (pinfunction "A_1") (pintype "passive"))
      (node (ref "R48") (pin "1") (pinfunction "1_1") (pintype "passive"))
      (node (ref "TP10") (pin "1") (pinfunction "1_1") (pintype "passive"))
      (node (ref "U7") (pin "4") (pinfunction "Y_4") (pintype "output"))
    )
    (net (code "65") (name "Net-(DS4-K)") (class "Default")
      (node (ref "DS4") (pin "2") (pinfunction "K_2") (pintype "passive"))
      (node (ref "R62") (pin "1") (pinfunction "1_1") (pintype "passive"))
    )
    (net (code "66") (name "Net-(DS5-A)") (class "Default")
      (node (ref "DS5") (pin "1") (pinfunction "A_1") (pintype "passive"))
      (node (ref "R74") (pin "1") (pinfunction "1_1") (pintype "passive"))
      (node (ref "TP16") (pin "1") (pinfunction "1_1") (pintype "passive"))
      (node (ref "U10") (pin "4") (pinfunction "Y_4") (pintype "output"))
    )
    (net (code "67") (name "Net-(DS5-K)") (class "Default")
      (node (ref "DS5") (pin "2") (pinfunction "K_2") (pintype "passive"))
      (node (ref "R84") (pin "1") (pinfunction "1_1") (pintype "passive"))
    )
    (net (code "68") (name "Net-(DS6-K)") (class "Default")
      (node (ref "DS6") (pin "2") (pinfunction "K_2") (pintype "passive"))
      (node (ref "R87") (pin "1") (pinfunction "1_1") (pintype "passive"))
    )
    (net (code "69") (name "Net-(DS7-K)") (class "Default")
      (node (ref "DS7") (pin "2") (pinfunction "K_2") (pintype "passive"))
      (node (ref "R88") (pin "1") (pinfunction "1_1") (pintype "passive"))
    )
    (net (code "70") (name "Net-(DS8-K)") (class "Default")
      (node (ref "DS8") (pin "2") (pinfunction "K_2") (pintype "passive"))
      (node (ref "R94") (pin "1") (pinfunction "1_1") (pintype "passive"))
    )
    (net (code "71") (name "Net-(DS9-A)") (class "Default")
      (node (ref "DS9") (pin "1") (pinfunction "A_1") (pintype "passive"))
      (node (ref "R107") (pin "1") (pinfunction "1_1") (pintype "passive"))
      (node (ref "TP22") (pin "1") (pinfunction "1_1") (pintype "passive"))
      (node (ref "U13") (pin "4") (pinfunction "Y_4") (pintype "output"))
    )
    (net (code "72") (name "Net-(DS9-K)") (class "Default")
      (node (ref "DS9") (pin "2") (pinfunction "K_2") (pintype "passive"))
      (node (ref "R117") (pin "1") (pinfunction "1_1") (pintype "passive"))
    )
    (net (code "73") (name "Net-(DS10-K)") (class "Default")
      (node (ref "DS10") (pin "2") (pinfunction "K_2") (pintype "passive"))
      (node (ref "R121") (pin "1") (pinfunction "1_1") (pintype "passive"))
    )
    (net (code "74") (name "Net-(DS11-K)") (class "Default")
      (node (ref "DS11") (pin "2") (pinfunction "K_2") (pintype "passive"))
      (node (ref "R119") (pin "1") (pinfunction "1_1") (pintype "passive"))
    )
    (net (code "75") (name "Net-(DS12-K)") (class "Default")
      (node (ref "DS12") (pin "2") (pinfunction "K_2") (pintype "passive"))
      (node (ref "R122") (pin "1") (pinfunction "1_1") (pintype "passive"))
    )
    (net (code "76") (name "Net-(F3-Pad1)") (class "Default")
      (node (ref "F3") (pin "1") (pinfunction "1_1") (pintype "passive"))
      (node (ref "U17") (pin "10") (pinfunction "OUT_10") (pintype "passive"))
      (node (ref "U17") (pin "8") (pinfunction "OUT_8") (pintype "passive"))
      (node (ref "U17") (pin "9") (pinfunction "OUT_9") (pintype "passive"))
    )
    (net (code "77") (name "Net-(FB1-Pad2)") (class "Default")
      (node (ref "FB1") (pin "2") (pinfunction "2_2") (pintype "power_in"))
      (node (ref "R4") (pin "1") (pinfunction "1_1") (pintype "passive"))
    )
    (net (code "78") (name "Net-(FB2-Pad1)") (class "Default")
      (node (ref "FB2") (pin "1") (pinfunction "1_1") (pintype "power_in"))
      (node (ref "P1") (pin "4") (pinfunction "4_4") (pintype "passive"))
      (node (ref "R24") (pin "1") (pinfunction "1_1") (pintype "passive"))
    )
    (net (code "79") (name "Net-(FB3-Pad2)") (class "Default")
      (node (ref "FB3") (pin "2") (pinfunction "2_2") (pintype "power_in"))
      (node (ref "R16") (pin "1") (pinfunction "1_1") (pintype "passive"))
      (node (ref "R27") (pin "1") (pinfunction "1_1") (pintype "passive"))
    )
    (net (code "80") (name "Net-(FB4-Pad2)") (class "Default")
      (node (ref "FB4") (pin "2") (pinfunction "2_2") (pintype "power_in"))
      (node (ref "R47") (pin "1") (pinfunction "1_1") (pintype "passive"))
      (node (ref "R61") (pin "1") (pinfunction "1_1") (pintype "passive"))
    )
    (net (code "81") (name "Net-(FB5-Pad2)") (class "Default")
      (node (ref "FB5") (pin "2") (pinfunction "2_2") (pintype "power_in"))
      (node (ref "R73") (pin "1") (pinfunction "1_1") (pintype "passive"))
      (node (ref "R83") (pin "1") (pinfunction "1_1") (pintype "passive"))
    )
    (net (code "82") (name "Net-(FB6-Pad1)") (class "Default")
      (node (ref "FB6") (pin "1") (pinfunction "1_1") (pintype "power_in"))
      (node (ref "J2") (pin "21") (pinfunction "21_21") (pintype "passive"))
      (node (ref "R98") (pin "1") (pinfunction "1_1") (pintype "passive"))
    )
    (net (code "83") (name "Net-(FB7-Pad1)") (class "Default")
      (node (ref "FB7") (pin "1") (pinfunction "1_1") (pintype "power_in"))
      (node (ref "J2") (pin "9") (pinfunction "9_9") (pintype "passive"))
      (node (ref "R99") (pin "1") (pinfunction "1_1") (pintype "passive"))
    )
    (net (code "84") (name "Net-(FB8-Pad1)") (class "Default")
      (node (ref "FB8") (pin "1") (pinfunction "1_1") (pintype "power_in"))
      (node (ref "J2") (pin "22") (pinfunction "22_22") (pintype "passive"))
      (node (ref "R100") (pin "1") (pinfunction "1_1") (pintype "passive"))
    )
    (net (code "85") (name "Net-(FB9-Pad1)") (class "Default")
      (node (ref "FB9") (pin "1") (pinfunction "1_1") (pintype "power_in"))
      (node (ref "J2") (pin "10") (pinfunction "10_10") (pintype "passive"))
      (node (ref "R101") (pin "1") (pinfunction "1_1") (pintype "passive"))
    )
    (net (code "86") (name "Net-(FB10-Pad2)") (class "Default")
      (node (ref "FB10") (pin "2") (pinfunction "2_2") (pintype "power_in"))
      (node (ref "R106") (pin "1") (pinfunction "1_1") (pintype "passive"))
      (node (ref "R116") (pin "1") (pinfunction "1_1") (pintype "passive"))
    )
    (net (code "87") (name "Net-(FB13-Pad1)") (class "Default")
      (node (ref "FB13") (pin "1") (pinfunction "1_1") (pintype "power_in"))
      (node (ref "R174") (pin "2") (pinfunction "2_2") (pintype "passive"))
      (node (ref "R175") (pin "1") (pinfunction "1_1") (pintype "passive"))
    )
    (net (code "88") (name "Net-(P1-Pad3)") (class "Default")
      (node (ref "P1") (pin "3") (pinfunction "3_3") (pintype "passive"))
      (node (ref "R14") (pin "2") (pinfunction "2_2") (pintype "passive"))
      (node (ref "R15") (pin "2") (pinfunction "2_2") (pintype "passive"))
    )
    (net (code "89") (name "Net-(Q5-GND1)") (class "Default")
      (node (ref "C84") (pin "2") (pinfunction "2_2") (pintype "passive"))
      (node (ref "C85") (pin "2") (pinfunction "2_2") (pintype "passive"))
      (node (ref "Q5") (pin "4") (pinfunction "GND1_4") (pintype "power_in"))
      (node (ref "R154") (pin "1") (pinfunction "1_1") (pintype "passive"))
      (node (ref "R162") (pin "2") (pinfunction "2_2") (pintype "passive"))
      (node (ref "R168") (pin "1") (pinfunction "1_1") (pintype "passive"))
      (node (ref "TP46") (pin "1") (pinfunction "1_1") (pintype "passive"))
    )
    (net (code "90") (name "Net-(Q5-SHDN)") (class "Default")
      (node (ref "Q5") (pin "3") (pinfunction "SHDN_3") (pintype "input"))
      (node (ref "R163") (pin "2") (pinfunction "2_2") (pintype "passive"))
      (node (ref "R167") (pin "1") (pinfunction "1_1") (pintype "passive"))
    )
    (net (code "91") (name "Net-(Q5-VDD2)") (class "Default")
      (node (ref "C82") (pin "1") (pinfunction "1_1") (pintype "passive"))
      (node (ref "C83") (pin "1") (pinfunction "1_1") (pintype "passive"))
      (node (ref "Q5") (pin "8") (pinfunction "VDD2_8") (pintype "power_in"))
      (node (ref "R149") (pin "1") (pinfunction "1_1") (pintype "passive"))
      (node (ref "R150") (pin "1") (pinfunction "1_1") (pintype "passive"))
    )
    (net (code "92") (name "Net-(Q5-VIN)") (class "Default")
      (node (ref "C84") (pin "1") (pinfunction "1_1") (pintype "passive"))
      (node (ref "Q5") (pin "2") (pinfunction "VIN_2") (pintype "power_in"))
      (node (ref "R147") (pin "1") (pinfunction "1_1") (pintype "passive"))
      (node (ref "R148") (pin "1") (pinfunction "1_1") (pintype "passive"))
      (node (ref "R151") (pin "2") (pinfunction "2_2") (pintype "passive"))
      (node (ref "R152") (pin "2") (pinfunction "2_2") (pintype "passive"))
      (node (ref "TP41") (pin "1") (pinfunction "1_1") (pintype "passive"))
    )
    (net (code "93") (name "Net-(Q5-VOUT+)") (class "Default")
      (node (ref "Q5") (pin "7") (pinfunction "VOUT+_7") (pintype "passive"))
      (node (ref "R153") (pin "1") (pinfunction "1_1") (pintype "passive"))
      (node (ref "R157") (pin "2") (pinfunction "2_2") (pintype "passive"))
      (node (ref "TP43") (pin "1") (pinfunction "1_1") (pintype "passive"))
    )
    (net (code "94") (name "Net-(Q5-VOUT-)") (class "Default")
      (node (ref "C81") (pin "1") (pinfunction "1_1") (pintype "passive"))
      (node (ref "Q5") (pin "6") (pinfunction "VOUT-_6") (pintype "passive"))
      (node (ref "R158") (pin "2") (pinfunction "2_2") (pintype "passive"))
      (node (ref "R159") (pin "1") (pinfunction "1_1") (pintype "passive"))
      (node (ref "TP44") (pin "1") (pinfunction "1_1") (pintype "passive"))
    )
    (net (code "95") (name "Net-(R13-Pad2)") (class "Default")
      (node (ref "R13") (pin "2") (pinfunction "2_2") (pintype "passive"))
      (node (ref "R19") (pin "1") (pinfunction "1_1") (pintype "passive"))
      (node (ref "R22") (pin "2") (pinfunction "2_2") (pintype "passive"))
    )
    (net (code "96") (name "Net-(R38-Pad2)") (class "Default")
      (node (ref "R38") (pin "2") (pinfunction "2_2") (pintype "passive"))
      (node (ref "R42") (pin "1") (pinfunction "1_1") (pintype "passive"))
    )
    (net (code "97") (name "Net-(R39-Pad2)") (class "Default")
      (node (ref "R39") (pin "2") (pinfunction "2_2") (pintype "passive"))
      (node (ref "R43") (pin "1") (pinfunction "1_1") (pintype "passive"))
    )
    (net (code "98") (name "Net-(R46-Pad2)") (class "Default")
      (node (ref "R46") (pin "2") (pinfunction "2_2") (pintype "passive"))
      (node (ref "R50") (pin "1") (pinfunction "1_1") (pintype "passive"))
      (node (ref "R55") (pin "2") (pinfunction "2_2") (pintype "passive"))
    )
    (net (code "99") (name "Net-(R72-Pad2)") (class "Default")
      (node (ref "R72") (pin "2") (pinfunction "2_2") (pintype "passive"))
      (node (ref "R76") (pin "1") (pinfunction "1_1") (pintype "passive"))
      (node (ref "R79") (pin "2") (pinfunction "2_2") (pintype "passive"))
    )
    (net (code "100") (name "Net-(R109-Pad1)") (class "Default")
      (node (ref "R109") (pin "1") (pinfunction "1_1") (pintype "passive"))
      (node (ref "R112") (pin "2") (pinfunction "2_2") (pintype "passive"))
      (node (ref "R97") (pin "2") (pinfunction "2_2") (pintype "passive"))
    )
    (net (code "101") (name "Net-(R123-Pad1)") (class "Default")
      (node (ref "R123") (pin "1") (pinfunction "1_1") (pintype "passive"))
      (node (ref "R124") (pin "2") (pinfunction "2_2") (pintype "passive"))
      (node (ref "R132") (pin "1") (pinfunction "1_1") (pintype "passive"))
      (node (ref "TP30") (pin "1") (pinfunction "1_1") (pintype "passive"))
    )
    (net (code "102") (name "Net-(R123-Pad2)") (class "Default")
      (node (ref "R123") (pin "2") (pinfunction "2_2") (pintype "passive"))
      (node (ref "U17") (pin "11") (pinfunction "OUT_11") (pintype "passive"))
    )
    (net (code "103") (name "Net-(R126-Pad2)") (class "Default")
      (node (ref "R126") (pin "2") (pinfunction "2_2") (pintype "passive"))
      (node (ref "R127") (pin "1") (pinfunction "1_1") (pintype "passive"))
    )
    (net (code "104") (name "Net-(R141-Pad2)") (class "Default")
      (node (ref "R141") (pin "2") (pinfunction "2_2") (pintype "passive"))
      (node (ref "R142") (pin "2") (pinfunction "2_2") (pintype "passive"))
      (node (ref "R147") (pin "2") (pinfunction "2_2") (pintype "passive"))
      (node (ref "R148") (pin "2") (pinfunction "2_2") (pintype "passive"))
      (node (ref "TP40") (pin "1") (pinfunction "1_1") (pintype "passive"))
    )
    (net (code "105") (name "Net-(R155-Pad1)") (class "Default")
      (node (ref "R155") (pin "1") (pinfunction "1_1") (pintype "passive"))
      (node (ref "R156") (pin "2") (pinfunction "2_2") (pintype "passive"))
    )
    (net (code "106") (name "Net-(R156-Pad1)") (class "Default")
      (node (ref "R156") (pin "1") (pinfunction "1_1") (pintype "passive"))
      (node (ref "R160") (pin "1") (pinfunction "1_1") (pintype "passive"))
      (node (ref "R161") (pin "1") (pinfunction "1_1") (pintype "passive"))
    )
    (net (code "107") (name "Net-(R161-Pad2)") (class "Default")
      (node (ref "R161") (pin "2") (pinfunction "2_2") (pintype "passive"))
      (node (ref "R166") (pin "1") (pinfunction "1_1") (pintype "passive"))
      (node (ref "R171") (pin "2") (pinfunction "2_2") (pintype "passive"))
      (node (ref "R172") (pin "1") (pinfunction "1_1") (pintype "passive"))
    )
    (net (code "108") (name "Net-(R165-Pad1)") (class "Default")
      (node (ref "R165") (pin "1") (pinfunction "1_1") (pintype "passive"))
      (node (ref "R166") (pin "2") (pinfunction "2_2") (pintype "passive"))
    )
    (net (code "109") (name "Net-(U1-on{slash}off)") (class "Default")
      (node (ref "U1") (pin "6") (pinfunction "on/off_6") (pintype "passive"))
      (node (ref "U3") (pin "4") (pinfunction "C_4") (pintype "passive"))
    )
    (net (code "110") (name "Net-(U2-A)") (class "Default")
      (node (ref "R4") (pin "2") (pinfunction "2_2") (pintype "passive"))
      (node (ref "U2") (pin "2") (pinfunction "A_2") (pintype "input"))
    )
    (net (code "111") (name "Net-(U2-NC)") (class "Default")
      (node (ref "R6") (pin "2") (pinfunction "2_2") (pintype "passive"))
      (node (ref "U2") (pin "1") (pinfunction "NC_1") (pintype "passive"))
    )
    (net (code "112") (name "Net-(U2-VCC)") (class "Default")
      (node (ref "C1") (pin "1") (pinfunction "1_1") (pintype "passive"))
      (node (ref "R2") (pin "1") (pinfunction "1_1") (pintype "passive"))
      (node (ref "R3") (pin "2") (pinfunction "2_2") (pintype "passive"))
      (node (ref "U2") (pin "5") (pinfunction "VCC_5") (pintype "power_in"))
    )
    (net (code "113") (name "Net-(U3-A)") (class "Default")
      (node (ref "R5") (pin "2") (pinfunction "2_2") (pintype "passive"))
      (node (ref "U3") (pin "1") (pinfunction "A_1") (pintype "passive"))
    )
    (net (code "114") (name "Net-(U4-A)") (class "Default")
      (node (ref "R16") (pin "2") (pinfunction "2_2") (pintype "passive"))
      (node (ref "U4") (pin "2") (pinfunction "A_2") (pintype "input"))
    )
    (net (code "115") (name "Net-(U4-NC)") (class "Default")
      (node (ref "R21") (pin "2") (pinfunction "2_2") (pintype "passive"))
      (node (ref "U4") (pin "1") (pinfunction "NC_1") (pintype "passive"))
    )
    (net (code "116") (name "Net-(U4-VCC)") (class "Default")
      (node (ref "C5") (pin "1") (pinfunction "1_1") (pintype "passive"))
      (node (ref "R11") (pin "1") (pinfunction "1_1") (pintype "passive"))
      (node (ref "R12") (pin "2") (pinfunction "2_2") (pintype "passive"))
      (node (ref "U4") (pin "5") (pinfunction "VCC_5") (pintype "power_in"))
    )
    (net (code "117") (name "Net-(U5-ANODE)") (class "Default")
      (node (ref "R17") (pin "2") (pinfunction "2_2") (pintype "passive"))
      (node (ref "R23") (pin "1") (pinfunction "1_1") (pintype "passive"))
      (node (ref "U5") (pin "1") (pinfunction "ANODE_1") (pintype "passive"))
    )
    (net (code "118") (name "Net-(U5-NC)") (class "Default")
      (node (ref "R25") (pin "2") (pinfunction "2_2") (pintype "passive"))
      (node (ref "U5") (pin "2") (pinfunction "NC_2") (pintype "passive"))
    )
    (net (code "119") (name "Net-(U6-IN)") (class "Default")
      (node (ref "R18") (pin "2") (pinfunction "2_2") (pintype "passive"))
      (node (ref "U6") (pin "2") (pinfunction "IN_2") (pintype "input"))
    )
    (net (code "120") (name "Net-(U6-NC)") (class "Default")
      (node (ref "R29") (pin "2") (pinfunction "2_2") (pintype "passive"))
      (node (ref "U6") (pin "3") (pinfunction "NC_3") (pintype "passive"))
    )
    (net (code "121") (name "Net-(U7-A)") (class "Default")
      (node (ref "R47") (pin "2") (pinfunction "2_2") (pintype "passive"))
      (node (ref "U7") (pin "2") (pinfunction "A_2") (pintype "input"))
    )
    (net (code "122") (name "Net-(U7-NC)") (class "Default")
      (node (ref "R53") (pin "2") (pinfunction "2_2") (pintype "passive"))
      (node (ref "U7") (pin "1") (pinfunction "NC_1") (pintype "passive"))
    )
    (net (code "123") (name "Net-(U7-VCC)") (class "Default")
      (node (ref "C20") (pin "1") (pinfunction "1_1") (pintype "passive"))
      (node (ref "R44") (pin "1") (pinfunction "1_1") (pintype "passive"))
      (node (ref "R45") (pin "2") (pinfunction "2_2") (pintype "passive"))
      (node (ref "U7") (pin "5") (pinfunction "VCC_5") (pintype "power_in"))
    )
    (net (code "124") (name "Net-(U8-ANODE)") (class "Default")
      (node (ref "R48") (pin "2") (pinfunction "2_2") (pintype "passive"))
      (node (ref "R56") (pin "1") (pinfunction "1_1") (pintype "passive"))
      (node (ref "U8") (pin "1") (pinfunction "ANODE_1") (pintype "passive"))
    )
    (net (code "125") (name "Net-(U8-NC)") (class "Default")
      (node (ref "R59") (pin "2") (pinfunction "2_2") (pintype "passive"))
      (node (ref "U8") (pin "2") (pinfunction "NC_2") (pintype "passive"))
    )
    (net (code "126") (name "Net-(U9-IN)") (class "Default")
      (node (ref "R49") (pin "2") (pinfunction "2_2") (pintype "passive"))
      (node (ref "U9") (pin "2") (pinfunction "IN_2") (pintype "input"))
    )
    (net (code "127") (name "Net-(U9-NC)") (class "Default")
      (node (ref "R63") (pin "2") (pinfunction "2_2") (pintype "passive"))
      (node (ref "U9") (pin "3") (pinfunction "NC_3") (pintype "passive"))
    )
    (net (code "128") (name "Net-(U10-A)") (class "Default")
      (node (ref "R73") (pin "2") (pinfunction "2_2") (pintype "passive"))
      (node (ref "U10") (pin "2") (pinfunction "A_2") (pintype "input"))
    )
    (net (code "129") (name "Net-(U10-NC)") (class "Default")
      (node (ref "R78") (pin "2") (pinfunction "2_2") (pintype "passive"))
      (node (ref "U10") (pin "1") (pinfunction "NC_1") (pintype "passive"))
    )
    (net (code "130") (name "Net-(U10-VCC)") (class "Default")
      (node (ref "C41") (pin "1") (pinfunction "1_1") (pintype "passive"))
      (node (ref "R70") (pin "1") (pinfunction "1_1") (pintype "passive"))
      (node (ref "R71") (pin "2") (pinfunction "2_2") (pintype "passive"))
      (node (ref "U10") (pin "5") (pinfunction "VCC_5") (pintype "power_in"))
    )
    (net (code "131") (name "Net-(U11-ANODE)") (class "Default")
      (node (ref "R74") (pin "2") (pinfunction "2_2") (pintype "passive"))
      (node (ref "R80") (pin "1") (pinfunction "1_1") (pintype "passive"))
      (node (ref "U11") (pin "1") (pinfunction "ANODE_1") (pintype "passive"))
    )
    (net (code "132") (name "Net-(U11-NC)") (class "Default")
      (node (ref "R81") (pin "2") (pinfunction "2_2") (pintype "passive"))
      (node (ref "U11") (pin "2") (pinfunction "NC_2") (pintype "passive"))
    )
    (net (code "133") (name "Net-(U12-IN)") (class "Default")
      (node (ref "R75") (pin "2") (pinfunction "2_2") (pintype "passive"))
      (node (ref "U12") (pin "2") (pinfunction "IN_2") (pintype "input"))
    )
    (net (code "134") (name "Net-(U12-NC)") (class "Default")
      (node (ref "R85") (pin "2") (pinfunction "2_2") (pintype "passive"))
      (node (ref "U12") (pin "3") (pinfunction "NC_3") (pintype "passive"))
    )
    (net (code "135") (name "Net-(U13-A)") (class "Default")
      (node (ref "R106") (pin "2") (pinfunction "2_2") (pintype "passive"))
      (node (ref "U13") (pin "2") (pinfunction "A_2") (pintype "input"))
    )
    (net (code "136") (name "Net-(U13-NC)") (class "Default")
      (node (ref "R111") (pin "2") (pinfunction "2_2") (pintype "passive"))
      (node (ref "U13") (pin "1") (pinfunction "NC_1") (pintype "passive"))
    )
    (net (code "137") (name "Net-(U13-VCC)") (class "Default")
      (node (ref "C53") (pin "1") (pinfunction "1_1") (pintype "passive"))
      (node (ref "R95") (pin "1") (pinfunction "1_1") (pintype "passive"))
      (node (ref "R96") (pin "2") (pinfunction "2_2") (pintype "passive"))
      (node (ref "U13") (pin "5") (pinfunction "VCC_5") (pintype "power_in"))
    )
    (net (code "138") (name "Net-(U14-ANODE)") (class "Default")
      (node (ref "R107") (pin "2") (pinfunction "2_2") (pintype "passive"))
      (node (ref "R113") (pin "1") (pinfunction "1_1") (pintype "passive"))
      (node (ref "U14") (pin "1") (pinfunction "ANODE_1") (pintype "passive"))
    )
    (net (code "139") (name "Net-(U14-NC)") (class "Default")
      (node (ref "R114") (pin "2") (pinfunction "2_2") (pintype "passive"))
      (node (ref "U14") (pin "2") (pinfunction "NC_2") (pintype "passive"))
    )
    (net (code "140") (name "Net-(U15-IN)") (class "Default")
      (node (ref "R108") (pin "2") (pinfunction "2_2") (pintype "passive"))
      (node (ref "U15") (pin "2") (pinfunction "IN_2") (pintype "input"))
    )
    (net (code "141") (name "Net-(U15-NC)") (class "Default")
      (node (ref "R118") (pin "2") (pinfunction "2_2") (pintype "passive"))
      (node (ref "U15") (pin "3") (pinfunction "NC_3") (pintype "passive"))
    )
    (net (code "142") (name "Net-(U16-IN)") (class "Default")
      (node (ref "C62") (pin "2") (pinfunction "2_2") (pintype "passive"))
      (node (ref "C63") (pin "2") (pinfunction "2_2") (pintype "passive"))
      (node (ref "FB11") (pin "2") (pinfunction "2_2") (pintype "power_in"))
      (node (ref "U16") (pin "1") (pinfunction "~{SHDN}_1") (pintype "input"))
      (node (ref "U16") (pin "2") (pinfunction "IN_2") (pintype "power_in"))
    )
    (net (code "143") (name "Net-(U19-IN+)") (class "Default")
      (node (ref "C77") (pin "2") (pinfunction "2_2") (pintype "passive"))
      (node (ref "R133") (pin "2") (pinfunction "2_2") (pintype "passive"))
      (node (ref "R136") (pin "2") (pinfunction "2_2") (pintype "passive"))
      (node (ref "TP37") (pin "1") (pinfunction "1_1") (pintype "passive"))
      (node (ref "U19") (pin "3") (pinfunction "IN+_3") (pintype "input"))
    )
    (net (code "144") (name "Net-(U19-IN-)") (class "Default")
      (node (ref "C70") (pin "2") (pinfunction "2_2") (pintype "passive"))
      (node (ref "R126") (pin "1") (pinfunction "1_1") (pintype "passive"))
      (node (ref "R130") (pin "2") (pinfunction "2_2") (pintype "passive"))
      (node (ref "TP34") (pin "1") (pinfunction "1_1") (pintype "passive"))
      (node (ref "U19") (pin "4") (pinfunction "IN-_4") (pintype "input"))
    )
    (net (code "145") (name "Net-(U19-OUT)") (class "Default")
      (node (ref "C70") (pin "1") (pinfunction "1_1") (pintype "passive"))
      (node (ref "R127") (pin "2") (pinfunction "2_2") (pintype "passive"))
      (node (ref "R131") (pin "1") (pinfunction "1_1") (pintype "passive"))
      (node (ref "U19") (pin "1") (pinfunction "OUT_1") (pintype "output"))
    )
    (net (code "146") (name "Net-(U19-V-)") (class "Default")
      (node (ref "R134") (pin "1") (pinfunction "1_1") (pintype "passive"))
      (node (ref "R135") (pin "1") (pinfunction "1_1") (pintype "passive"))
      (node (ref "U19") (pin "2") (pinfunction "V-_2") (pintype "power_in"))
    )
    (net (code "147") (name "Net-(U20-CE)") (class "Default")
      (node (ref "R138") (pin "2") (pinfunction "2_2") (pintype "passive"))
      (node (ref "R139") (pin "1") (pinfunction "1_1") (pintype "passive"))
      (node (ref "U20") (pin "3") (pinfunction "CE_3") (pintype "input"))
    )
    (net (code "148") (name "Net-(U20-NC)") (class "Default")
      (node (ref "R137") (pin "1") (pinfunction "1_1") (pintype "passive"))
      (node (ref "U20") (pin "4") (pinfunction "NC_4") (pintype "passive"))
    )
    (net (code "149") (name "Output Current of FB to micro controller") (class "Default")
      (node (ref "FB12") (pin "2") (pinfunction "2_2") (pintype "power_in"))
      (node (ref "J2") (pin "2") (pinfunction "2_2") (pintype "passive"))
    )
    (net (code "150") (name "Output voltage of FB") (class "Default")
      (node (ref "FB13") (pin "2") (pinfunction "2_2") (pintype "power_in"))
      (node (ref "J2") (pin "3") (pinfunction "3_3") (pintype "passive"))
      (node (ref "TP47") (pin "1") (pinfunction "1_1") (pintype "passive"))
      (node (ref "TP60") (pin "1") (pinfunction "1_1") (pintype "passive"))
    )
    (net (code "151") (name "P1 OP37-2") (class "Default")
      (node (ref "R155") (pin "2") (pinfunction "2_2") (pintype "passive"))
      (node (ref "U21") (pin "1") (pinfunction "OFFSET_TRIM_1") (pintype "input"))
    )
    (net (code "152") (name "P2 OP37-2") (class "Default")
      (node (ref "C87") (pin "1") (pinfunction "1_1") (pintype "passive"))
      (node (ref "R158") (pin "1") (pinfunction "1_1") (pintype "passive"))
      (node (ref "R159") (pin "2") (pinfunction "2_2") (pintype "passive"))
      (node (ref "R169") (pin "2") (pinfunction "2_2") (pintype "passive"))
      (node (ref "R170") (pin "2") (pinfunction "2_2") (pintype "passive"))
      (node (ref "U21") (pin "2") (pinfunction "IN-_2") (pintype "input"))
    )
    (net (code "153") (name "P3 OP37-2") (class "Default")
      (node (ref "C86") (pin "1") (pinfunction "1_1") (pintype "passive"))
      (node (ref "R157") (pin "1") (pinfunction "1_1") (pintype "passive"))
      (node (ref "R164") (pin "1") (pinfunction "1_1") (pintype "passive"))
      (node (ref "U21") (pin "3") (pinfunction "IN+_3") (pintype "input"))
    )
    (net (code "154") (name "P4 OP37-2") (class "Default")
      (node (ref "R145") (pin "2") (pinfunction "2_2") (pintype "passive"))
      (node (ref "R146") (pin "2") (pinfunction "2_2") (pintype "passive"))
      (node (ref "U21") (pin "4") (pinfunction "VCC-_4") (pintype "power_in"))
    )
    (net (code "155") (name "P5 OP37-2") (class "Default")
      (node (ref "R143") (pin "1") (pinfunction "1_1") (pintype "passive"))
      (node (ref "U21") (pin "5") (pinfunction "NC_5") (pintype "passive"))
    )
    (net (code "156") (name "P6 OP37-2") (class "Default")
      (node (ref "C87") (pin "2") (pinfunction "2_2") (pintype "passive"))
      (node (ref "C88") (pin "1") (pinfunction "1_1") (pintype "passive"))
      (node (ref "R169") (pin "1") (pinfunction "1_1") (pintype "passive"))
      (node (ref "R170") (pin "1") (pinfunction "1_1") (pintype "passive"))
      (node (ref "R173") (pin "1") (pinfunction "1_1") (pintype "passive"))
      (node (ref "TP45") (pin "1") (pinfunction "1_1") (pintype "passive"))
      (node (ref "U21") (pin "6") (pinfunction "OUT_6") (pintype "output"))
    )
    (net (code "157") (name "P7 OP37-2") (class "Default")
      (node (ref "C80") (pin "1") (pinfunction "1_1") (pintype "passive"))
      (node (ref "R140") (pin "2") (pinfunction "2_2") (pintype "passive"))
      (node (ref "R144") (pin "2") (pinfunction "2_2") (pintype "passive"))
      (node (ref "U21") (pin "7") (pinfunction "VCC+_7") (pintype "power_in"))
    )
    (net (code "158") (name "P8 OP37-2") (class "Default")
      (node (ref "R165") (pin "2") (pinfunction "2_2") (pintype "passive"))
      (node (ref "U21") (pin "8") (pinfunction "OFFSET_TRIM_8") (pintype "input"))
    )
    (net (code "159") (name "Relay FB command") (class "Default")
      (node (ref "J2") (pin "11") (pinfunction "11_11") (pintype "passive"))
    )
    (net (code "160") (name "Source 1") (class "Default")
      (node (ref "C10") (pin "2") (pinfunction "2_2") (pintype "passive"))
      (node (ref "C14") (pin "1") (pinfunction "1_1") (pintype "passive"))
      (node (ref "C15") (pin "2") (pinfunction "2_2") (pintype "passive"))
      (node (ref "C16") (pin "2") (pinfunction "2_2") (pintype "passive"))
      (node (ref "C18") (pin "2") (pinfunction "2_2") (pintype "passive"))
      (node (ref "C19") (pin "1") (pinfunction "1_1") (pintype "passive"))
      (node (ref "C9") (pin "2") (pinfunction "2_2") (pintype "passive"))
      (node (ref "CR3") (pin "1") (pinfunction "A_1") (pintype "passive"))
      (node (ref "D13") (pin "2") (pinfunction "C_2") (pintype "passive"))
      (node (ref "D6") (pin "1") (pinfunction "A_1") (pintype "passive"))
      (node (ref "D7") (pin "1") (pinfunction "A_1") (pintype "passive"))
      (node (ref "D8") (pin "1") (pinfunction "A_1") (pintype "passive"))
      (node (ref "Q1") (pin "3") (pinfunction "E_3") (pintype "passive"))
      (node (ref "Q2") (pin "2") (pinfunction "C_2") (pintype "passive"))
      (node (ref "R20") (pin "1") (pinfunction "1_1") (pintype "passive"))
      (node (ref "R30") (pin "1") (pinfunction "1_1") (pintype "passive"))
      (node (ref "R33") (pin "1") (pinfunction "1_1") (pintype "passive"))
      (node (ref "R35") (pin "2") (pinfunction "2_2") (pintype "passive"))
      (node (ref "R52") (pin "2") (pinfunction "2_2") (pintype "passive"))
      (node (ref "R8") (pin "1") (pinfunction "1_1") (pintype "passive"))
      (node (ref "TP77") (pin "1") (pinfunction "1_1") (pintype "passive"))
      (node (ref "TP78") (pin "1") (pinfunction "1_1") (pintype "passive"))
      (node (ref "U17") (pin "1") (pinfunction "IN_1") (pintype "passive"))
      (node (ref "U17") (pin "2") (pinfunction "IN_2") (pintype "passive"))
      (node (ref "U17") (pin "3") (pinfunction "IN_3") (pintype "passive"))
      (node (ref "U6") (pin "4") (pinfunction "GND_4") (pintype "power_in"))
      (node (ref "U6") (pin "5") (pinfunction "GND_5") (pintype "power_in"))
    )
    (net (code "161") (name "Source 4") (class "Default")
      (node (ref "C11") (pin "2") (pinfunction "2_2") (pintype "passive"))
      (node (ref "C12") (pin "2") (pinfunction "2_2") (pintype "passive"))
      (node (ref "C13") (pin "2") (pinfunction "2_2") (pintype "passive"))
      (node (ref "C17") (pin "1") (pinfunction "1_1") (pintype "passive"))
      (node (ref "C23") (pin "1") (pinfunction "1_1") (pintype "passive"))
      (node (ref "C65") (pin "2") (pinfunction "2_2") (pintype "passive"))
      (node (ref "C66") (pin "2") (pinfunction "2_2") (pintype "passive"))
      (node (ref "CR15") (pin "1") (pinfunction "A_1") (pintype "passive"))
      (node (ref "D10") (pin "1") (pinfunction "A_1") (pintype "passive"))
      (node (ref "D14") (pin "2") (pinfunction "C_2") (pintype "passive"))
      (node (ref "D5") (pin "1") (pinfunction "A_1") (pintype "passive"))
      (node (ref "D9") (pin "1") (pinfunction "A_1") (pintype "passive"))
      (node (ref "L1") (pin "1") (pinfunction "1_1") (pintype "passive"))
      (node (ref "Q3") (pin "2") (pinfunction "C_2") (pintype "passive"))
      (node (ref "Q4") (pin "3") (pinfunction "E_3") (pintype "passive"))
      (node (ref "R110") (pin "1") (pinfunction "1_1") (pintype "passive"))
      (node (ref "R120") (pin "1") (pinfunction "1_1") (pintype "passive"))
      (node (ref "R34") (pin "1") (pinfunction "1_1") (pintype "passive"))
      (node (ref "R36") (pin "2") (pinfunction "2_2") (pintype "passive"))
      (node (ref "R54") (pin "2") (pinfunction "2_2") (pintype "passive"))
      (node (ref "R90") (pin "1") (pinfunction "1_1") (pintype "passive"))
      (node (ref "TP75") (pin "1") (pinfunction "1_1") (pintype "passive"))
      (node (ref "TP76") (pin "1") (pinfunction "1_1") (pintype "passive"))
      (node (ref "U15") (pin "4") (pinfunction "GND_4") (pintype "power_in"))
      (node (ref "U15") (pin "5") (pinfunction "GND_5") (pintype "power_in"))
    )
    (net (code "162") (name "Spare Analog FB 1") (class "Default")
      (node (ref "J2") (pin "4") (pinfunction "4_4") (pintype "passive"))
    )
    (net (code "163") (name "Spare Analog FB 2") (class "Default")
      (node (ref "J2") (pin "17") (pinfunction "17_17") (pintype "passive"))
    )
    (net (code "164") (name "Spare Analog FB 3") (class "Default")
      (node (ref "J2") (pin "5") (pinfunction "5_5") (pintype "passive"))
    )
    (net (code "165") (name "Spare Analog FB 4") (class "Default")
      (node (ref "J2") (pin "18") (pinfunction "18_18") (pintype "passive"))
    )
    (net (code "166") (name "Spare Dig FB 1") (class "Default")
      (node (ref "J2") (pin "20") (pinfunction "20_20") (pintype "passive"))
    )
    (net (code "167") (name "Spare Dig FB 2") (class "Default")
      (node (ref "J2") (pin "7") (pinfunction "7_7") (pintype "passive"))
    )
    (net (code "168") (name "Spare Dig FB 3") (class "Default")
      (node (ref "J2") (pin "19") (pinfunction "19_19") (pintype "passive"))
    )
    (net (code "169") (name "Spare Dig FB 4") (class "Default")
      (node (ref "J2") (pin "6") (pinfunction "6_6") (pintype "passive"))
    )
    (net (code "170") (name "VDD Sensor voltage out") (class "Default")
      (node (ref "C85") (pin "1") (pinfunction "1_1") (pintype "passive"))
      (node (ref "Q5") (pin "1") (pinfunction "VDD1_1") (pintype "power_in"))
    )
    (net (code "171") (name "VGS 1") (class "Default")
      (node (ref "C10") (pin "1") (pinfunction "1_1") (pintype "passive"))
      (node (ref "C14") (pin "2") (pinfunction "2_2") (pintype "passive"))
      (node (ref "C47") (pin "1") (pinfunction "1_1") (pintype "passive"))
      (node (ref "C48") (pin "2") (pinfunction "2_2") (pintype "passive"))
      (node (ref "C6") (pin "1") (pinfunction "1_1") (pintype "passive"))
      (node (ref "C7") (pin "1") (pinfunction "1_1") (pintype "passive"))
      (node (ref "C8") (pin "2") (pinfunction "2_2") (pintype "passive"))
      (node (ref "C9") (pin "1") (pinfunction "1_1") (pintype "passive"))
      (node (ref "CR1") (pin "2") (pinfunction "K_2") (pintype "passive"))
      (node (ref "CR4") (pin "2") (pinfunction "K_2") (pintype "passive"))
      (node (ref "D7") (pin "2") (pinfunction "K_2") (pintype "passive"))
      (node (ref "DS6") (pin "1") (pinfunction "A_1") (pintype "passive"))
      (node (ref "PS1") (pin "14") (pinfunction "+VOUT_14") (pintype "output"))
      (node (ref "TP35") (pin "1") (pinfunction "1_1") (pintype "passive"))
      (node (ref "TP70") (pin "1") (pinfunction "1_1") (pintype "passive"))
      (node (ref "U5") (pin "6") (pinfunction "VDD_6") (pintype "power_in"))
      (node (ref "U6") (pin "1") (pinfunction "VCC_1") (pintype "power_in"))
      (node (ref "U6") (pin "8") (pinfunction "VCC_8") (pintype "power_in"))
    )
    (net (code "172") (name "VGS 2") (class "Default")
      (node (ref "C32") (pin "2") (pinfunction "2_2") (pintype "passive"))
      (node (ref "C33") (pin "1") (pinfunction "1_1") (pintype "passive"))
      (node (ref "C34") (pin "1") (pinfunction "1_1") (pintype "passive"))
      (node (ref "C36") (pin "2") (pinfunction "2_2") (pintype "passive"))
      (node (ref "C37") (pin "1") (pinfunction "1_1") (pintype "passive"))
      (node (ref "C38") (pin "1") (pinfunction "1_1") (pintype "passive"))
      (node (ref "C50") (pin "1") (pinfunction "1_1") (pintype "passive"))
      (node (ref "C51") (pin "2") (pinfunction "2_2") (pintype "passive"))
      (node (ref "CR5") (pin "2") (pinfunction "K_2") (pintype "passive"))
      (node (ref "CR8") (pin "2") (pinfunction "K_2") (pintype "passive"))
      (node (ref "D17") (pin "2") (pinfunction "K_2") (pintype "passive"))
      (node (ref "DS7") (pin "1") (pinfunction "A_1") (pintype "passive"))
      (node (ref "PS2") (pin "14") (pinfunction "+VOUT_14") (pintype "output"))
      (node (ref "TP54") (pin "1") (pinfunction "1_1") (pintype "passive"))
      (node (ref "TP81") (pin "1") (pinfunction "1_1") (pintype "passive"))
      (node (ref "U8") (pin "6") (pinfunction "VDD_6") (pintype "power_in"))
      (node (ref "U9") (pin "1") (pinfunction "VCC_1") (pintype "power_in"))
      (node (ref "U9") (pin "8") (pinfunction "VCC_8") (pintype "power_in"))
    )
    (net (code "173") (name "VGS 3") (class "Default")
      (node (ref "C35") (pin "2") (pinfunction "2_2") (pintype "passive"))
      (node (ref "C42") (pin "1") (pinfunction "1_1") (pintype "passive"))
      (node (ref "C43") (pin "1") (pinfunction "1_1") (pintype "passive"))
      (node (ref "C44") (pin "2") (pinfunction "2_2") (pintype "passive"))
      (node (ref "C45") (pin "1") (pinfunction "1_1") (pintype "passive"))
      (node (ref "C46") (pin "1") (pinfunction "1_1") (pintype "passive"))
      (node (ref "C54") (pin "2") (pinfunction "2_2") (pintype "passive"))
      (node (ref "C55") (pin "1") (pinfunction "1_1") (pintype "passive"))
      (node (ref "CR12") (pin "2") (pinfunction "K_2") (pintype "passive"))
      (node (ref "CR9") (pin "2") (pinfunction "K_2") (pintype "passive"))
      (node (ref "D18") (pin "2") (pinfunction "K_2") (pintype "passive"))
      (node (ref "DS8") (pin "1") (pinfunction "A_1") (pintype "passive"))
      (node (ref "PS3") (pin "14") (pinfunction "+VOUT_14") (pintype "output"))
      (node (ref "TP58") (pin "1") (pinfunction "1_1") (pintype "passive"))
      (node (ref "TP82") (pin "1") (pinfunction "1_1") (pintype "passive"))
      (node (ref "U11") (pin "6") (pinfunction "VDD_6") (pintype "power_in"))
      (node (ref "U12") (pin "1") (pinfunction "VCC_1") (pintype "power_in"))
      (node (ref "U12") (pin "8") (pinfunction "VCC_8") (pintype "power_in"))
    )
    (net (code "174") (name "VGS 4") (class "Default")
      (node (ref "C17") (pin "2") (pinfunction "2_2") (pintype "passive"))
      (node (ref "C57") (pin "1") (pinfunction "1_1") (pintype "passive"))
      (node (ref "C58") (pin "1") (pinfunction "1_1") (pintype "passive"))
      (node (ref "C59") (pin "2") (pinfunction "2_2") (pintype "passive"))
      (node (ref "C61") (pin "1") (pinfunction "1_1") (pintype "passive"))
      (node (ref "C65") (pin "1") (pinfunction "1_1") (pintype "passive"))
      (node (ref "C66") (pin "1") (pinfunction "1_1") (pintype "passive"))
      (node (ref "C67") (pin "2") (pinfunction "2_2") (pintype "passive"))
      (node (ref "CR13") (pin "2") (pinfunction "K_2") (pintype "passive"))
      (node (ref "CR16") (pin "2") (pinfunction "K_2") (pintype "passive"))
      (node (ref "D9") (pin "2") (pinfunction "K_2") (pintype "passive"))
      (node (ref "DS11") (pin "1") (pinfunction "A_1") (pintype "passive"))
      (node (ref "PS4") (pin "14") (pinfunction "+VOUT_14") (pintype "output"))
      (node (ref "TP62") (pin "1") (pinfunction "1_1") (pintype "passive"))
      (node (ref "TP72") (pin "1") (pinfunction "1_1") (pintype "passive"))
      (node (ref "U14") (pin "6") (pinfunction "VDD_6") (pintype "power_in"))
      (node (ref "U15") (pin "1") (pinfunction "VCC_1") (pintype "power_in"))
      (node (ref "U15") (pin "8") (pinfunction "VCC_8") (pintype "power_in"))
    )
    (net (code "175") (name "unconnected-(J2-PadM1)") (class "Default")
      (node (ref "J2") (pin "M1") (pinfunction "M1_M1") (pintype "passive"))
    )
    (net (code "176") (name "unconnected-(J2-PadM2)") (class "Default")
      (node (ref "J2") (pin "M2") (pinfunction "M2_M2") (pintype "passive"))
    )
    (net (code "177") (name "unconnected-(PS1-NC-Pad9)") (class "Default")
      (node (ref "PS1") (pin "9") (pinfunction "NC_9") (pintype "passive"))
    )
    (net (code "178") (name "unconnected-(PS1-NC1-Pad11)") (class "Default")
      (node (ref "PS1") (pin "11") (pinfunction "NC1_11") (pintype "passive"))
    )
    (net (code "179") (name "unconnected-(PS2-NC-Pad9)") (class "Default")
      (node (ref "PS2") (pin "9") (pinfunction "NC_9") (pintype "passive"))
    )
    (net (code "180") (name "unconnected-(PS2-NC1-Pad11)") (class "Default")
      (node (ref "PS2") (pin "11") (pinfunction "NC1_11") (pintype "passive"))
    )
    (net (code "181") (name "unconnected-(PS3-NC-Pad9)") (class "Default")
      (node (ref "PS3") (pin "9") (pinfunction "NC_9") (pintype "passive"))
    )
    (net (code "182") (name "unconnected-(PS3-NC1-Pad11)") (class "Default")
      (node (ref "PS3") (pin "11") (pinfunction "NC1_11") (pintype "passive"))
    )
    (net (code "183") (name "unconnected-(PS4-NC-Pad9)") (class "Default")
      (node (ref "PS4") (pin "9") (pinfunction "NC_9") (pintype "passive"))
    )
    (net (code "184") (name "unconnected-(PS4-NC1-Pad11)") (class "Default")
      (node (ref "PS4") (pin "11") (pinfunction "NC1_11") (pintype "passive"))
    )
    (net (code "185") (name "unconnected-(U1-trim-Pad4)") (class "Default")
      (node (ref "U1") (pin "4") (pinfunction "trim_4") (pintype "passive"))
    )
  )
)
